# ACB-R1_1-43-CH04.net
KiCad netlist of a schematic drawn in EAGLE
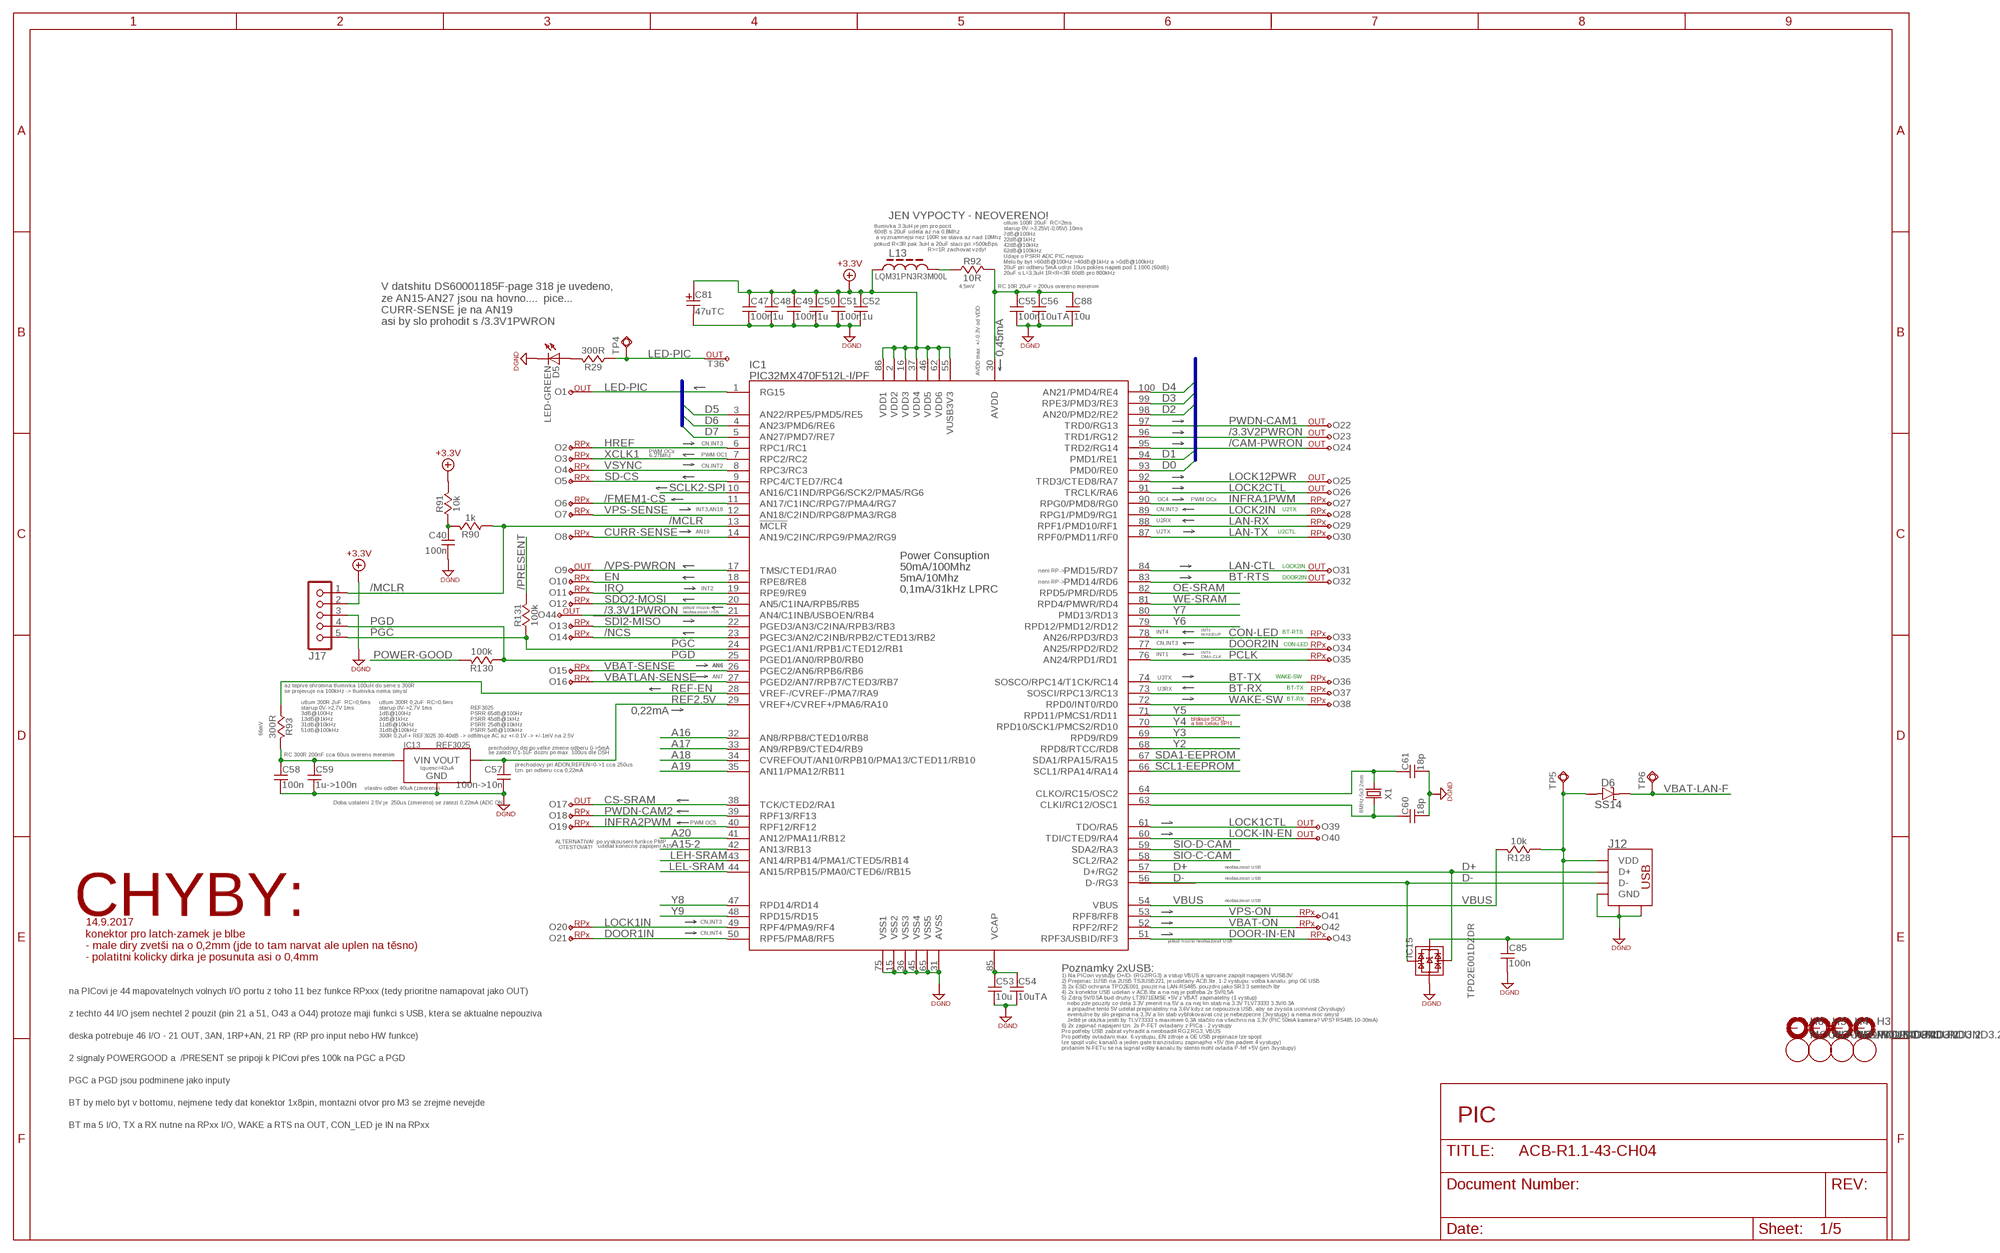
[diagram p0: schematic, sheet 1]
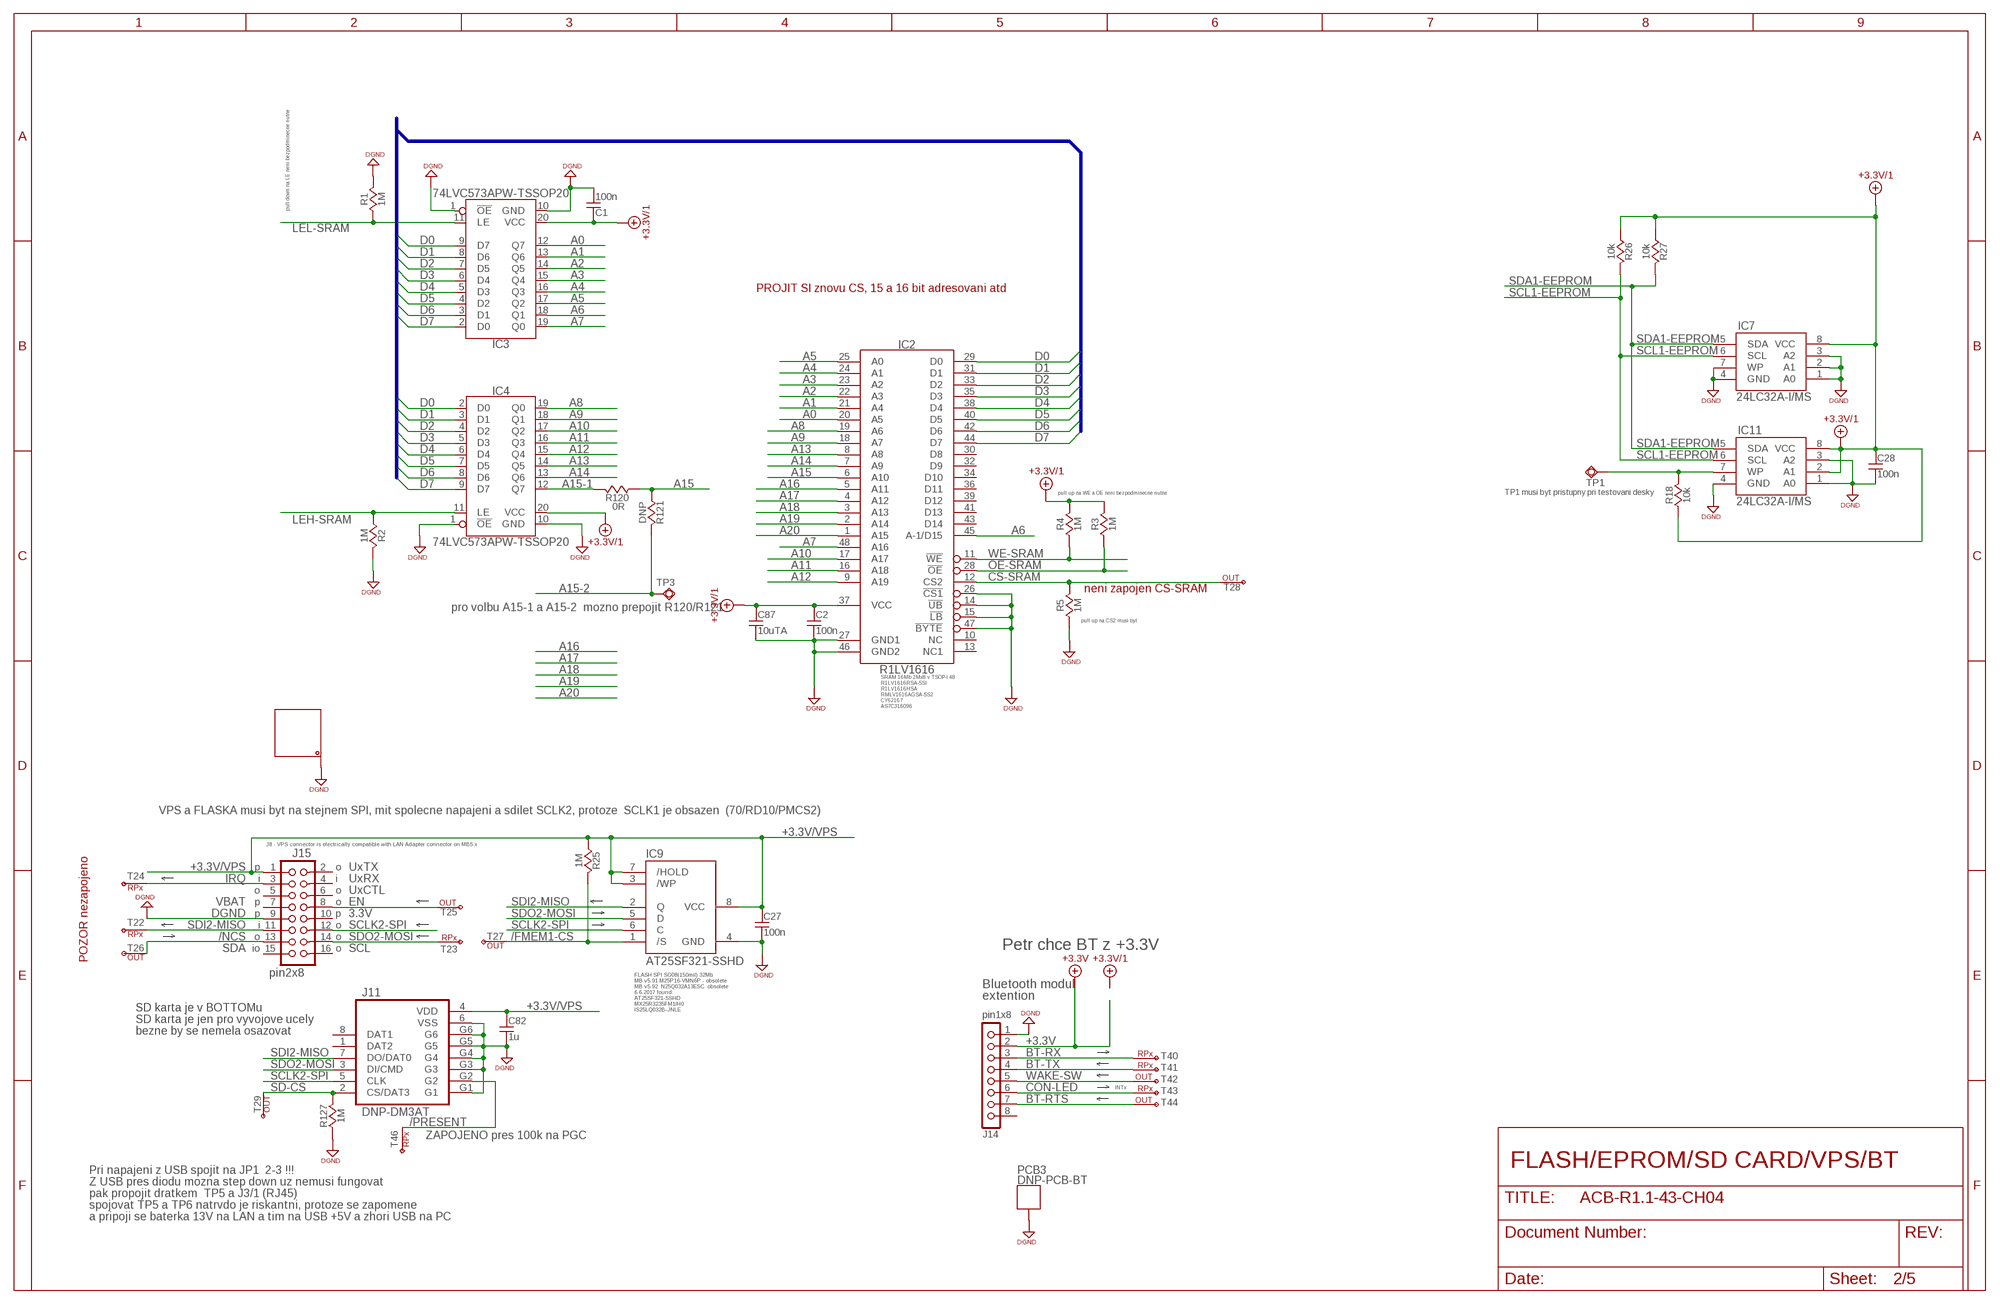
[diagram p1: schematic, sheet 2]
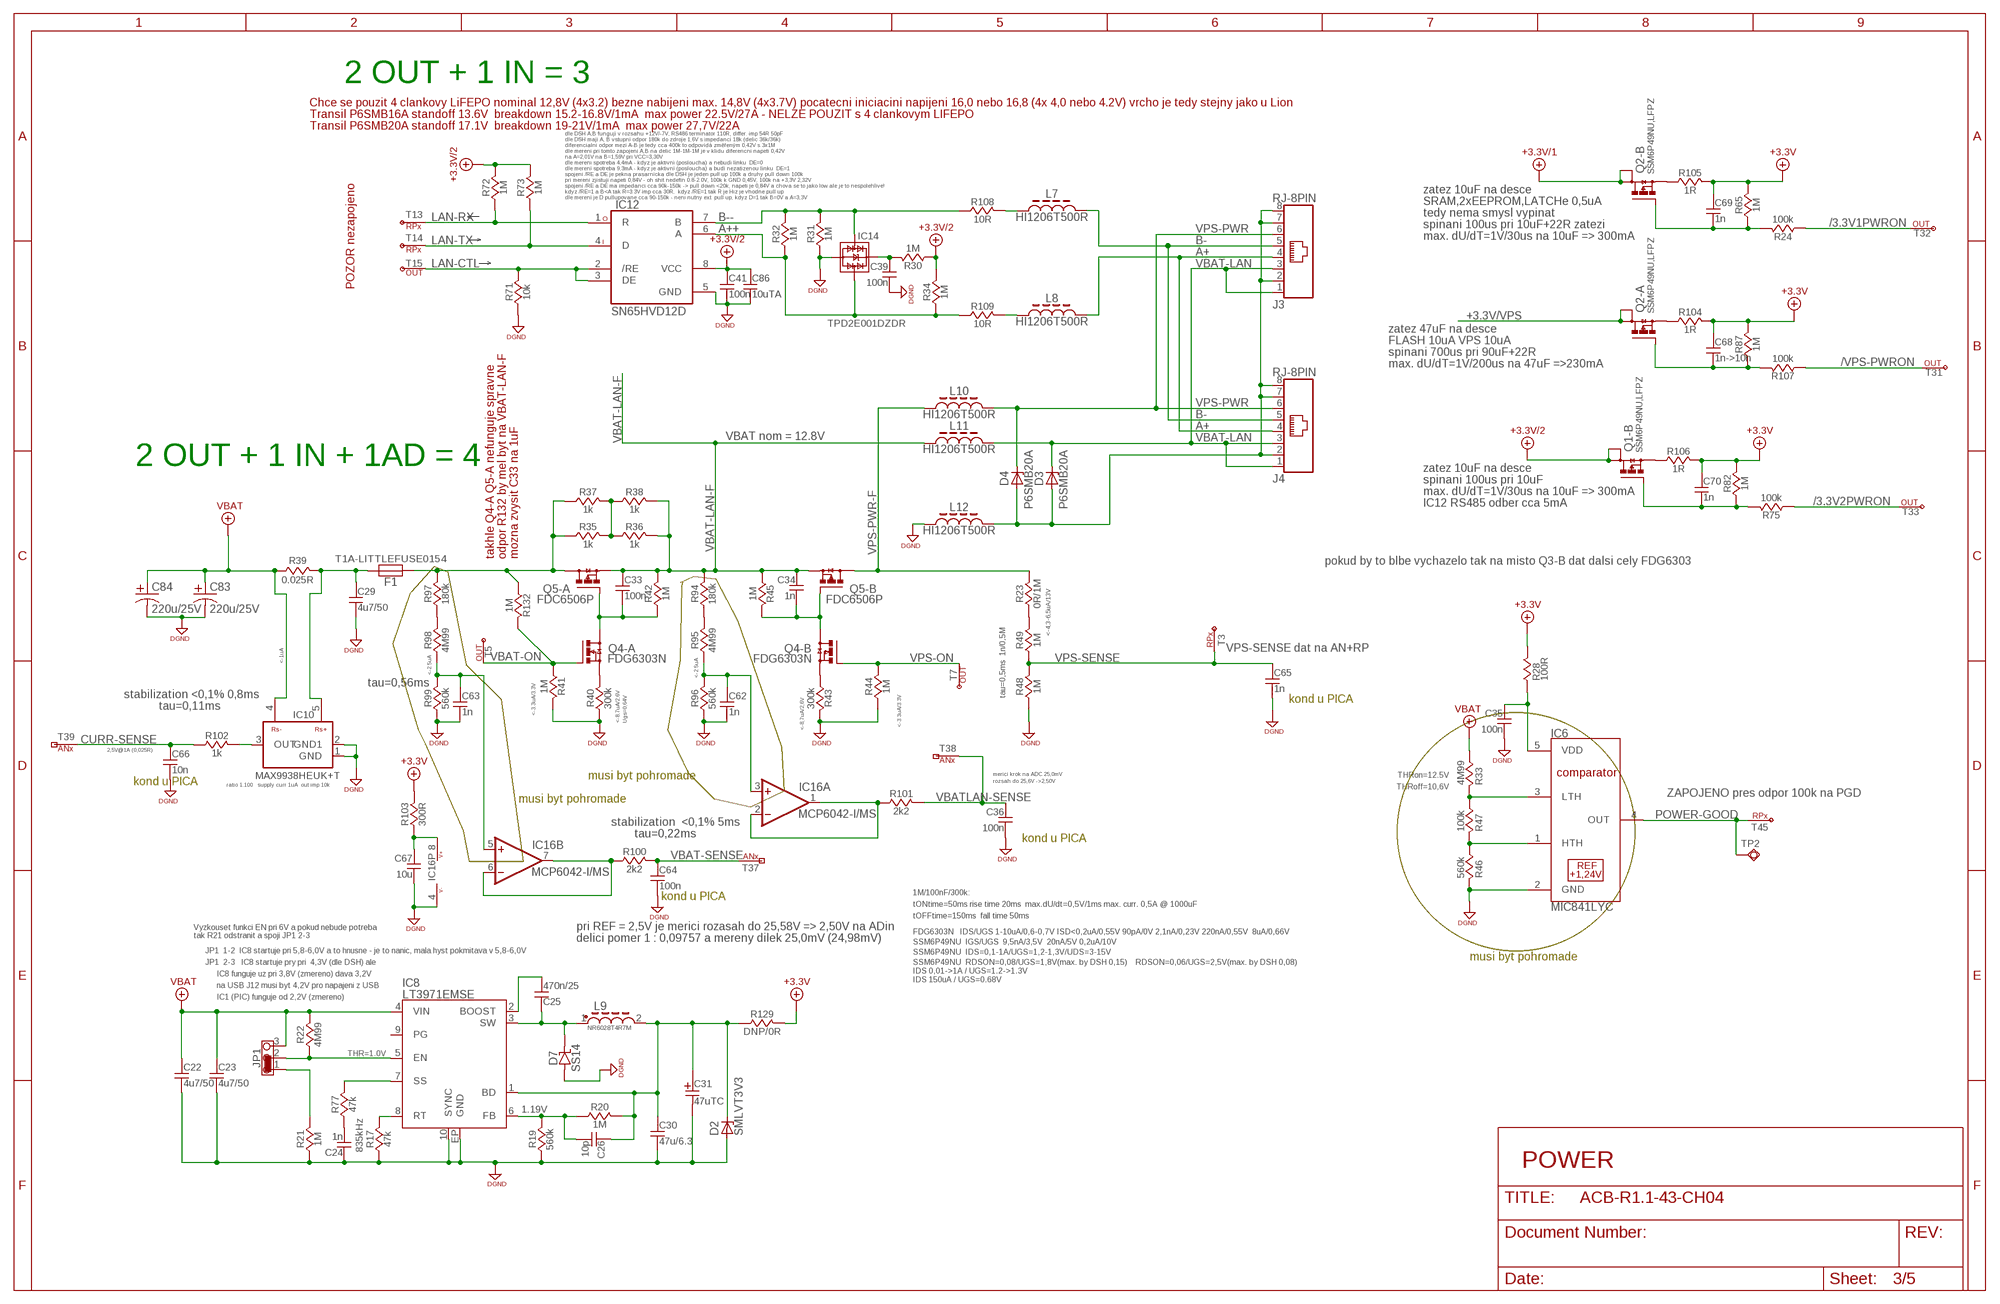
[diagram p2: schematic, sheet 3]
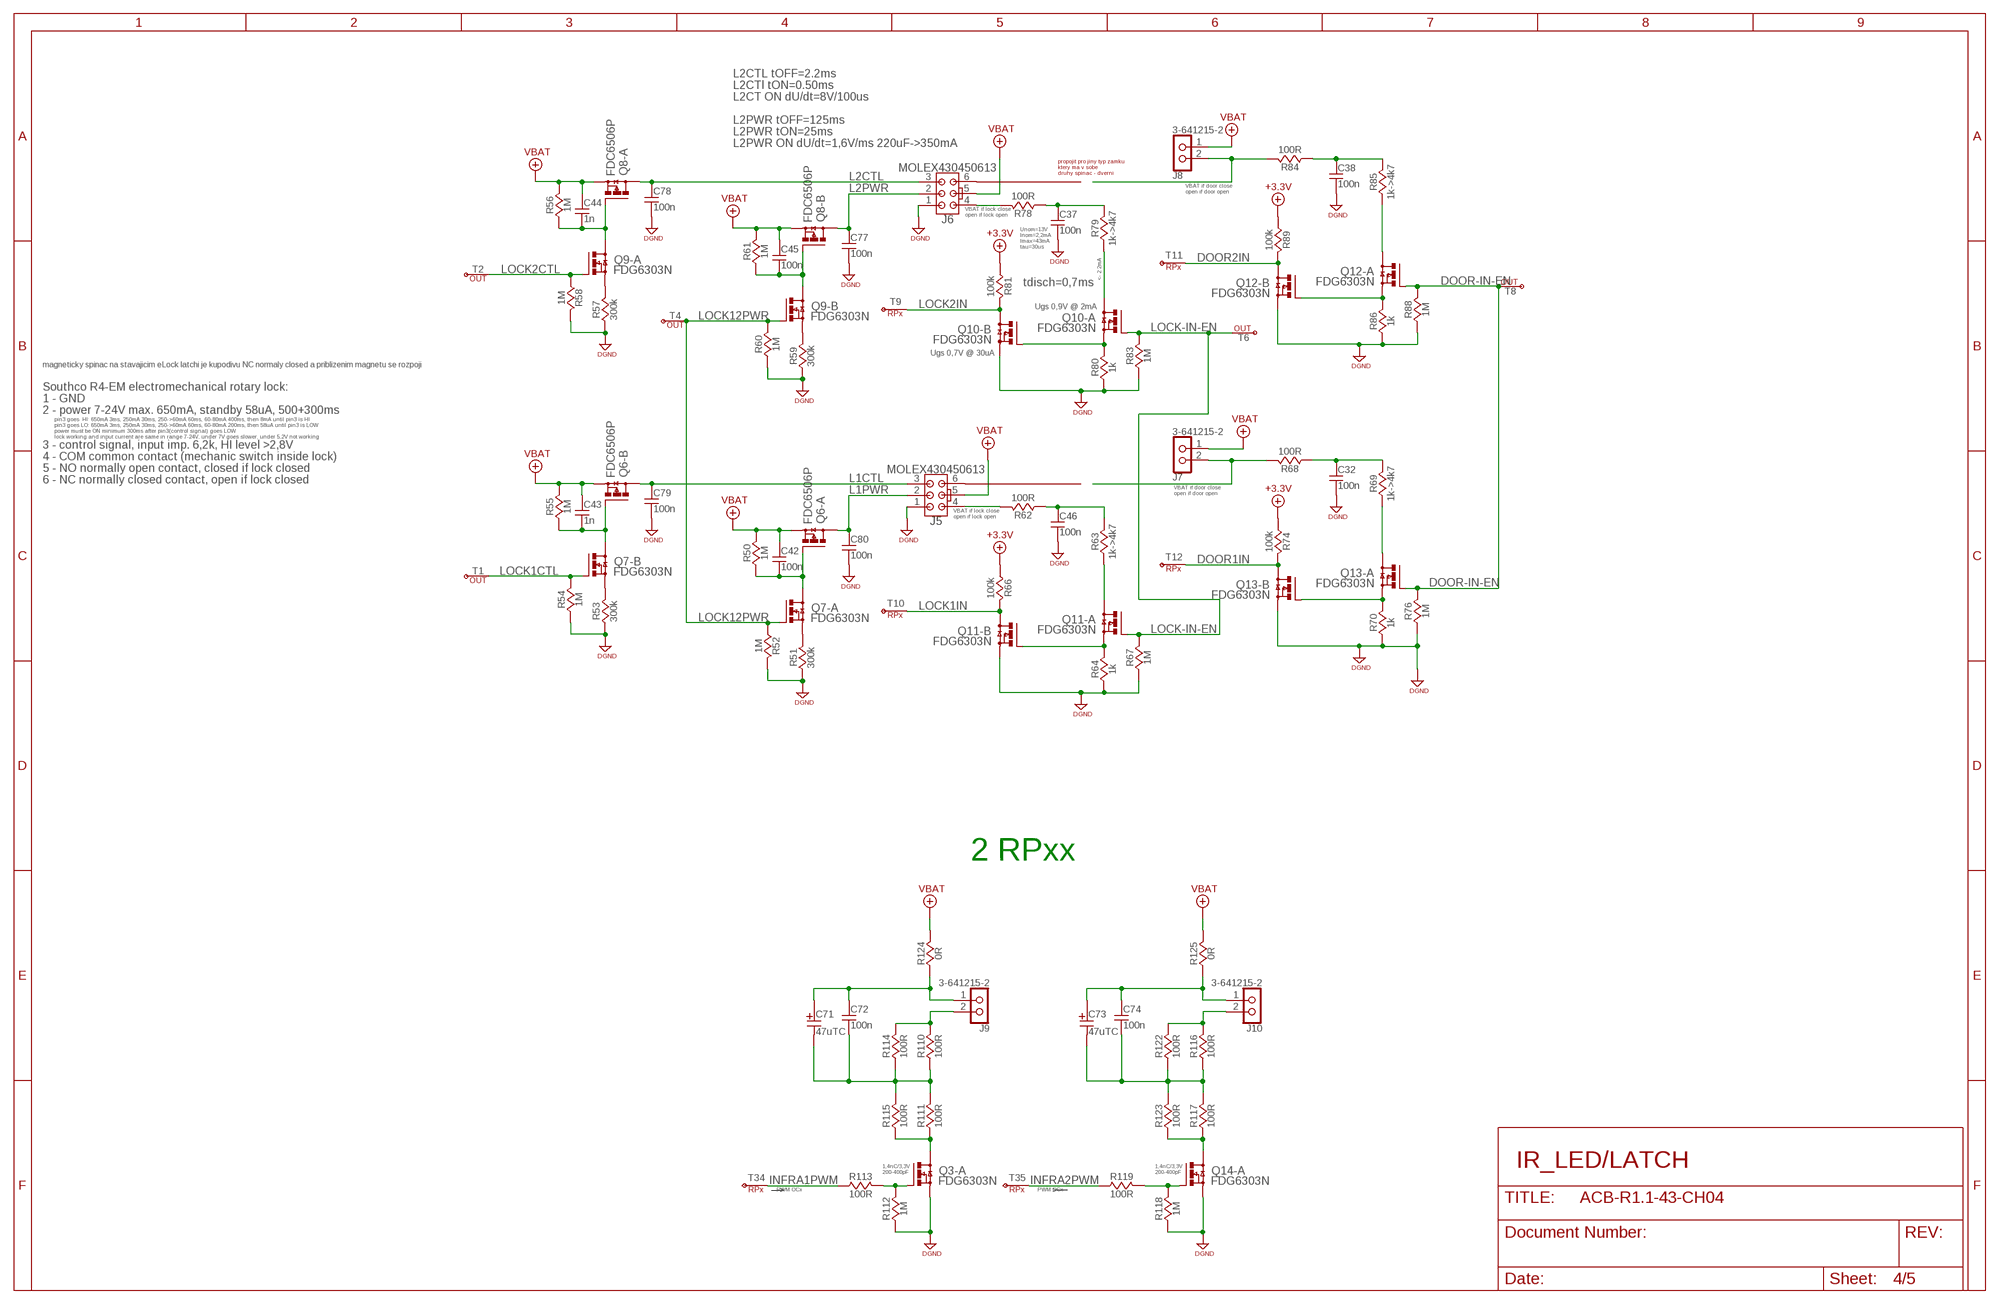
[diagram p3: schematic, sheet 4]
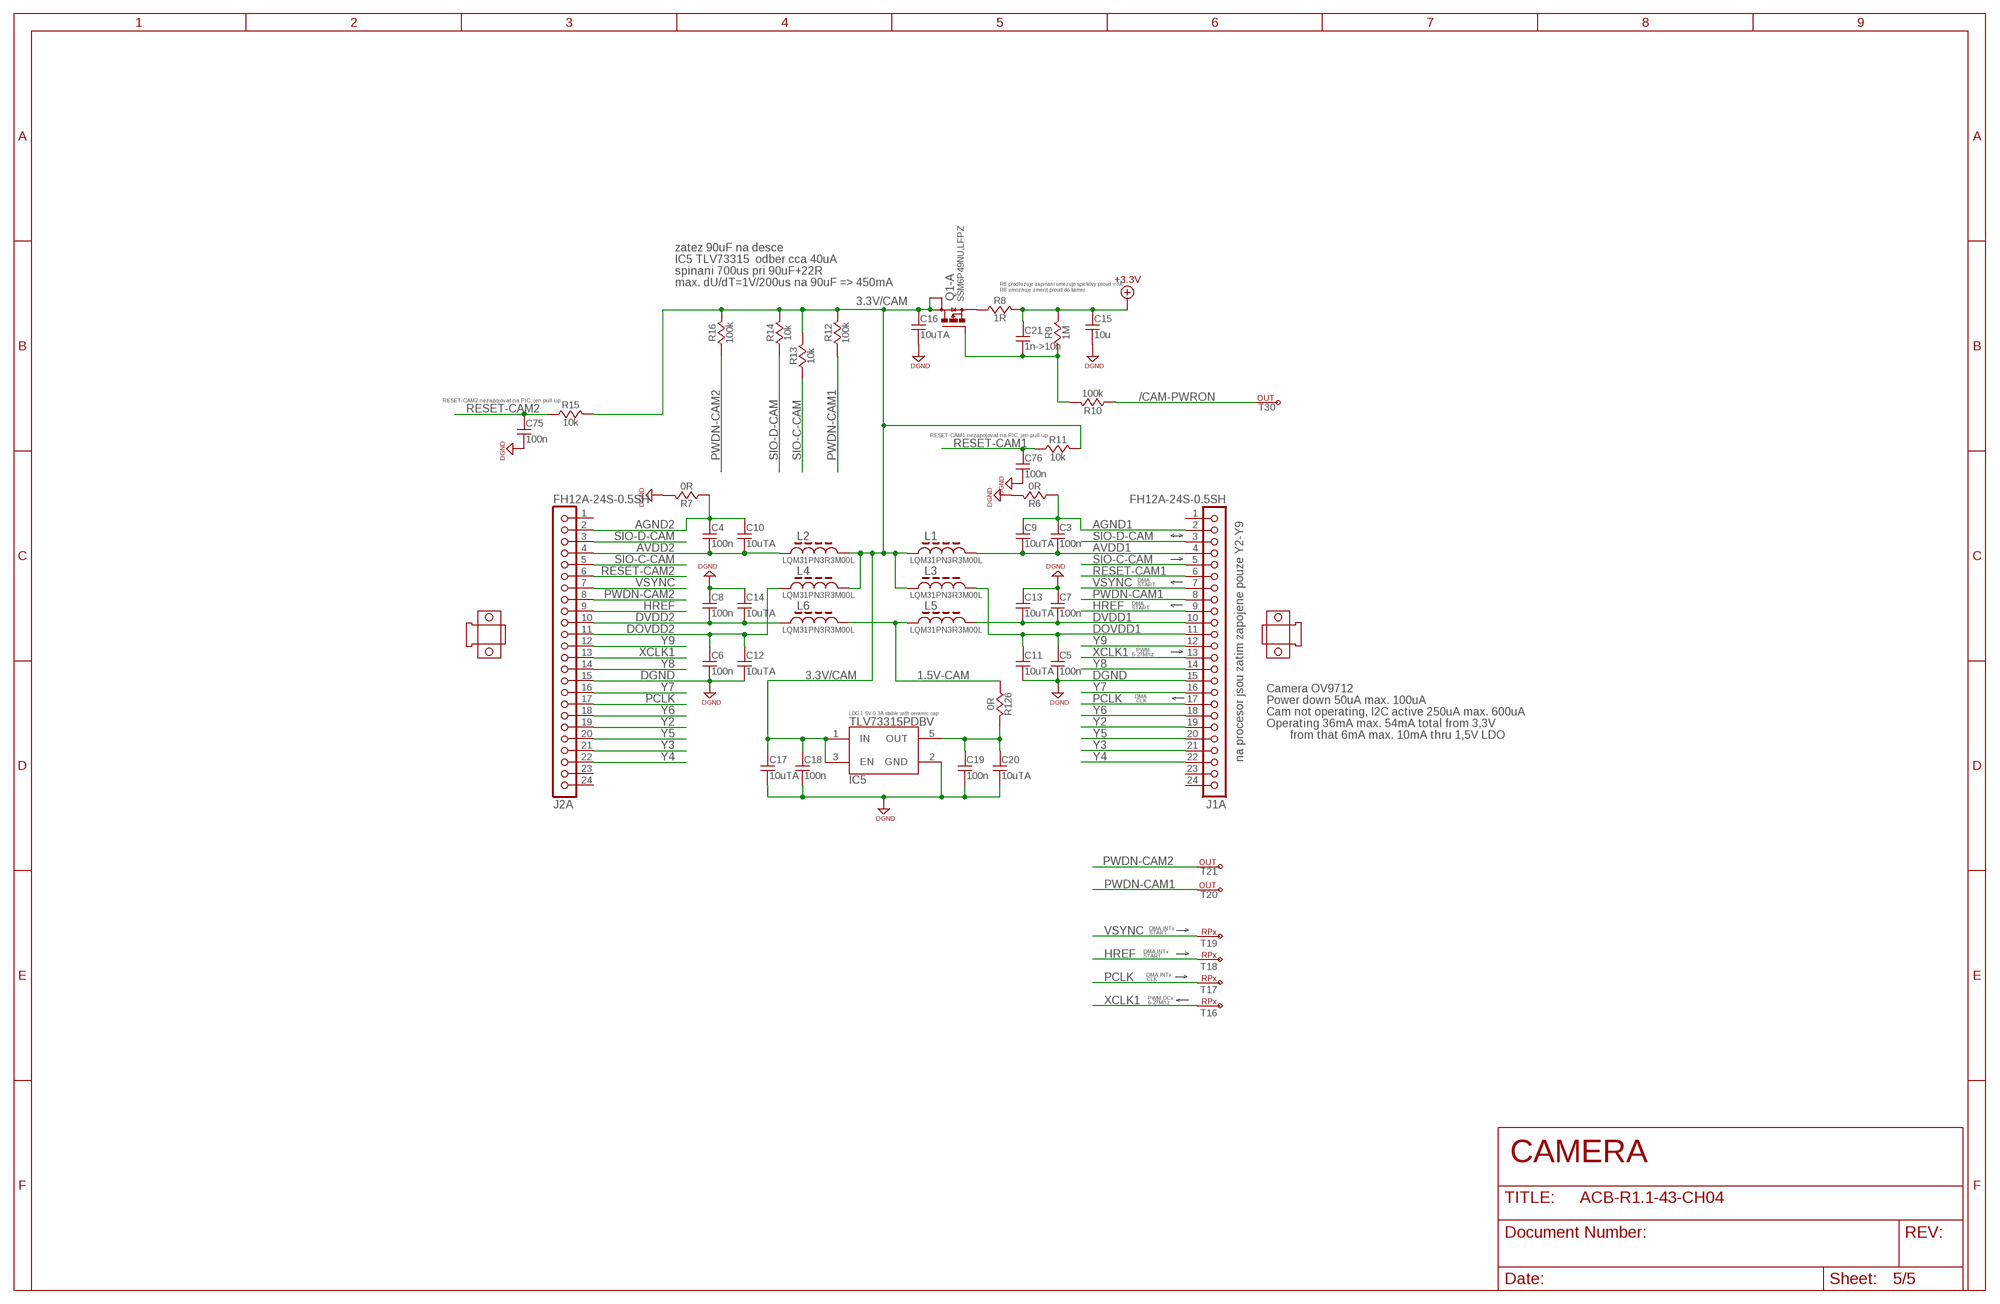
[diagram p4: schematic, sheet 5]

(export (version "E")
  (design (tool "Eeschema 10.0.6"))
  (components
    (comp (ref "C1")
      (value "100n")
      (footprint "eagle-import:0603")
      (libsource (lib "eagle-import") (part "C-0603"))
    )
    (comp (ref "C2")
      (value "100n")
      (footprint "eagle-import:0603")
      (libsource (lib "eagle-import") (part "C-0603"))
    )
    (comp (ref "C27")
      (value "100n")
      (footprint "eagle-import:0603")
      (libsource (lib "eagle-import") (part "C-0603"))
    )
    (comp (ref "C28")
      (value "100n")
      (footprint "eagle-import:0603")
      (libsource (lib "eagle-import") (part "C-0603"))
    )
    (comp (ref "C82")
      (value "1u")
      (footprint "eagle-import:0603")
      (libsource (lib "eagle-import") (part "C-0603"))
    )
    (comp (ref "C87")
      (value "10uTA")
      (footprint "eagle-import:1206")
      (libsource (lib "eagle-import") (part "C-1206"))
    )
    (comp (ref "IC2")
      (value "R1LV1616")
      (footprint "eagle-import:48-TSOP-I")
      (libsource (lib "eagle-import") (part "R1LV1616HSA"))
    )
    (comp (ref "IC3")
      (value "74LVC573APW-TSSOP20")
      (footprint "eagle-import:TSSOP20")
      (libsource (lib "eagle-import") (part "74LVC573APW-TSSOP20"))
    )
    (comp (ref "IC4")
      (value "74LVC573APW-TSSOP20")
      (footprint "eagle-import:TSSOP20")
      (libsource (lib "eagle-import") (part "74LVC573APW-TSSOP20"))
    )
    (comp (ref "IC7")
      (value "24LC32A-I/MS")
      (footprint "eagle-import:MSOP-08")
      (libsource (lib "eagle-import") (part "24-I/MS"))
    )
    (comp (ref "IC9")
      (value "AT25SF321-SSHD")
      (footprint "eagle-import:SO-08")
      (libsource (lib "eagle-import") (part "M25P16-VMN6P"))
    )
    (comp (ref "IC11")
      (value "24LC32A-I/MS")
      (footprint "eagle-import:MSOP-08")
      (libsource (lib "eagle-import") (part "24-I/MS"))
    )
    (comp (ref "J11")
      (value "DNP-DM3AT")
      (footprint "eagle-import:DM3AT")
      (libsource (lib "eagle-import") (part "DM3AT"))
    )
    (comp (ref "J14")
      (value "pin1x8")
      (footprint "eagle-import:MA08-1-MALE")
      (libsource (lib "eagle-import") (part "MA08-1-M"))
    )
    (comp (ref "J15")
      (value "pin2x8")
      (footprint "eagle-import:MA08-2")
      (libsource (lib "eagle-import") (part "MA08-2"))
    )
    (comp (ref "PCB2")
      (value "DNP-PCB-VPS")
      (footprint "eagle-import:PCB-VPS")
      (libsource (lib "eagle-import") (part "PCB-VPS-1"))
    )
    (comp (ref "PCB3")
      (value "DNP-PCB-BT")
      (footprint "eagle-import:BT_MODULE_BRD")
      (libsource (lib "eagle-import") (part "BT_PCBBRD"))
    )
    (comp (ref "R1")
      (value "1M")
      (footprint "eagle-import:0603")
      (libsource (lib "eagle-import") (part "R-0603"))
    )
    (comp (ref "R2")
      (value "1M")
      (footprint "eagle-import:0603")
      (libsource (lib "eagle-import") (part "R-0603"))
    )
    (comp (ref "R3")
      (value "1M")
      (footprint "eagle-import:0603")
      (libsource (lib "eagle-import") (part "R-0603"))
    )
    (comp (ref "R4")
      (value "1M")
      (footprint "eagle-import:0603")
      (libsource (lib "eagle-import") (part "R-0603"))
    )
    (comp (ref "R5")
      (value "1M")
      (footprint "eagle-import:0603")
      (libsource (lib "eagle-import") (part "R-0603"))
    )
    (comp (ref "R18")
      (value "10k")
      (footprint "eagle-import:0603")
      (libsource (lib "eagle-import") (part "R-0603"))
    )
    (comp (ref "R25")
      (value "1M")
      (footprint "eagle-import:0603")
      (libsource (lib "eagle-import") (part "R-0603"))
    )
    (comp (ref "R26")
      (value "10k")
      (footprint "eagle-import:0603")
      (libsource (lib "eagle-import") (part "R-0603"))
    )
    (comp (ref "R27")
      (value "10k")
      (footprint "eagle-import:0603")
      (libsource (lib "eagle-import") (part "R-0603"))
    )
    (comp (ref "R120")
      (value "0R")
      (footprint "eagle-import:0603")
      (libsource (lib "eagle-import") (part "R-0603"))
    )
    (comp (ref "R121")
      (value "DNP")
      (footprint "eagle-import:0603")
      (libsource (lib "eagle-import") (part "R-0603"))
    )
    (comp (ref "R127")
      (value "1M")
      (footprint "eagle-import:0603")
      (libsource (lib "eagle-import") (part "R-0603"))
    )
    (comp (ref "T22")
      (value "PIC-RPX")
      (footprint "eagle-import:TEMP-PAD")
      (libsource (lib "eagle-import") (part "PIC-RPX"))
    )
    (comp (ref "T23")
      (value "PIC-RPX")
      (footprint "eagle-import:TEMP-PAD")
      (libsource (lib "eagle-import") (part "PIC-RPX"))
    )
    (comp (ref "T24")
      (value "PIC-RPX")
      (footprint "eagle-import:TEMP-PAD")
      (libsource (lib "eagle-import") (part "PIC-RPX"))
    )
    (comp (ref "T25")
      (value "PIC-OUT")
      (footprint "eagle-import:TEMP-PAD")
      (libsource (lib "eagle-import") (part "PIC-OUT"))
    )
    (comp (ref "T26")
      (value "PIC-OUT")
      (footprint "eagle-import:TEMP-PAD")
      (libsource (lib "eagle-import") (part "PIC-OUT"))
    )
    (comp (ref "T27")
      (value "PIC-OUT")
      (footprint "eagle-import:TEMP-PAD")
      (libsource (lib "eagle-import") (part "PIC-OUT"))
    )
    (comp (ref "T28")
      (value "PIC-OUT")
      (footprint "eagle-import:TEMP-PAD")
      (libsource (lib "eagle-import") (part "PIC-OUT"))
    )
    (comp (ref "T29")
      (value "PIC-OUT")
      (footprint "eagle-import:TEMP-PAD")
      (libsource (lib "eagle-import") (part "PIC-OUT"))
    )
    (comp (ref "T40")
      (value "PIC-RPX")
      (footprint "eagle-import:TEMP-PAD")
      (libsource (lib "eagle-import") (part "PIC-RPX"))
    )
    (comp (ref "T41")
      (value "PIC-RPX")
      (footprint "eagle-import:TEMP-PAD")
      (libsource (lib "eagle-import") (part "PIC-RPX"))
    )
    (comp (ref "T42")
      (value "PIC-OUT")
      (footprint "eagle-import:TEMP-PAD")
      (libsource (lib "eagle-import") (part "PIC-OUT"))
    )
    (comp (ref "T43")
      (value "PIC-RPX")
      (footprint "eagle-import:TEMP-PAD")
      (libsource (lib "eagle-import") (part "PIC-RPX"))
    )
    (comp (ref "T44")
      (value "PIC-OUT")
      (footprint "eagle-import:TEMP-PAD")
      (libsource (lib "eagle-import") (part "PIC-OUT"))
    )
    (comp (ref "T46")
      (value "PIC-RPX")
      (footprint "eagle-import:TEMP-PAD")
      (libsource (lib "eagle-import") (part "PIC-RPX"))
    )
    (comp (ref "TP1")
      (value "DNP-TestPoint")
      (footprint "eagle-import:SMD_ROUND_1MM")
      (libsource (lib "eagle-import") (part "ROUND_SMD1MM"))
    )
    (comp (ref "TP3")
      (value "DNP-TestPoint")
      (footprint "eagle-import:TH_ROUND_14MM08MM")
      (libsource (lib "eagle-import") (part "ROUND_SMDTH1.4MM"))
    )
    (comp (ref "C32")
      (value "100n")
      (footprint "eagle-import:0603")
      (libsource (lib "eagle-import") (part "C-0603"))
    )
    (comp (ref "C37")
      (value "100n")
      (footprint "eagle-import:0603")
      (libsource (lib "eagle-import") (part "C-0603"))
    )
    (comp (ref "C38")
      (value "100n")
      (footprint "eagle-import:0603")
      (libsource (lib "eagle-import") (part "C-0603"))
    )
    (comp (ref "C42")
      (value "100n")
      (footprint "eagle-import:0603")
      (libsource (lib "eagle-import") (part "C-0603"))
    )
    (comp (ref "C43")
      (value "1n")
      (footprint "eagle-import:0603")
      (libsource (lib "eagle-import") (part "C-0603"))
    )
    (comp (ref "C44")
      (value "1n")
      (footprint "eagle-import:0603")
      (libsource (lib "eagle-import") (part "C-0603"))
    )
    (comp (ref "C45")
      (value "100n")
      (footprint "eagle-import:0603")
      (libsource (lib "eagle-import") (part "C-0603"))
    )
    (comp (ref "C46")
      (value "100n")
      (footprint "eagle-import:0603")
      (libsource (lib "eagle-import") (part "C-0603"))
    )
    (comp (ref "C71")
      (value "47uTC")
      (footprint "eagle-import:CT-C")
      (libsource (lib "eagle-import") (part "CT-C"))
    )
    (comp (ref "C72")
      (value "100n")
      (footprint "eagle-import:0603")
      (libsource (lib "eagle-import") (part "C-0603"))
    )
    (comp (ref "C73")
      (value "47uTC")
      (footprint "eagle-import:CT-C")
      (libsource (lib "eagle-import") (part "CT-C"))
    )
    (comp (ref "C74")
      (value "100n")
      (footprint "eagle-import:0603")
      (libsource (lib "eagle-import") (part "C-0603"))
    )
    (comp (ref "C77")
      (value "100n")
      (footprint "eagle-import:0603")
      (libsource (lib "eagle-import") (part "C-0603"))
    )
    (comp (ref "C78")
      (value "100n")
      (footprint "eagle-import:0603")
      (libsource (lib "eagle-import") (part "C-0603"))
    )
    (comp (ref "C79")
      (value "100n")
      (footprint "eagle-import:0603")
      (libsource (lib "eagle-import") (part "C-0603"))
    )
    (comp (ref "C80")
      (value "100n")
      (footprint "eagle-import:0603")
      (libsource (lib "eagle-import") (part "C-0603"))
    )
    (comp (ref "J5")
      (value "MOLEX430450613")
      (footprint "eagle-import:MOLEX430450613")
      (libsource (lib "eagle-import") (part "MOLEX430450613"))
    )
    (comp (ref "J6")
      (value "MOLEX430450613")
      (footprint "eagle-import:MOLEX430450613")
      (libsource (lib "eagle-import") (part "MOLEX430450613"))
    )
    (comp (ref "J7")
      (value "3-641215-2")
      (footprint "eagle-import:3-641215-2")
      (libsource (lib "eagle-import") (part "3-641215-2"))
    )
    (comp (ref "J8")
      (value "3-641215-2")
      (footprint "eagle-import:3-641215-2")
      (libsource (lib "eagle-import") (part "3-641215-2"))
    )
    (comp (ref "J9")
      (value "3-641215-2")
      (footprint "eagle-import:3-641215-2")
      (libsource (lib "eagle-import") (part "3-641215-2"))
    )
    (comp (ref "J10")
      (value "3-641215-2")
      (footprint "eagle-import:3-641215-2")
      (libsource (lib "eagle-import") (part "3-641215-2"))
    )
    (comp (ref "Q3")
      (value "FDG6303N")
      (footprint "eagle-import:SC70-6")
      (libsource (lib "eagle-import") (part "FDG6303N"))
    )
    (comp (ref "Q6")
      (value "FDC6506P")
      (footprint "eagle-import:SSOT-6")
      (libsource (lib "eagle-import") (part "FDC6506D"))
    )
    (comp (ref "Q7")
      (value "FDG6303N")
      (footprint "eagle-import:SC70-6")
      (libsource (lib "eagle-import") (part "FDG6303N"))
    )
    (comp (ref "Q8")
      (value "FDC6506P")
      (footprint "eagle-import:SSOT-6")
      (libsource (lib "eagle-import") (part "FDC6506D"))
    )
    (comp (ref "Q9")
      (value "FDG6303N")
      (footprint "eagle-import:SC70-6")
      (libsource (lib "eagle-import") (part "FDG6303N"))
    )
    (comp (ref "Q10")
      (value "FDG6303N")
      (footprint "eagle-import:SC70-6")
      (libsource (lib "eagle-import") (part "FDG6303N"))
    )
    (comp (ref "Q11")
      (value "FDG6303N")
      (footprint "eagle-import:SC70-6")
      (libsource (lib "eagle-import") (part "FDG6303N"))
    )
    (comp (ref "Q12")
      (value "FDG6303N")
      (footprint "eagle-import:SC70-6")
      (libsource (lib "eagle-import") (part "FDG6303N"))
    )
    (comp (ref "Q13")
      (value "FDG6303N")
      (footprint "eagle-import:SC70-6")
      (libsource (lib "eagle-import") (part "FDG6303N"))
    )
    (comp (ref "Q14")
      (value "FDG6303N")
      (footprint "eagle-import:SC70-6")
      (libsource (lib "eagle-import") (part "FDG6303N"))
    )
    (comp (ref "R50")
      (value "1M")
      (footprint "eagle-import:0603")
      (libsource (lib "eagle-import") (part "R-0603"))
    )
    (comp (ref "R51")
      (value "300k")
      (footprint "eagle-import:0603")
      (libsource (lib "eagle-import") (part "R-0603"))
    )
    (comp (ref "R52")
      (value "1M")
      (footprint "eagle-import:0603")
      (libsource (lib "eagle-import") (part "R-0603"))
    )
    (comp (ref "R53")
      (value "300k")
      (footprint "eagle-import:0603")
      (libsource (lib "eagle-import") (part "R-0603"))
    )
    (comp (ref "R54")
      (value "1M")
      (footprint "eagle-import:0603")
      (libsource (lib "eagle-import") (part "R-0603"))
    )
    (comp (ref "R55")
      (value "1M")
      (footprint "eagle-import:0603")
      (libsource (lib "eagle-import") (part "R-0603"))
    )
    (comp (ref "R56")
      (value "1M")
      (footprint "eagle-import:0603")
      (libsource (lib "eagle-import") (part "R-0603"))
    )
    (comp (ref "R57")
      (value "300k")
      (footprint "eagle-import:0603")
      (libsource (lib "eagle-import") (part "R-0603"))
    )
    (comp (ref "R58")
      (value "1M")
      (footprint "eagle-import:0603")
      (libsource (lib "eagle-import") (part "R-0603"))
    )
    (comp (ref "R59")
      (value "300k")
      (footprint "eagle-import:0603")
      (libsource (lib "eagle-import") (part "R-0603"))
    )
    (comp (ref "R60")
      (value "1M")
      (footprint "eagle-import:0603")
      (libsource (lib "eagle-import") (part "R-0603"))
    )
    (comp (ref "R61")
      (value "1M")
      (footprint "eagle-import:0603")
      (libsource (lib "eagle-import") (part "R-0603"))
    )
    (comp (ref "R62")
      (value "100R")
      (footprint "eagle-import:0603")
      (libsource (lib "eagle-import") (part "R-0603"))
    )
    (comp (ref "R63")
      (value "1k->4k7")
      (footprint "eagle-import:0603")
      (libsource (lib "eagle-import") (part "R-0603"))
    )
    (comp (ref "R64")
      (value "1k")
      (footprint "eagle-import:0603")
      (libsource (lib "eagle-import") (part "R-0603"))
    )
    (comp (ref "R66")
      (value "100k")
      (footprint "eagle-import:0603")
      (libsource (lib "eagle-import") (part "R-0603"))
    )
    (comp (ref "R67")
      (value "1M")
      (footprint "eagle-import:0603")
      (libsource (lib "eagle-import") (part "R-0603"))
    )
    (comp (ref "R68")
      (value "100R")
      (footprint "eagle-import:0603")
      (libsource (lib "eagle-import") (part "R-0603"))
    )
    (comp (ref "R69")
      (value "1k->4k7")
      (footprint "eagle-import:0603")
      (libsource (lib "eagle-import") (part "R-0603"))
    )
    (comp (ref "R70")
      (value "1k")
      (footprint "eagle-import:0603")
      (libsource (lib "eagle-import") (part "R-0603"))
    )
    (comp (ref "R74")
      (value "100k")
      (footprint "eagle-import:0603")
      (libsource (lib "eagle-import") (part "R-0603"))
    )
    (comp (ref "R76")
      (value "1M")
      (footprint "eagle-import:0603")
      (libsource (lib "eagle-import") (part "R-0603"))
    )
    (comp (ref "R78")
      (value "100R")
      (footprint "eagle-import:0603")
      (libsource (lib "eagle-import") (part "R-0603"))
    )
    (comp (ref "R79")
      (value "1k->4k7")
      (footprint "eagle-import:0603")
      (libsource (lib "eagle-import") (part "R-0603"))
    )
    (comp (ref "R80")
      (value "1k")
      (footprint "eagle-import:0603")
      (libsource (lib "eagle-import") (part "R-0603"))
    )
    (comp (ref "R81")
      (value "100k")
      (footprint "eagle-import:0603")
      (libsource (lib "eagle-import") (part "R-0603"))
    )
    (comp (ref "R83")
      (value "1M")
      (footprint "eagle-import:0603")
      (libsource (lib "eagle-import") (part "R-0603"))
    )
    (comp (ref "R84")
      (value "100R")
      (footprint "eagle-import:0603")
      (libsource (lib "eagle-import") (part "R-0603"))
    )
    (comp (ref "R85")
      (value "1k->4k7")
      (footprint "eagle-import:0603")
      (libsource (lib "eagle-import") (part "R-0603"))
    )
    (comp (ref "R86")
      (value "1k")
      (footprint "eagle-import:0603")
      (libsource (lib "eagle-import") (part "R-0603"))
    )
    (comp (ref "R88")
      (value "1M")
      (footprint "eagle-import:0603")
      (libsource (lib "eagle-import") (part "R-0603"))
    )
    (comp (ref "R89")
      (value "100k")
      (footprint "eagle-import:0603")
      (libsource (lib "eagle-import") (part "R-0603"))
    )
    (comp (ref "R110")
      (value "100R")
      (footprint "eagle-import:0603")
      (libsource (lib "eagle-import") (part "R-0603"))
    )
    (comp (ref "R111")
      (value "100R")
      (footprint "eagle-import:0603")
      (libsource (lib "eagle-import") (part "R-0603"))
    )
    (comp (ref "R112")
      (value "1M")
      (footprint "eagle-import:0603")
      (libsource (lib "eagle-import") (part "R-0603"))
    )
    (comp (ref "R113")
      (value "100R")
      (footprint "eagle-import:0603")
      (libsource (lib "eagle-import") (part "R-0603"))
    )
    (comp (ref "R114")
      (value "100R")
      (footprint "eagle-import:0603")
      (libsource (lib "eagle-import") (part "R-0603"))
    )
    (comp (ref "R115")
      (value "100R")
      (footprint "eagle-import:0603")
      (libsource (lib "eagle-import") (part "R-0603"))
    )
    (comp (ref "R116")
      (value "100R")
      (footprint "eagle-import:0603")
      (libsource (lib "eagle-import") (part "R-0603"))
    )
    (comp (ref "R117")
      (value "100R")
      (footprint "eagle-import:0603")
      (libsource (lib "eagle-import") (part "R-0603"))
    )
    (comp (ref "R118")
      (value "1M")
      (footprint "eagle-import:0603")
      (libsource (lib "eagle-import") (part "R-0603"))
    )
    (comp (ref "R119")
      (value "100R")
      (footprint "eagle-import:0603")
      (libsource (lib "eagle-import") (part "R-0603"))
    )
    (comp (ref "R122")
      (value "100R")
      (footprint "eagle-import:0603")
      (libsource (lib "eagle-import") (part "R-0603"))
    )
    (comp (ref "R123")
      (value "100R")
      (footprint "eagle-import:0603")
      (libsource (lib "eagle-import") (part "R-0603"))
    )
    (comp (ref "R124")
      (value "0R")
      (footprint "eagle-import:0603")
      (libsource (lib "eagle-import") (part "R-0603"))
    )
    (comp (ref "R125")
      (value "0R")
      (footprint "eagle-import:0603")
      (libsource (lib "eagle-import") (part "R-0603"))
    )
    (comp (ref "T1")
      (value "PIC-OUT")
      (footprint "eagle-import:TEMP-PAD")
      (libsource (lib "eagle-import") (part "PIC-OUT"))
    )
    (comp (ref "T2")
      (value "PIC-OUT")
      (footprint "eagle-import:TEMP-PAD")
      (libsource (lib "eagle-import") (part "PIC-OUT"))
    )
    (comp (ref "T4")
      (value "PIC-OUT")
      (footprint "eagle-import:TEMP-PAD")
      (libsource (lib "eagle-import") (part "PIC-OUT"))
    )
    (comp (ref "T6")
      (value "PIC-OUT")
      (footprint "eagle-import:TEMP-PAD")
      (libsource (lib "eagle-import") (part "PIC-OUT"))
    )
    (comp (ref "T8")
      (value "PIC-OUT")
      (footprint "eagle-import:TEMP-PAD")
      (libsource (lib "eagle-import") (part "PIC-OUT"))
    )
    (comp (ref "T9")
      (value "PIC-RPX")
      (footprint "eagle-import:TEMP-PAD")
      (libsource (lib "eagle-import") (part "PIC-RPX"))
    )
    (comp (ref "T10")
      (value "PIC-RPX")
      (footprint "eagle-import:TEMP-PAD")
      (libsource (lib "eagle-import") (part "PIC-RPX"))
    )
    (comp (ref "T11")
      (value "PIC-RPX")
      (footprint "eagle-import:TEMP-PAD")
      (libsource (lib "eagle-import") (part "PIC-RPX"))
    )
    (comp (ref "T12")
      (value "PIC-RPX")
      (footprint "eagle-import:TEMP-PAD")
      (libsource (lib "eagle-import") (part "PIC-RPX"))
    )
    (comp (ref "T34")
      (value "PIC-RPX")
      (footprint "eagle-import:TEMP-PAD")
      (libsource (lib "eagle-import") (part "PIC-RPX"))
    )
    (comp (ref "T35")
      (value "PIC-RPX")
      (footprint "eagle-import:TEMP-PAD")
      (libsource (lib "eagle-import") (part "PIC-RPX"))
    )
    (comp (ref "C40")
      (value "100n")
      (footprint "eagle-import:0603")
      (libsource (lib "eagle-import") (part "C-0603"))
    )
    (comp (ref "C47")
      (value "100n")
      (footprint "eagle-import:0603")
      (libsource (lib "eagle-import") (part "C-0603"))
    )
    (comp (ref "C48")
      (value "1u")
      (footprint "eagle-import:0603")
      (libsource (lib "eagle-import") (part "C-0603"))
    )
    (comp (ref "C49")
      (value "100n")
      (footprint "eagle-import:0603")
      (libsource (lib "eagle-import") (part "C-0603"))
    )
    (comp (ref "C50")
      (value "1u")
      (footprint "eagle-import:0603")
      (libsource (lib "eagle-import") (part "C-0603"))
    )
    (comp (ref "C51")
      (value "100n")
      (footprint "eagle-import:0603")
      (libsource (lib "eagle-import") (part "C-0603"))
    )
    (comp (ref "C52")
      (value "1u")
      (footprint "eagle-import:0603")
      (libsource (lib "eagle-import") (part "C-0603"))
    )
    (comp (ref "C53")
      (value "10u")
      (footprint "eagle-import:0603")
      (libsource (lib "eagle-import") (part "C-0603"))
    )
    (comp (ref "C54")
      (value "10uTA")
      (footprint "eagle-import:1206")
      (libsource (lib "eagle-import") (part "C-1206"))
    )
    (comp (ref "C55")
      (value "100n")
      (footprint "eagle-import:0603")
      (libsource (lib "eagle-import") (part "C-0603"))
    )
    (comp (ref "C56")
      (value "10uTA")
      (footprint "eagle-import:1206")
      (libsource (lib "eagle-import") (part "C-1206"))
    )
    (comp (ref "C57")
      (value "100n->10n")
      (footprint "eagle-import:0603")
      (libsource (lib "eagle-import") (part "C-0603"))
    )
    (comp (ref "C58")
      (value "100n")
      (footprint "eagle-import:0603")
      (libsource (lib "eagle-import") (part "C-0603"))
    )
    (comp (ref "C59")
      (value "1u->100n")
      (footprint "eagle-import:0603")
      (libsource (lib "eagle-import") (part "C-0603"))
    )
    (comp (ref "C60")
      (value "18p")
      (footprint "eagle-import:0603")
      (libsource (lib "eagle-import") (part "C-0603"))
    )
    (comp (ref "C61")
      (value "18p")
      (footprint "eagle-import:0603")
      (libsource (lib "eagle-import") (part "C-0603"))
    )
    (comp (ref "C81")
      (value "47uTC")
      (footprint "eagle-import:CT-C")
      (libsource (lib "eagle-import") (part "CT-C"))
    )
    (comp (ref "C85")
      (value "100n")
      (footprint "eagle-import:0603")
      (libsource (lib "eagle-import") (part "C-0603"))
    )
    (comp (ref "C88")
      (value "10u")
      (footprint "eagle-import:0603")
      (libsource (lib "eagle-import") (part "C-0603"))
    )
    (comp (ref "D5")
      (value "LED-GREEN")
      (footprint "eagle-import:0805-POL")
      (libsource (lib "eagle-import") (part "LED-0805"))
    )
    (comp (ref "D6")
      (value "SS14")
      (footprint "eagle-import:SMA")
      (libsource (lib "eagle-import") (part "DS-SMA"))
    )
    (comp (ref "H3")
      (value "MOUNT-PAD-ROUND3.2")
      (footprint "eagle-import:3,2-PAD")
      (libsource (lib "eagle-import") (part "MOUNT-PAD-ROUND3.2"))
    )
    (comp (ref "H4")
      (value "MOUNT-PAD-ROUND3.2")
      (footprint "eagle-import:3,2-PAD")
      (libsource (lib "eagle-import") (part "MOUNT-PAD-ROUND3.2"))
    )
    (comp (ref "H5")
      (value "MOUNT-PAD-ROUND3.2")
      (footprint "eagle-import:3,2-PAD")
      (libsource (lib "eagle-import") (part "MOUNT-PAD-ROUND3.2"))
    )
    (comp (ref "H6")
      (value "MOUNT-PAD-ROUND3.2")
      (footprint "eagle-import:3,2-PAD")
      (libsource (lib "eagle-import") (part "MOUNT-PAD-ROUND3.2"))
    )
    (comp (ref "IC1")
      (value "PIC32MX470F512L-I/PF")
      (footprint "eagle-import:TQFP100_14X14_0,5MM")
      (libsource (lib "eagle-import") (part "PIC32MX470F512L-I/PF"))
    )
    (comp (ref "IC13")
      (value "REF3025")
      (footprint "eagle-import:SOT23")
      (libsource (lib "eagle-import") (part "REF3025"))
    )
    (comp (ref "IC15")
      (value "TPD2E001DZDR")
      (footprint "eagle-import:SOT-143")
      (libsource (lib "eagle-import") (part "SR05.TCT"))
    )
    (comp (ref "J12")
      (value "USB_A_180")
      (footprint "eagle-import:KONEKT1_USB_A_180")
      (libsource (lib "eagle-import") (part "CON_USB_A180"))
    )
    (comp (ref "J17")
      (value "DNP-open-hole")
      (footprint "eagle-import:MA05-1")
      (libsource (lib "eagle-import") (part "MA05-1"))
    )
    (comp (ref "L13")
      (value "LQM31PN3R3M00L")
      (footprint "eagle-import:1206")
      (libsource (lib "eagle-import") (part "L-1206"))
    )
    (comp (ref "O1")
      (value "PIC-OUT")
      (footprint "eagle-import:TEMP-PAD")
      (libsource (lib "eagle-import") (part "PIC-OUT"))
    )
    (comp (ref "O2")
      (value "PIC-RPX")
      (footprint "eagle-import:TEMP-PAD")
      (libsource (lib "eagle-import") (part "PIC-RPX"))
    )
    (comp (ref "O3")
      (value "PIC-RPX")
      (footprint "eagle-import:TEMP-PAD")
      (libsource (lib "eagle-import") (part "PIC-RPX"))
    )
    (comp (ref "O4")
      (value "PIC-RPX")
      (footprint "eagle-import:TEMP-PAD")
      (libsource (lib "eagle-import") (part "PIC-RPX"))
    )
    (comp (ref "O5")
      (value "PIC-RPX")
      (footprint "eagle-import:TEMP-PAD")
      (libsource (lib "eagle-import") (part "PIC-RPX"))
    )
    (comp (ref "O6")
      (value "PIC-RPX")
      (footprint "eagle-import:TEMP-PAD")
      (libsource (lib "eagle-import") (part "PIC-RPX"))
    )
    (comp (ref "O7")
      (value "PIC-RPX")
      (footprint "eagle-import:TEMP-PAD")
      (libsource (lib "eagle-import") (part "PIC-RPX"))
    )
    (comp (ref "O8")
      (value "PIC-RPX")
      (footprint "eagle-import:TEMP-PAD")
      (libsource (lib "eagle-import") (part "PIC-RPX"))
    )
    (comp (ref "O9")
      (value "PIC-OUT")
      (footprint "eagle-import:TEMP-PAD")
      (libsource (lib "eagle-import") (part "PIC-OUT"))
    )
    (comp (ref "O10")
      (value "PIC-RPX")
      (footprint "eagle-import:TEMP-PAD")
      (libsource (lib "eagle-import") (part "PIC-RPX"))
    )
    (comp (ref "O11")
      (value "PIC-RPX")
      (footprint "eagle-import:TEMP-PAD")
      (libsource (lib "eagle-import") (part "PIC-RPX"))
    )
    (comp (ref "O12")
      (value "PIC-RPX")
      (footprint "eagle-import:TEMP-PAD")
      (libsource (lib "eagle-import") (part "PIC-RPX"))
    )
    (comp (ref "O13")
      (value "PIC-RPX")
      (footprint "eagle-import:TEMP-PAD")
      (libsource (lib "eagle-import") (part "PIC-RPX"))
    )
    (comp (ref "O14")
      (value "PIC-RPX")
      (footprint "eagle-import:TEMP-PAD")
      (libsource (lib "eagle-import") (part "PIC-RPX"))
    )
    (comp (ref "O15")
      (value "PIC-RPX")
      (footprint "eagle-import:TEMP-PAD")
      (libsource (lib "eagle-import") (part "PIC-RPX"))
    )
    (comp (ref "O16")
      (value "PIC-RPX")
      (footprint "eagle-import:TEMP-PAD")
      (libsource (lib "eagle-import") (part "PIC-RPX"))
    )
    (comp (ref "O17")
      (value "PIC-OUT")
      (footprint "eagle-import:TEMP-PAD")
      (libsource (lib "eagle-import") (part "PIC-OUT"))
    )
    (comp (ref "O18")
      (value "PIC-RPX")
      (footprint "eagle-import:TEMP-PAD")
      (libsource (lib "eagle-import") (part "PIC-RPX"))
    )
    (comp (ref "O19")
      (value "PIC-RPX")
      (footprint "eagle-import:TEMP-PAD")
      (libsource (lib "eagle-import") (part "PIC-RPX"))
    )
    (comp (ref "O20")
      (value "PIC-RPX")
      (footprint "eagle-import:TEMP-PAD")
      (libsource (lib "eagle-import") (part "PIC-RPX"))
    )
    (comp (ref "O21")
      (value "PIC-RPX")
      (footprint "eagle-import:TEMP-PAD")
      (libsource (lib "eagle-import") (part "PIC-RPX"))
    )
    (comp (ref "O22")
      (value "PIC-OUT")
      (footprint "eagle-import:TEMP-PAD")
      (libsource (lib "eagle-import") (part "PIC-OUT"))
    )
    (comp (ref "O23")
      (value "PIC-OUT")
      (footprint "eagle-import:TEMP-PAD")
      (libsource (lib "eagle-import") (part "PIC-OUT"))
    )
    (comp (ref "O24")
      (value "PIC-OUT")
      (footprint "eagle-import:TEMP-PAD")
      (libsource (lib "eagle-import") (part "PIC-OUT"))
    )
    (comp (ref "O25")
      (value "PIC-OUT")
      (footprint "eagle-import:TEMP-PAD")
      (libsource (lib "eagle-import") (part "PIC-OUT"))
    )
    (comp (ref "O26")
      (value "PIC-OUT")
      (footprint "eagle-import:TEMP-PAD")
      (libsource (lib "eagle-import") (part "PIC-OUT"))
    )
    (comp (ref "O27")
      (value "PIC-RPX")
      (footprint "eagle-import:TEMP-PAD")
      (libsource (lib "eagle-import") (part "PIC-RPX"))
    )
    (comp (ref "O28")
      (value "PIC-RPX")
      (footprint "eagle-import:TEMP-PAD")
      (libsource (lib "eagle-import") (part "PIC-RPX"))
    )
    (comp (ref "O29")
      (value "PIC-RPX")
      (footprint "eagle-import:TEMP-PAD")
      (libsource (lib "eagle-import") (part "PIC-RPX"))
    )
    (comp (ref "O30")
      (value "PIC-RPX")
      (footprint "eagle-import:TEMP-PAD")
      (libsource (lib "eagle-import") (part "PIC-RPX"))
    )
    (comp (ref "O31")
      (value "PIC-OUT")
      (footprint "eagle-import:TEMP-PAD")
      (libsource (lib "eagle-import") (part "PIC-OUT"))
    )
    (comp (ref "O32")
      (value "PIC-OUT")
      (footprint "eagle-import:TEMP-PAD")
      (libsource (lib "eagle-import") (part "PIC-OUT"))
    )
    (comp (ref "O33")
      (value "PIC-RPX")
      (footprint "eagle-import:TEMP-PAD")
      (libsource (lib "eagle-import") (part "PIC-RPX"))
    )
    (comp (ref "O34")
      (value "PIC-RPX")
      (footprint "eagle-import:TEMP-PAD")
      (libsource (lib "eagle-import") (part "PIC-RPX"))
    )
    (comp (ref "O35")
      (value "PIC-RPX")
      (footprint "eagle-import:TEMP-PAD")
      (libsource (lib "eagle-import") (part "PIC-RPX"))
    )
    (comp (ref "O36")
      (value "PIC-RPX")
      (footprint "eagle-import:TEMP-PAD")
      (libsource (lib "eagle-import") (part "PIC-RPX"))
    )
    (comp (ref "O37")
      (value "PIC-RPX")
      (footprint "eagle-import:TEMP-PAD")
      (libsource (lib "eagle-import") (part "PIC-RPX"))
    )
    (comp (ref "O38")
      (value "PIC-RPX")
      (footprint "eagle-import:TEMP-PAD")
      (libsource (lib "eagle-import") (part "PIC-RPX"))
    )
    (comp (ref "O39")
      (value "PIC-OUT")
      (footprint "eagle-import:TEMP-PAD")
      (libsource (lib "eagle-import") (part "PIC-OUT"))
    )
    (comp (ref "O40")
      (value "PIC-OUT")
      (footprint "eagle-import:TEMP-PAD")
      (libsource (lib "eagle-import") (part "PIC-OUT"))
    )
    (comp (ref "O41")
      (value "PIC-RPX")
      (footprint "eagle-import:TEMP-PAD")
      (libsource (lib "eagle-import") (part "PIC-RPX"))
    )
    (comp (ref "O42")
      (value "PIC-RPX")
      (footprint "eagle-import:TEMP-PAD")
      (libsource (lib "eagle-import") (part "PIC-RPX"))
    )
    (comp (ref "O43")
      (value "PIC-RPX")
      (footprint "eagle-import:TEMP-PAD")
      (libsource (lib "eagle-import") (part "PIC-RPX"))
    )
    (comp (ref "O44")
      (value "PIC-OUT")
      (footprint "eagle-import:TEMP-PAD")
      (libsource (lib "eagle-import") (part "PIC-OUT"))
    )
    (comp (ref "R29")
      (value "300R")
      (footprint "eagle-import:0603")
      (libsource (lib "eagle-import") (part "R-0603"))
    )
    (comp (ref "R90")
      (value "1k")
      (footprint "eagle-import:0603")
      (libsource (lib "eagle-import") (part "R-0603"))
    )
    (comp (ref "R91")
      (value "10k")
      (footprint "eagle-import:0603")
      (libsource (lib "eagle-import") (part "R-0603"))
    )
    (comp (ref "R92")
      (value "10R")
      (footprint "eagle-import:0603")
      (libsource (lib "eagle-import") (part "R-0603"))
    )
    (comp (ref "R93")
      (value "300R")
      (footprint "eagle-import:0603")
      (libsource (lib "eagle-import") (part "R-0603"))
    )
    (comp (ref "R128")
      (value "10k")
      (footprint "eagle-import:0603")
      (libsource (lib "eagle-import") (part "R-0603"))
    )
    (comp (ref "R130")
      (value "100k")
      (footprint "eagle-import:0603")
      (libsource (lib "eagle-import") (part "R-0603"))
    )
    (comp (ref "R131")
      (value "100k")
      (footprint "eagle-import:0603")
      (libsource (lib "eagle-import") (part "R-0603"))
    )
    (comp (ref "T36")
      (value "PIC-OUT")
      (footprint "eagle-import:TEMP-PAD")
      (libsource (lib "eagle-import") (part "PIC-OUT"))
    )
    (comp (ref "TP4")
      (value "DNP-TestPoint")
      (footprint "eagle-import:TH_ROUND_14MM08MM")
      (libsource (lib "eagle-import") (part "ROUND_SMDTH1.4MM"))
    )
    (comp (ref "TP5")
      (value "DNP-TestPoint")
      (footprint "eagle-import:TH_ROUND_14MM08MM")
      (libsource (lib "eagle-import") (part "ROUND_SMDTH1.4MM"))
    )
    (comp (ref "TP6")
      (value "DNP-TestPoint")
      (footprint "eagle-import:TH_ROUND_14MM08MM")
      (libsource (lib "eagle-import") (part "ROUND_SMDTH1.4MM"))
    )
    (comp (ref "U$47")
      (value "FIDUCIAL")
      (footprint "eagle-import:FIDUCIAL_1MM")
      (libsource (lib "eagle-import") (part "FIDUCIAL"))
    )
    (comp (ref "U$128")
      (value "FIDUCIAL")
      (footprint "eagle-import:FIDUCIAL_1MM")
      (libsource (lib "eagle-import") (part "FIDUCIAL"))
    )
    (comp (ref "U$129")
      (value "FIDUCIAL")
      (footprint "eagle-import:FIDUCIAL_1MM")
      (libsource (lib "eagle-import") (part "FIDUCIAL"))
    )
    (comp (ref "U$130")
      (value "FIDUCIAL")
      (footprint "eagle-import:FIDUCIAL_1MM")
      (libsource (lib "eagle-import") (part "FIDUCIAL"))
    )
    (comp (ref "X1")
      (value "8MHz-5x3.2mm")
      (footprint "eagle-import:7B")
      (libsource (lib "eagle-import") (part "XTAL-7B"))
    )
    (comp (ref "C3")
      (value "100n")
      (footprint "eagle-import:0603")
      (libsource (lib "eagle-import") (part "C-0603"))
    )
    (comp (ref "C4")
      (value "100n")
      (footprint "eagle-import:0603")
      (libsource (lib "eagle-import") (part "C-0603"))
    )
    (comp (ref "C5")
      (value "100n")
      (footprint "eagle-import:0603")
      (libsource (lib "eagle-import") (part "C-0603"))
    )
    (comp (ref "C6")
      (value "100n")
      (footprint "eagle-import:0603")
      (libsource (lib "eagle-import") (part "C-0603"))
    )
    (comp (ref "C7")
      (value "100n")
      (footprint "eagle-import:0603")
      (libsource (lib "eagle-import") (part "C-0603"))
    )
    (comp (ref "C8")
      (value "100n")
      (footprint "eagle-import:0603")
      (libsource (lib "eagle-import") (part "C-0603"))
    )
    (comp (ref "C9")
      (value "10uTA")
      (footprint "eagle-import:1206")
      (libsource (lib "eagle-import") (part "C-1206"))
    )
    (comp (ref "C10")
      (value "10uTA")
      (footprint "eagle-import:1206")
      (libsource (lib "eagle-import") (part "C-1206"))
    )
    (comp (ref "C11")
      (value "10uTA")
      (footprint "eagle-import:1206")
      (libsource (lib "eagle-import") (part "C-1206"))
    )
    (comp (ref "C12")
      (value "10uTA")
      (footprint "eagle-import:1206")
      (libsource (lib "eagle-import") (part "C-1206"))
    )
    (comp (ref "C13")
      (value "10uTA")
      (footprint "eagle-import:1206")
      (libsource (lib "eagle-import") (part "C-1206"))
    )
    (comp (ref "C14")
      (value "10uTA")
      (footprint "eagle-import:1206")
      (libsource (lib "eagle-import") (part "C-1206"))
    )
    (comp (ref "C15")
      (value "10u")
      (footprint "eagle-import:0603")
      (libsource (lib "eagle-import") (part "C-0603"))
    )
    (comp (ref "C16")
      (value "10uTA")
      (footprint "eagle-import:1206")
      (libsource (lib "eagle-import") (part "C-1206"))
    )
    (comp (ref "C17")
      (value "10uTA")
      (footprint "eagle-import:1206")
      (libsource (lib "eagle-import") (part "C-1206"))
    )
    (comp (ref "C18")
      (value "100n")
      (footprint "eagle-import:0603")
      (libsource (lib "eagle-import") (part "C-0603"))
    )
    (comp (ref "C19")
      (value "100n")
      (footprint "eagle-import:0603")
      (libsource (lib "eagle-import") (part "C-0603"))
    )
    (comp (ref "C20")
      (value "10uTA")
      (footprint "eagle-import:1206")
      (libsource (lib "eagle-import") (part "C-1206"))
    )
    (comp (ref "C21")
      (value "1n->10n")
      (footprint "eagle-import:0603")
      (libsource (lib "eagle-import") (part "C-0603"))
    )
    (comp (ref "C75")
      (value "100n")
      (footprint "eagle-import:0603")
      (libsource (lib "eagle-import") (part "C-0603"))
    )
    (comp (ref "C76")
      (value "100n")
      (footprint "eagle-import:0603")
      (libsource (lib "eagle-import") (part "C-0603"))
    )
    (comp (ref "H1")
      (value "CAM-HOLDER")
      (footprint "eagle-import:CAM-HOLDER")
      (libsource (lib "eagle-import") (part "CAM-HOLDER"))
    )
    (comp (ref "H2")
      (value "CAM-HOLDER")
      (footprint "eagle-import:CAM-HOLDER")
      (libsource (lib "eagle-import") (part "CAM-HOLDER"))
    )
    (comp (ref "IC5")
      (value "TLV73315PDBV")
      (footprint "eagle-import:SOT23-5")
      (libsource (lib "eagle-import") (part "TLV73315PDBV"))
    )
    (comp (ref "J1")
      (value "FH12A-24S-0.5SH")
      (footprint "eagle-import:FH12A-24S-05SH")
      (libsource (lib "eagle-import") (part "FH12A-24S-0.5SH"))
    )
    (comp (ref "J2")
      (value "FH12A-24S-0.5SH")
      (footprint "eagle-import:FH12A-24S-05SH")
      (libsource (lib "eagle-import") (part "FH12A-24S-0.5SH"))
    )
    (comp (ref "L1")
      (value "LQM31PN3R3M00L")
      (footprint "eagle-import:1206")
      (libsource (lib "eagle-import") (part "L-1206"))
    )
    (comp (ref "L2")
      (value "LQM31PN3R3M00L")
      (footprint "eagle-import:1206")
      (libsource (lib "eagle-import") (part "L-1206"))
    )
    (comp (ref "L3")
      (value "LQM31PN3R3M00L")
      (footprint "eagle-import:1206")
      (libsource (lib "eagle-import") (part "L-1206"))
    )
    (comp (ref "L4")
      (value "LQM31PN3R3M00L")
      (footprint "eagle-import:1206")
      (libsource (lib "eagle-import") (part "L-1206"))
    )
    (comp (ref "L5")
      (value "LQM31PN3R3M00L")
      (footprint "eagle-import:1206")
      (libsource (lib "eagle-import") (part "L-1206"))
    )
    (comp (ref "L6")
      (value "LQM31PN3R3M00L")
      (footprint "eagle-import:1206")
      (libsource (lib "eagle-import") (part "L-1206"))
    )
    (comp (ref "Q1")
      (value "SSM6P49NU,LFPZ")
      (footprint "eagle-import:MICRO_FET")
      (libsource (lib "eagle-import") (part "SSM6P49PZNU,LF"))
    )
    (comp (ref "R6")
      (value "0R")
      (footprint "eagle-import:0603")
      (libsource (lib "eagle-import") (part "R-0603"))
    )
    (comp (ref "R7")
      (value "0R")
      (footprint "eagle-import:0603")
      (libsource (lib "eagle-import") (part "R-0603"))
    )
    (comp (ref "R8")
      (value "1R")
      (footprint "eagle-import:0805")
      (libsource (lib "eagle-import") (part "R-0805"))
    )
    (comp (ref "R9")
      (value "1M")
      (footprint "eagle-import:0603")
      (libsource (lib "eagle-import") (part "R-0603"))
    )
    (comp (ref "R10")
      (value "100k")
      (footprint "eagle-import:0603")
      (libsource (lib "eagle-import") (part "R-0603"))
    )
    (comp (ref "R11")
      (value "10k")
      (footprint "eagle-import:0603")
      (libsource (lib "eagle-import") (part "R-0603"))
    )
    (comp (ref "R12")
      (value "100k")
      (footprint "eagle-import:0603")
      (libsource (lib "eagle-import") (part "R-0603"))
    )
    (comp (ref "R13")
      (value "10k")
      (footprint "eagle-import:0603")
      (libsource (lib "eagle-import") (part "R-0603"))
    )
    (comp (ref "R14")
      (value "10k")
      (footprint "eagle-import:0603")
      (libsource (lib "eagle-import") (part "R-0603"))
    )
    (comp (ref "R15")
      (value "10k")
      (footprint "eagle-import:0603")
      (libsource (lib "eagle-import") (part "R-0603"))
    )
    (comp (ref "R16")
      (value "100k")
      (footprint "eagle-import:0603")
      (libsource (lib "eagle-import") (part "R-0603"))
    )
    (comp (ref "R126")
      (value "0R")
      (footprint "eagle-import:0603")
      (libsource (lib "eagle-import") (part "R-0603"))
    )
    (comp (ref "T16")
      (value "PIC-RPX")
      (footprint "eagle-import:TEMP-PAD")
      (libsource (lib "eagle-import") (part "PIC-RPX"))
    )
    (comp (ref "T17")
      (value "PIC-RPX")
      (footprint "eagle-import:TEMP-PAD")
      (libsource (lib "eagle-import") (part "PIC-RPX"))
    )
    (comp (ref "T18")
      (value "PIC-RPX")
      (footprint "eagle-import:TEMP-PAD")
      (libsource (lib "eagle-import") (part "PIC-RPX"))
    )
    (comp (ref "T19")
      (value "PIC-RPX")
      (footprint "eagle-import:TEMP-PAD")
      (libsource (lib "eagle-import") (part "PIC-RPX"))
    )
    (comp (ref "T20")
      (value "PIC-OUT")
      (footprint "eagle-import:TEMP-PAD")
      (libsource (lib "eagle-import") (part "PIC-OUT"))
    )
    (comp (ref "T21")
      (value "PIC-OUT")
      (footprint "eagle-import:TEMP-PAD")
      (libsource (lib "eagle-import") (part "PIC-OUT"))
    )
    (comp (ref "T30")
      (value "PIC-OUT")
      (footprint "eagle-import:TEMP-PAD")
      (libsource (lib "eagle-import") (part "PIC-OUT"))
    )
    (comp (ref "C22")
      (value "4u7/50")
      (footprint "eagle-import:1206")
      (libsource (lib "eagle-import") (part "C-1206"))
    )
    (comp (ref "C23")
      (value "4u7/50")
      (footprint "eagle-import:1206")
      (libsource (lib "eagle-import") (part "C-1206"))
    )
    (comp (ref "C24")
      (value "1n")
      (footprint "eagle-import:0603")
      (libsource (lib "eagle-import") (part "C-0603"))
    )
    (comp (ref "C25")
      (value "470n/25")
      (footprint "eagle-import:0603")
      (libsource (lib "eagle-import") (part "C-0603"))
    )
    (comp (ref "C26")
      (value "10p")
      (footprint "eagle-import:0603")
      (libsource (lib "eagle-import") (part "C-0603"))
    )
    (comp (ref "C29")
      (value "4u7/50")
      (footprint "eagle-import:1206")
      (libsource (lib "eagle-import") (part "C-1206"))
    )
    (comp (ref "C30")
      (value "47u/6.3")
      (footprint "eagle-import:1206")
      (libsource (lib "eagle-import") (part "C-1206"))
    )
    (comp (ref "C31")
      (value "47uTC")
      (footprint "eagle-import:CT-C")
      (libsource (lib "eagle-import") (part "CT-C"))
    )
    (comp (ref "C33")
      (value "100n")
      (footprint "eagle-import:0603")
      (libsource (lib "eagle-import") (part "C-0603"))
    )
    (comp (ref "C34")
      (value "1n")
      (footprint "eagle-import:0603")
      (libsource (lib "eagle-import") (part "C-0603"))
    )
    (comp (ref "C35")
      (value "100n")
      (footprint "eagle-import:0603")
      (libsource (lib "eagle-import") (part "C-0603"))
    )
    (comp (ref "C36")
      (value "100n")
      (footprint "eagle-import:0603")
      (libsource (lib "eagle-import") (part "C-0603"))
    )
    (comp (ref "C39")
      (value "100n")
      (footprint "eagle-import:0603")
      (libsource (lib "eagle-import") (part "C-0603"))
    )
    (comp (ref "C41")
      (value "100n")
      (footprint "eagle-import:0603")
      (libsource (lib "eagle-import") (part "C-0603"))
    )
    (comp (ref "C62")
      (value "1n")
      (footprint "eagle-import:0603")
      (libsource (lib "eagle-import") (part "C-0603"))
    )
    (comp (ref "C63")
      (value "1n")
      (footprint "eagle-import:0603")
      (libsource (lib "eagle-import") (part "C-0603"))
    )
    (comp (ref "C64")
      (value "100n")
      (footprint "eagle-import:0603")
      (libsource (lib "eagle-import") (part "C-0603"))
    )
    (comp (ref "C65")
      (value "1n")
      (footprint "eagle-import:0603")
      (libsource (lib "eagle-import") (part "C-0603"))
    )
    (comp (ref "C66")
      (value "10n")
      (footprint "eagle-import:0603")
      (libsource (lib "eagle-import") (part "C-0603"))
    )
    (comp (ref "C67")
      (value "10u")
      (footprint "eagle-import:0603")
      (libsource (lib "eagle-import") (part "C-0603"))
    )
    (comp (ref "C68")
      (value "1n->10n")
      (footprint "eagle-import:0603")
      (libsource (lib "eagle-import") (part "C-0603"))
    )
    (comp (ref "C69")
      (value "1n")
      (footprint "eagle-import:0603")
      (libsource (lib "eagle-import") (part "C-0603"))
    )
    (comp (ref "C70")
      (value "1n")
      (footprint "eagle-import:0603")
      (libsource (lib "eagle-import") (part "C-0603"))
    )
    (comp (ref "C83")
      (value "220u/25V")
      (footprint "eagle-import:CAP_8MM_DIA_SMT")
      (libsource (lib "eagle-import") (part "CAP-ELEC-SMD-8MM"))
    )
    (comp (ref "C84")
      (value "220u/25V")
      (footprint "eagle-import:CAP_8MM_DIA_SMT")
      (libsource (lib "eagle-import") (part "CAP-ELEC-SMD-8MM"))
    )
    (comp (ref "C86")
      (value "10uTA")
      (footprint "eagle-import:1206")
      (libsource (lib "eagle-import") (part "C-1206"))
    )
    (comp (ref "D2")
      (value "SMLVT3V3")
      (footprint "eagle-import:SMA")
      (libsource (lib "eagle-import") (part "SMLVT3V3"))
    )
    (comp (ref "D3")
      (value "P6SMB20A")
      (footprint "eagle-import:SMB")
      (libsource (lib "eagle-import") (part "P6SMB"))
    )
    (comp (ref "D4")
      (value "P6SMB20A")
      (footprint "eagle-import:SMB")
      (libsource (lib "eagle-import") (part "P6SMB"))
    )
    (comp (ref "D7")
      (value "SS14")
      (footprint "eagle-import:SMA")
      (libsource (lib "eagle-import") (part "DS-SMA"))
    )
    (comp (ref "F1")
      (value "T1A-LITTLEFUSE0154")
      (footprint "eagle-import:LITTLEFUSE0154")
      (libsource (lib "eagle-import") (part "POJISTKA-LITTLEFUSE0154"))
    )
    (comp (ref "IC6")
      (value "MIC841LYC")
      (footprint "eagle-import:SC-70-5")
      (libsource (lib "eagle-import") (part "MIC841LYC"))
    )
    (comp (ref "IC8")
      (value "LT3971EMSE")
      (footprint "eagle-import:MSOP10EXP")
      (libsource (lib "eagle-import") (part "LT3971EMSE"))
    )
    (comp (ref "IC10")
      (value "MAX9938HEUK+T")
      (footprint "eagle-import:SOT23-5")
      (libsource (lib "eagle-import") (part "TSM9938HEUK+T"))
    )
    (comp (ref "IC12")
      (value "SN65HVD12D")
      (footprint "eagle-import:SO08")
      (libsource (lib "eagle-import") (part "SN65HVD3082ED"))
    )
    (comp (ref "IC14")
      (value "TPD2E001DZDR")
      (footprint "eagle-import:SOT-143")
      (libsource (lib "eagle-import") (part "SR05.TCT"))
    )
    (comp (ref "IC16")
      (value "MCP6042-I/MS")
      (footprint "eagle-import:MSOP-08")
      (libsource (lib "eagle-import") (part "MCP6042-I/MS"))
    )
    (comp (ref "J3")
      (value "RJ-8PIN")
      (footprint "eagle-import:RJ-8PIN")
      (libsource (lib "eagle-import") (part "RJ-8PIN"))
    )
    (comp (ref "J4")
      (value "RJ-8PIN")
      (footprint "eagle-import:RJ-8PIN")
      (libsource (lib "eagle-import") (part "RJ-8PIN"))
    )
    (comp (ref "JP1")
      (value "JP3CLOSE12")
      (footprint "eagle-import:JP3CLOSE12")
      (libsource (lib "eagle-import") (part "JP3CLOSE12"))
    )
    (comp (ref "L7")
      (value "HI1206T500R")
      (footprint "eagle-import:1206")
      (libsource (lib "eagle-import") (part "L-1206"))
    )
    (comp (ref "L8")
      (value "HI1206T500R")
      (footprint "eagle-import:1206")
      (libsource (lib "eagle-import") (part "L-1206"))
    )
    (comp (ref "L9")
      (value "NR6028T4R7M")
      (footprint "eagle-import:NR6028")
      (libsource (lib "eagle-import") (part "NR6028"))
    )
    (comp (ref "L10")
      (value "HI1206T500R")
      (footprint "eagle-import:1206")
      (libsource (lib "eagle-import") (part "L-1206"))
    )
    (comp (ref "L11")
      (value "HI1206T500R")
      (footprint "eagle-import:1206")
      (libsource (lib "eagle-import") (part "L-1206"))
    )
    (comp (ref "L12")
      (value "HI1206T500R")
      (footprint "eagle-import:1206")
      (libsource (lib "eagle-import") (part "L-1206"))
    )
    (comp (ref "Q2")
      (value "SSM6P49NU,LFPZ")
      (footprint "eagle-import:MICRO_FET")
      (libsource (lib "eagle-import") (part "SSM6P49PZNU,LF"))
    )
    (comp (ref "Q4")
      (value "FDG6303N")
      (footprint "eagle-import:SC70-6")
      (libsource (lib "eagle-import") (part "FDG6303N"))
    )
    (comp (ref "Q5")
      (value "FDC6506P")
      (footprint "eagle-import:SSOT-6")
      (libsource (lib "eagle-import") (part "FDC6506D"))
    )
    (comp (ref "R17")
      (value "47k")
      (footprint "eagle-import:0603")
      (libsource (lib "eagle-import") (part "R-0603"))
    )
    (comp (ref "R19")
      (value "560k")
      (footprint "eagle-import:0603")
      (libsource (lib "eagle-import") (part "R-0603"))
    )
    (comp (ref "R20")
      (value "1M")
      (footprint "eagle-import:0603")
      (libsource (lib "eagle-import") (part "R-0603"))
    )
    (comp (ref "R21")
      (value "1M")
      (footprint "eagle-import:0603")
      (libsource (lib "eagle-import") (part "R-0603"))
    )
    (comp (ref "R22")
      (value "4M99")
      (footprint "eagle-import:0603")
      (libsource (lib "eagle-import") (part "R-0603"))
    )
    (comp (ref "R23")
      (value "0R/1M")
      (footprint "eagle-import:0603")
      (libsource (lib "eagle-import") (part "R-0603"))
    )
    (comp (ref "R24")
      (value "100k")
      (footprint "eagle-import:0603")
      (libsource (lib "eagle-import") (part "R-0603"))
    )
    (comp (ref "R28")
      (value "100R")
      (footprint "eagle-import:0603")
      (libsource (lib "eagle-import") (part "R-0603"))
    )
    (comp (ref "R30")
      (value "1M")
      (footprint "eagle-import:0603")
      (libsource (lib "eagle-import") (part "R-0603"))
    )
    (comp (ref "R31")
      (value "1M")
      (footprint "eagle-import:0603")
      (libsource (lib "eagle-import") (part "R-0603"))
    )
    (comp (ref "R32")
      (value "1M")
      (footprint "eagle-import:0603")
      (libsource (lib "eagle-import") (part "R-0603"))
    )
    (comp (ref "R33")
      (value "4M99")
      (footprint "eagle-import:0603")
      (libsource (lib "eagle-import") (part "R-0603"))
    )
    (comp (ref "R34")
      (value "1M")
      (footprint "eagle-import:0603")
      (libsource (lib "eagle-import") (part "R-0603"))
    )
    (comp (ref "R35")
      (value "1k")
      (footprint "eagle-import:0805")
      (libsource (lib "eagle-import") (part "R-0805"))
    )
    (comp (ref "R36")
      (value "1k")
      (footprint "eagle-import:0805")
      (libsource (lib "eagle-import") (part "R-0805"))
    )
    (comp (ref "R37")
      (value "1k")
      (footprint "eagle-import:0805")
      (libsource (lib "eagle-import") (part "R-0805"))
    )
    (comp (ref "R38")
      (value "1k")
      (footprint "eagle-import:0805")
      (libsource (lib "eagle-import") (part "R-0805"))
    )
    (comp (ref "R39")
      (value "0.025R")
      (footprint "eagle-import:0805")
      (libsource (lib "eagle-import") (part "R-0805"))
    )
    (comp (ref "R40")
      (value "300k")
      (footprint "eagle-import:0603")
      (libsource (lib "eagle-import") (part "R-0603"))
    )
    (comp (ref "R41")
      (value "1M")
      (footprint "eagle-import:0603")
      (libsource (lib "eagle-import") (part "R-0603"))
    )
    (comp (ref "R42")
      (value "1M")
      (footprint "eagle-import:0603")
      (libsource (lib "eagle-import") (part "R-0603"))
    )
    (comp (ref "R43")
      (value "300k")
      (footprint "eagle-import:0603")
      (libsource (lib "eagle-import") (part "R-0603"))
    )
    (comp (ref "R44")
      (value "1M")
      (footprint "eagle-import:0603")
      (libsource (lib "eagle-import") (part "R-0603"))
    )
    (comp (ref "R45")
      (value "1M")
      (footprint "eagle-import:0603")
      (libsource (lib "eagle-import") (part "R-0603"))
    )
    (comp (ref "R46")
      (value "560k")
      (footprint "eagle-import:0603")
      (libsource (lib "eagle-import") (part "R-0603"))
    )
    (comp (ref "R47")
      (value "100k")
      (footprint "eagle-import:0603")
      (libsource (lib "eagle-import") (part "R-0603"))
    )
    (comp (ref "R48")
      (value "1M")
      (footprint "eagle-import:0603")
      (libsource (lib "eagle-import") (part "R-0603"))
    )
    (comp (ref "R49")
      (value "1M")
      (footprint "eagle-import:0603")
      (libsource (lib "eagle-import") (part "R-0603"))
    )
    (comp (ref "R65")
      (value "1M")
      (footprint "eagle-import:0603")
      (libsource (lib "eagle-import") (part "R-0603"))
    )
    (comp (ref "R71")
      (value "10k")
      (footprint "eagle-import:0603")
      (libsource (lib "eagle-import") (part "R-0603"))
    )
    (comp (ref "R72")
      (value "1M")
      (footprint "eagle-import:0603")
      (libsource (lib "eagle-import") (part "R-0603"))
    )
    (comp (ref "R73")
      (value "1M")
      (footprint "eagle-import:0603")
      (libsource (lib "eagle-import") (part "R-0603"))
    )
    (comp (ref "R75")
      (value "100k")
      (footprint "eagle-import:0603")
      (libsource (lib "eagle-import") (part "R-0603"))
    )
    (comp (ref "R77")
      (value "47k")
      (footprint "eagle-import:0603")
      (libsource (lib "eagle-import") (part "R-0603"))
    )
    (comp (ref "R82")
      (value "1M")
      (footprint "eagle-import:0603")
      (libsource (lib "eagle-import") (part "R-0603"))
    )
    (comp (ref "R87")
      (value "1M")
      (footprint "eagle-import:0603")
      (libsource (lib "eagle-import") (part "R-0603"))
    )
    (comp (ref "R94")
      (value "180k")
      (footprint "eagle-import:0603")
      (libsource (lib "eagle-import") (part "R-0603"))
    )
    (comp (ref "R95")
      (value "4M99")
      (footprint "eagle-import:0603")
      (libsource (lib "eagle-import") (part "R-0603"))
    )
    (comp (ref "R96")
      (value "560k")
      (footprint "eagle-import:0603")
      (libsource (lib "eagle-import") (part "R-0603"))
    )
    (comp (ref "R97")
      (value "180k")
      (footprint "eagle-import:0603")
      (libsource (lib "eagle-import") (part "R-0603"))
    )
    (comp (ref "R98")
      (value "4M99")
      (footprint "eagle-import:0603")
      (libsource (lib "eagle-import") (part "R-0603"))
    )
    (comp (ref "R99")
      (value "560k")
      (footprint "eagle-import:0603")
      (libsource (lib "eagle-import") (part "R-0603"))
    )
    (comp (ref "R100")
      (value "2k2")
      (footprint "eagle-import:0603")
      (libsource (lib "eagle-import") (part "R-0603"))
    )
    (comp (ref "R101")
      (value "2k2")
      (footprint "eagle-import:0603")
      (libsource (lib "eagle-import") (part "R-0603"))
    )
    (comp (ref "R102")
      (value "1k")
      (footprint "eagle-import:0603")
      (libsource (lib "eagle-import") (part "R-0603"))
    )
    (comp (ref "R103")
      (value "300R")
      (footprint "eagle-import:0603")
      (libsource (lib "eagle-import") (part "R-0603"))
    )
    (comp (ref "R104")
      (value "1R")
      (footprint "eagle-import:0805")
      (libsource (lib "eagle-import") (part "R-0805"))
    )
    (comp (ref "R105")
      (value "1R")
      (footprint "eagle-import:0805")
      (libsource (lib "eagle-import") (part "R-0805"))
    )
    (comp (ref "R106")
      (value "1R")
      (footprint "eagle-import:0805")
      (libsource (lib "eagle-import") (part "R-0805"))
    )
    (comp (ref "R107")
      (value "100k")
      (footprint "eagle-import:0603")
      (libsource (lib "eagle-import") (part "R-0603"))
    )
    (comp (ref "R108")
      (value "10R")
      (footprint "eagle-import:0603")
      (libsource (lib "eagle-import") (part "R-0603"))
    )
    (comp (ref "R109")
      (value "10R")
      (footprint "eagle-import:0603")
      (libsource (lib "eagle-import") (part "R-0603"))
    )
    (comp (ref "R129")
      (value "DNP/0R")
      (footprint "eagle-import:0603")
      (libsource (lib "eagle-import") (part "R-0603"))
    )
    (comp (ref "R132")
      (value "1M")
      (footprint "eagle-import:0603")
      (libsource (lib "eagle-import") (part "R-0603"))
    )
    (comp (ref "T3")
      (value "PIC-RPX")
      (footprint "eagle-import:TEMP-PAD")
      (libsource (lib "eagle-import") (part "PIC-RPX"))
    )
    (comp (ref "T5")
      (value "PIC-OUT")
      (footprint "eagle-import:TEMP-PAD")
      (libsource (lib "eagle-import") (part "PIC-OUT"))
    )
    (comp (ref "T7")
      (value "PIC-OUT")
      (footprint "eagle-import:TEMP-PAD")
      (libsource (lib "eagle-import") (part "PIC-OUT"))
    )
    (comp (ref "T13")
      (value "PIC-RPX")
      (footprint "eagle-import:TEMP-PAD")
      (libsource (lib "eagle-import") (part "PIC-RPX"))
    )
    (comp (ref "T14")
      (value "PIC-RPX")
      (footprint "eagle-import:TEMP-PAD")
      (libsource (lib "eagle-import") (part "PIC-RPX"))
    )
    (comp (ref "T15")
      (value "PIC-OUT")
      (footprint "eagle-import:TEMP-PAD")
      (libsource (lib "eagle-import") (part "PIC-OUT"))
    )
    (comp (ref "T31")
      (value "PIC-OUT")
      (footprint "eagle-import:TEMP-PAD")
      (libsource (lib "eagle-import") (part "PIC-OUT"))
    )
    (comp (ref "T32")
      (value "PIC-OUT")
      (footprint "eagle-import:TEMP-PAD")
      (libsource (lib "eagle-import") (part "PIC-OUT"))
    )
    (comp (ref "T33")
      (value "PIC-OUT")
      (footprint "eagle-import:TEMP-PAD")
      (libsource (lib "eagle-import") (part "PIC-OUT"))
    )
    (comp (ref "T37")
      (value "PIN-AN")
      (footprint "eagle-import:TEMP-PAD")
      (libsource (lib "eagle-import") (part "PIN-AN"))
    )
    (comp (ref "T38")
      (value "PIN-AN")
      (footprint "eagle-import:TEMP-PAD")
      (libsource (lib "eagle-import") (part "PIN-AN"))
    )
    (comp (ref "T39")
      (value "PIN-AN")
      (footprint "eagle-import:TEMP-PAD")
      (libsource (lib "eagle-import") (part "PIN-AN"))
    )
    (comp (ref "T45")
      (value "PIC-RPX")
      (footprint "eagle-import:TEMP-PAD")
      (libsource (lib "eagle-import") (part "PIC-RPX"))
    )
    (comp (ref "TP2")
      (value "DNP-TestPoint")
      (footprint "eagle-import:TH_ROUND_14MM08MM")
      (libsource (lib "eagle-import") (part "ROUND_SMDTH1.4MM"))
    )
  )
  (nets
    (net (code "1") (name "+3.3V") (class "Default")
      (node (ref "C15") (pin "1") (pinfunction "1_1") (pintype "passive"))
      (node (ref "C21") (pin "1") (pinfunction "1_1") (pintype "passive"))
      (node (ref "C47") (pin "1") (pinfunction "1_1") (pintype "passive"))
      (node (ref "C48") (pin "1") (pinfunction "1_1") (pintype "passive"))
      (node (ref "C49") (pin "1") (pinfunction "1_1") (pintype "passive"))
      (node (ref "C50") (pin "1") (pinfunction "1_1") (pintype "passive"))
      (node (ref "C51") (pin "1") (pinfunction "1_1") (pintype "passive"))
      (node (ref "C52") (pin "1") (pinfunction "1_1") (pintype "passive"))
      (node (ref "C68") (pin "1") (pinfunction "1_1") (pintype "passive"))
      (node (ref "C69") (pin "1") (pinfunction "1_1") (pintype "passive"))
      (node (ref "C70") (pin "1") (pinfunction "1_1") (pintype "passive"))
      (node (ref "C81") (pin "+") (pinfunction "+_+") (pintype "passive"))
      (node (ref "IC1") (pin "16") (pinfunction "VDD3_16") (pintype "input"))
      (node (ref "IC1") (pin "2") (pinfunction "VDD2_2") (pintype "input"))
      (node (ref "IC1") (pin "37") (pinfunction "VDD4_37") (pintype "input"))
      (node (ref "IC1") (pin "46") (pinfunction "VDD5_46") (pintype "input"))
      (node (ref "IC1") (pin "55") (pinfunction "VUSB3V3_55") (pintype "input"))
      (node (ref "IC1") (pin "62") (pinfunction "VDD6_62") (pintype "input"))
      (node (ref "IC1") (pin "86") (pinfunction "VDD1_86") (pintype "input"))
      (node (ref "J14") (pin "2") (pinfunction "2_2") (pintype "passive"))
      (node (ref "J17") (pin "2") (pinfunction "2_2") (pintype "passive"))
      (node (ref "L13") (pin "1") (pinfunction "1_1") (pintype "passive"))
      (node (ref "R103") (pin "2") (pinfunction "2_2") (pintype "passive"))
      (node (ref "R104") (pin "2") (pinfunction "2_2") (pintype "passive"))
      (node (ref "R105") (pin "2") (pinfunction "2_2") (pintype "passive"))
      (node (ref "R106") (pin "2") (pinfunction "2_2") (pintype "passive"))
      (node (ref "R129") (pin "1") (pinfunction "1_1") (pintype "passive"))
      (node (ref "R28") (pin "2") (pinfunction "2_2") (pintype "passive"))
      (node (ref "R65") (pin "1") (pinfunction "1_1") (pintype "passive"))
      (node (ref "R66") (pin "2") (pinfunction "2_2") (pintype "passive"))
      (node (ref "R74") (pin "2") (pinfunction "2_2") (pintype "passive"))
      (node (ref "R8") (pin "2") (pinfunction "2_2") (pintype "passive"))
      (node (ref "R81") (pin "2") (pinfunction "2_2") (pintype "passive"))
      (node (ref "R82") (pin "1") (pinfunction "1_1") (pintype "passive"))
      (node (ref "R87") (pin "1") (pinfunction "1_1") (pintype "passive"))
      (node (ref "R89") (pin "2") (pinfunction "2_2") (pintype "passive"))
      (node (ref "R9") (pin "2") (pinfunction "2_2") (pintype "passive"))
      (node (ref "R91") (pin "2") (pinfunction "2_2") (pintype "passive"))
    )
    (net (code "2") (name "+3.3V{slash}1") (class "Default")
      (node (ref "C1") (pin "1") (pinfunction "1_1") (pintype "passive"))
      (node (ref "C2") (pin "1") (pinfunction "1_1") (pintype "passive"))
      (node (ref "C28") (pin "1") (pinfunction "1_1") (pintype "passive"))
      (node (ref "C87") (pin "1") (pinfunction "1_1") (pintype "passive"))
      (node (ref "IC11") (pin "2") (pinfunction "A1_2") (pintype "input"))
      (node (ref "IC11") (pin "8") (pinfunction "VCC_8") (pintype "input"))
      (node (ref "IC2") (pin "37") (pinfunction "VCC_37") (pintype "input"))
      (node (ref "IC3") (pin "20") (pinfunction "VCC_20") (pintype "bidirectional"))
      (node (ref "IC4") (pin "20") (pinfunction "VCC_20") (pintype "bidirectional"))
      (node (ref "IC7") (pin "8") (pinfunction "VCC_8") (pintype "input"))
      (node (ref "Q2") (pin "3") (pinfunction "D_3") (pintype "passive"))
      (node (ref "Q2") (pin "P2") (pinfunction "D1_P2") (pintype "passive"))
      (node (ref "R18") (pin "1") (pinfunction "1_1") (pintype "passive"))
      (node (ref "R26") (pin "1") (pinfunction "1_1") (pintype "passive"))
      (node (ref "R27") (pin "1") (pinfunction "1_1") (pintype "passive"))
      (node (ref "R3") (pin "2") (pinfunction "2_2") (pintype "passive"))
      (node (ref "R4") (pin "2") (pinfunction "2_2") (pintype "passive"))
    )
    (net (code "3") (name "+3.3V{slash}2") (class "Default")
      (node (ref "C41") (pin "1") (pinfunction "1_1") (pintype "passive"))
      (node (ref "C86") (pin "1") (pinfunction "1_1") (pintype "passive"))
      (node (ref "IC12") (pin "8") (pinfunction "VCC_8") (pintype "input"))
      (node (ref "Q1") (pin "3") (pinfunction "D_3") (pintype "passive"))
      (node (ref "Q1") (pin "P2") (pinfunction "D1_P2") (pintype "passive"))
      (node (ref "R30") (pin "2") (pinfunction "2_2") (pintype "passive"))
      (node (ref "R34") (pin "1") (pinfunction "1_1") (pintype "passive"))
      (node (ref "R72") (pin "1") (pinfunction "1_1") (pintype "passive"))
      (node (ref "R73") (pin "2") (pinfunction "2_2") (pintype "passive"))
    )
    (net (code "4") (name "+3.3V{slash}VPS") (class "Default")
      (node (ref "C27") (pin "1") (pinfunction "1_1") (pintype "passive"))
      (node (ref "C82") (pin "1") (pinfunction "1_1") (pintype "passive"))
      (node (ref "IC9") (pin "3") (pinfunction "/WP_3") (pintype "input"))
      (node (ref "IC9") (pin "7") (pinfunction "/HOLD_7") (pintype "input"))
      (node (ref "IC9") (pin "8") (pinfunction "VCC_8") (pintype "input"))
      (node (ref "J11") (pin "4") (pinfunction "VDD_4") (pintype "passive"))
      (node (ref "J15") (pin "1") (pinfunction "1_1") (pintype "passive"))
      (node (ref "Q2") (pin "6") (pinfunction "D_6") (pintype "passive"))
      (node (ref "Q2") (pin "P1") (pinfunction "D1_P1") (pintype "passive"))
      (node (ref "R25") (pin "2") (pinfunction "2_2") (pintype "passive"))
    )
    (net (code "5") (name "1.5V-CAM") (class "Default")
      (node (ref "L5") (pin "1") (pinfunction "1_1") (pintype "passive"))
      (node (ref "L6") (pin "2") (pinfunction "2_2") (pintype "passive"))
      (node (ref "R126") (pin "1") (pinfunction "1_1") (pintype "passive"))
    )
    (net (code "6") (name "3.3V{slash}CAM") (class "Default")
      (node (ref "C16") (pin "1") (pinfunction "1_1") (pintype "passive"))
      (node (ref "C17") (pin "1") (pinfunction "1_1") (pintype "passive"))
      (node (ref "C18") (pin "1") (pinfunction "1_1") (pintype "passive"))
      (node (ref "IC5") (pin "1") (pinfunction "IN_1") (pintype "input"))
      (node (ref "IC5") (pin "3") (pinfunction "EN_3") (pintype "input"))
      (node (ref "L1") (pin "1") (pinfunction "1_1") (pintype "passive"))
      (node (ref "L2") (pin "2") (pinfunction "2_2") (pintype "passive"))
      (node (ref "L3") (pin "1") (pinfunction "1_1") (pintype "passive"))
      (node (ref "L4") (pin "2") (pinfunction "2_2") (pintype "passive"))
      (node (ref "Q1") (pin "6") (pinfunction "D_6") (pintype "passive"))
      (node (ref "Q1") (pin "P1") (pinfunction "D1_P1") (pintype "passive"))
      (node (ref "R11") (pin "2") (pinfunction "2_2") (pintype "passive"))
      (node (ref "R12") (pin "2") (pinfunction "2_2") (pintype "passive"))
      (node (ref "R13") (pin "2") (pinfunction "2_2") (pintype "passive"))
      (node (ref "R14") (pin "2") (pinfunction "2_2") (pintype "passive"))
      (node (ref "R15") (pin "2") (pinfunction "2_2") (pintype "passive"))
      (node (ref "R16") (pin "2") (pinfunction "2_2") (pintype "passive"))
    )
    (net (code "7") (name "A+") (class "Default")
      (node (ref "J3") (pin "4") (pinfunction "4_4") (pintype "passive"))
      (node (ref "J4") (pin "4") (pinfunction "4_4") (pintype "passive"))
      (node (ref "L8") (pin "2") (pinfunction "2_2") (pintype "passive"))
    )
    (net (code "8") (name "A++") (class "Default")
      (node (ref "IC12") (pin "6") (pinfunction "A_6") (pintype "bidirectional"))
      (node (ref "IC14") (pin "3") (pinfunction "3_3") (pintype "passive"))
      (node (ref "R109") (pin "2") (pinfunction "2_2") (pintype "passive"))
      (node (ref "R32") (pin "2") (pinfunction "2_2") (pintype "passive"))
      (node (ref "R34") (pin "2") (pinfunction "2_2") (pintype "passive"))
    )
    (net (code "9") (name "A0") (class "Default")
      (node (ref "IC2") (pin "20") (pinfunction "A5_20") (pintype "input"))
      (node (ref "IC3") (pin "12") (pinfunction "Q7_12") (pintype "tri_state"))
    )
    (net (code "10") (name "A1") (class "Default")
      (node (ref "IC2") (pin "21") (pinfunction "A4_21") (pintype "input"))
      (node (ref "IC3") (pin "13") (pinfunction "Q6_13") (pintype "tri_state"))
    )
    (net (code "11") (name "A2") (class "Default")
      (node (ref "IC2") (pin "22") (pinfunction "A3_22") (pintype "input"))
      (node (ref "IC3") (pin "14") (pinfunction "Q5_14") (pintype "tri_state"))
    )
    (net (code "12") (name "A3") (class "Default")
      (node (ref "IC2") (pin "23") (pinfunction "A2_23") (pintype "input"))
      (node (ref "IC3") (pin "15") (pinfunction "Q4_15") (pintype "tri_state"))
    )
    (net (code "13") (name "A4") (class "Default")
      (node (ref "IC2") (pin "24") (pinfunction "A1_24") (pintype "input"))
      (node (ref "IC3") (pin "16") (pinfunction "Q3_16") (pintype "tri_state"))
    )
    (net (code "14") (name "A5") (class "Default")
      (node (ref "IC2") (pin "25") (pinfunction "A0_25") (pintype "input"))
      (node (ref "IC3") (pin "17") (pinfunction "Q2_17") (pintype "tri_state"))
    )
    (net (code "15") (name "A6") (class "Default")
      (node (ref "IC2") (pin "45") (pinfunction "A-1/D15_45") (pintype "tri_state"))
      (node (ref "IC3") (pin "18") (pinfunction "Q1_18") (pintype "tri_state"))
    )
    (net (code "16") (name "A7") (class "Default")
      (node (ref "IC2") (pin "48") (pinfunction "A16_48") (pintype "input"))
      (node (ref "IC3") (pin "19") (pinfunction "Q0_19") (pintype "tri_state"))
    )
    (net (code "17") (name "A8") (class "Default")
      (node (ref "IC2") (pin "19") (pinfunction "A6_19") (pintype "input"))
      (node (ref "IC4") (pin "19") (pinfunction "Q0_19") (pintype "tri_state"))
    )
    (net (code "18") (name "A9") (class "Default")
      (node (ref "IC2") (pin "18") (pinfunction "A7_18") (pintype "input"))
      (node (ref "IC4") (pin "18") (pinfunction "Q1_18") (pintype "tri_state"))
    )
    (net (code "19") (name "A10") (class "Default")
      (node (ref "IC2") (pin "17") (pinfunction "A17_17") (pintype "input"))
      (node (ref "IC4") (pin "17") (pinfunction "Q2_17") (pintype "tri_state"))
    )
    (net (code "20") (name "A11") (class "Default")
      (node (ref "IC2") (pin "16") (pinfunction "A18_16") (pintype "input"))
      (node (ref "IC4") (pin "16") (pinfunction "Q3_16") (pintype "tri_state"))
    )
    (net (code "21") (name "A12") (class "Default")
      (node (ref "IC2") (pin "9") (pinfunction "A19_9") (pintype "input"))
      (node (ref "IC4") (pin "15") (pinfunction "Q4_15") (pintype "tri_state"))
    )
    (net (code "22") (name "A13") (class "Default")
      (node (ref "IC2") (pin "8") (pinfunction "A8_8") (pintype "input"))
      (node (ref "IC4") (pin "14") (pinfunction "Q5_14") (pintype "tri_state"))
    )
    (net (code "23") (name "A14") (class "Default")
      (node (ref "IC2") (pin "7") (pinfunction "A9_7") (pintype "input"))
      (node (ref "IC4") (pin "13") (pinfunction "Q6_13") (pintype "tri_state"))
    )
    (net (code "24") (name "A15") (class "Default")
      (node (ref "IC2") (pin "6") (pinfunction "A10_6") (pintype "input"))
      (node (ref "R120") (pin "2") (pinfunction "2_2") (pintype "passive"))
      (node (ref "R121") (pin "2") (pinfunction "2_2") (pintype "passive"))
    )
    (net (code "25") (name "A15-1") (class "Default")
      (node (ref "IC4") (pin "12") (pinfunction "Q7_12") (pintype "tri_state"))
      (node (ref "R120") (pin "1") (pinfunction "1_1") (pintype "passive"))
    )
    (net (code "26") (name "A15-2") (class "Default")
      (node (ref "IC1") (pin "42") (pinfunction "AN13/RB13_42") (pintype "bidirectional"))
      (node (ref "R121") (pin "1") (pinfunction "1_1") (pintype "passive"))
      (node (ref "TP3") (pin "P$1") (pinfunction "TP_P$1") (pintype "passive"))
    )
    (net (code "27") (name "A16") (class "Default")
      (node (ref "IC1") (pin "32") (pinfunction "AN8/RPB8/CTED10/RB8_32") (pintype "bidirectional"))
      (node (ref "IC2") (pin "5") (pinfunction "A11_5") (pintype "input"))
    )
    (net (code "28") (name "A17") (class "Default")
      (node (ref "IC1") (pin "33") (pinfunction "AN9/RPB9/CTED4/RB9_33") (pintype "bidirectional"))
      (node (ref "IC2") (pin "4") (pinfunction "A12_4") (pintype "input"))
    )
    (net (code "29") (name "A18") (class "Default")
      (node (ref "IC1") (pin "34") (pinfunction "CVREFOUT/AN10/RPB10/PMA13/CTED11/RB10_34") (pintype "bidirectional"))
      (node (ref "IC2") (pin "3") (pinfunction "A13_3") (pintype "input"))
    )
    (net (code "30") (name "A19") (class "Default")
      (node (ref "IC1") (pin "35") (pinfunction "AN11/PMA12/RB11_35") (pintype "bidirectional"))
      (node (ref "IC2") (pin "2") (pinfunction "A14_2") (pintype "input"))
    )
    (net (code "31") (name "A20") (class "Default")
      (node (ref "IC1") (pin "41") (pinfunction "AN12/PMA11/RB12_41") (pintype "bidirectional"))
      (node (ref "IC2") (pin "1") (pinfunction "A15_1") (pintype "input"))
    )
    (net (code "32") (name "AGND1") (class "Default")
      (node (ref "C3") (pin "1") (pinfunction "1_1") (pintype "passive"))
      (node (ref "C9") (pin "1") (pinfunction "1_1") (pintype "passive"))
      (node (ref "J1") (pin "2") (pinfunction "2_2") (pintype "passive"))
      (node (ref "R6") (pin "1") (pinfunction "1_1") (pintype "passive"))
    )
    (net (code "33") (name "AGND2") (class "Default")
      (node (ref "C10") (pin "1") (pinfunction "1_1") (pintype "passive"))
      (node (ref "C4") (pin "1") (pinfunction "1_1") (pintype "passive"))
      (node (ref "J2") (pin "2") (pinfunction "2_2") (pintype "passive"))
      (node (ref "R7") (pin "1") (pinfunction "1_1") (pintype "passive"))
    )
    (net (code "34") (name "AVDD1") (class "Default")
      (node (ref "C3") (pin "2") (pinfunction "2_2") (pintype "passive"))
      (node (ref "C9") (pin "2") (pinfunction "2_2") (pintype "passive"))
      (node (ref "J1") (pin "4") (pinfunction "4_4") (pintype "passive"))
      (node (ref "L1") (pin "2") (pinfunction "2_2") (pintype "passive"))
    )
    (net (code "35") (name "AVDD2") (class "Default")
      (node (ref "C10") (pin "2") (pinfunction "2_2") (pintype "passive"))
      (node (ref "C4") (pin "2") (pinfunction "2_2") (pintype "passive"))
      (node (ref "J2") (pin "4") (pinfunction "4_4") (pintype "passive"))
      (node (ref "L2") (pin "1") (pinfunction "1_1") (pintype "passive"))
    )
    (net (code "36") (name "B-") (class "Default")
      (node (ref "J3") (pin "5") (pinfunction "5_5") (pintype "passive"))
      (node (ref "J4") (pin "5") (pinfunction "5_5") (pintype "passive"))
      (node (ref "L7") (pin "2") (pinfunction "2_2") (pintype "passive"))
    )
    (net (code "37") (name "B--") (class "Default")
      (node (ref "IC12") (pin "7") (pinfunction "B_7") (pintype "bidirectional"))
      (node (ref "IC14") (pin "2") (pinfunction "2_2") (pintype "passive"))
      (node (ref "R108") (pin "2") (pinfunction "2_2") (pintype "passive"))
      (node (ref "R31") (pin "1") (pinfunction "1_1") (pintype "passive"))
      (node (ref "R32") (pin "1") (pinfunction "1_1") (pintype "passive"))
    )
    (net (code "38") (name "BT-RTS") (class "Default")
      (node (ref "IC1") (pin "83") (pinfunction "PMD14/RD6_83") (pintype "bidirectional"))
      (node (ref "J14") (pin "7") (pinfunction "7_7") (pintype "passive"))
      (node (ref "O32") (pin "P$1") (pinfunction "TP_P$1") (pintype "passive"))
      (node (ref "T44") (pin "P$1") (pinfunction "TP_P$1") (pintype "passive"))
    )
    (net (code "39") (name "BT-RX") (class "Default")
      (node (ref "IC1") (pin "73") (pinfunction "SOSCI/RPC13/RC13_73") (pintype "bidirectional"))
      (node (ref "J14") (pin "3") (pinfunction "3_3") (pintype "passive"))
      (node (ref "O37") (pin "P$1") (pinfunction "TP_P$1") (pintype "passive"))
      (node (ref "T40") (pin "P$1") (pinfunction "TP_P$1") (pintype "passive"))
    )
    (net (code "40") (name "BT-TX") (class "Default")
      (node (ref "IC1") (pin "74") (pinfunction "SOSCO/RPC14/T1CK/RC14_74") (pintype "bidirectional"))
      (node (ref "J14") (pin "4") (pinfunction "4_4") (pintype "passive"))
      (node (ref "O36") (pin "P$1") (pinfunction "TP_P$1") (pintype "passive"))
      (node (ref "T41") (pin "P$1") (pinfunction "TP_P$1") (pintype "passive"))
    )
    (net (code "41") (name "CON-LED") (class "Default")
      (node (ref "IC1") (pin "78") (pinfunction "AN26/RPD3/RD3_78") (pintype "bidirectional"))
      (node (ref "J14") (pin "6") (pinfunction "6_6") (pintype "passive"))
      (node (ref "O33") (pin "P$1") (pinfunction "TP_P$1") (pintype "passive"))
      (node (ref "T43") (pin "P$1") (pinfunction "TP_P$1") (pintype "passive"))
    )
    (net (code "42") (name "CS-SRAM") (class "Default")
      (node (ref "IC1") (pin "38") (pinfunction "TCK/CTED2/RA1_38") (pintype "bidirectional"))
      (node (ref "IC2") (pin "12") (pinfunction "CS2_12") (pintype "input"))
      (node (ref "O17") (pin "P$1") (pinfunction "TP_P$1") (pintype "passive"))
      (node (ref "R5") (pin "2") (pinfunction "2_2") (pintype "passive"))
      (node (ref "T28") (pin "P$1") (pinfunction "TP_P$1") (pintype "passive"))
    )
    (net (code "43") (name "CURR-SENSE") (class "Default")
      (node (ref "C66") (pin "1") (pinfunction "1_1") (pintype "passive"))
      (node (ref "IC1") (pin "14") (pinfunction "AN19/C2INC/RPG9/PMA2/RG9_14") (pintype "bidirectional"))
      (node (ref "O8") (pin "P$1") (pinfunction "TP_P$1") (pintype "passive"))
      (node (ref "R102") (pin "2") (pinfunction "2_2") (pintype "passive"))
      (node (ref "T39") (pin "P$1") (pinfunction "TP_P$1") (pintype "passive"))
    )
    (net (code "44") (name "D+") (class "Default")
      (node (ref "IC1") (pin "57") (pinfunction "D+/RG2_57") (pintype "bidirectional"))
      (node (ref "IC15") (pin "3") (pinfunction "3_3") (pintype "passive"))
      (node (ref "J12") (pin "2_D+") (pinfunction "D+_2_D+") (pintype "bidirectional"))
    )
    (net (code "45") (name "D-") (class "Default")
      (node (ref "IC1") (pin "56") (pinfunction "D-/RG3_56") (pintype "bidirectional"))
      (node (ref "IC15") (pin "2") (pinfunction "2_2") (pintype "passive"))
      (node (ref "J12") (pin "3_D-") (pinfunction "D-_3_D-") (pintype "bidirectional"))
    )
    (net (code "46") (name "D0") (class "Default")
      (node (ref "IC1") (pin "93") (pinfunction "PMD0/RE0_93") (pintype "bidirectional"))
      (node (ref "IC2") (pin "29") (pinfunction "D0_29") (pintype "tri_state"))
      (node (ref "IC3") (pin "9") (pinfunction "D7_9") (pintype "input"))
      (node (ref "IC4") (pin "2") (pinfunction "D0_2") (pintype "input"))
    )
    (net (code "47") (name "D1") (class "Default")
      (node (ref "IC1") (pin "94") (pinfunction "PMD1/RE1_94") (pintype "bidirectional"))
      (node (ref "IC2") (pin "31") (pinfunction "D1_31") (pintype "tri_state"))
      (node (ref "IC3") (pin "8") (pinfunction "D6_8") (pintype "input"))
      (node (ref "IC4") (pin "3") (pinfunction "D1_3") (pintype "input"))
    )
    (net (code "48") (name "D2") (class "Default")
      (node (ref "IC1") (pin "98") (pinfunction "AN20/PMD2/RE2_98") (pintype "bidirectional"))
      (node (ref "IC2") (pin "33") (pinfunction "D2_33") (pintype "tri_state"))
      (node (ref "IC3") (pin "7") (pinfunction "D5_7") (pintype "input"))
      (node (ref "IC4") (pin "4") (pinfunction "D2_4") (pintype "input"))
    )
    (net (code "49") (name "D3") (class "Default")
      (node (ref "IC1") (pin "99") (pinfunction "RPE3/PMD3/RE3_99") (pintype "bidirectional"))
      (node (ref "IC2") (pin "35") (pinfunction "D3_35") (pintype "tri_state"))
      (node (ref "IC3") (pin "6") (pinfunction "D4_6") (pintype "input"))
      (node (ref "IC4") (pin "5") (pinfunction "D3_5") (pintype "input"))
    )
    (net (code "50") (name "D4") (class "Default")
      (node (ref "IC1") (pin "100") (pinfunction "AN21/PMD4/RE4_100") (pintype "bidirectional"))
      (node (ref "IC2") (pin "38") (pinfunction "D4_38") (pintype "tri_state"))
      (node (ref "IC3") (pin "5") (pinfunction "D3_5") (pintype "input"))
      (node (ref "IC4") (pin "6") (pinfunction "D4_6") (pintype "input"))
    )
    (net (code "51") (name "D5") (class "Default")
      (node (ref "IC1") (pin "3") (pinfunction "AN22/RPE5/PMD5/RE5_3") (pintype "bidirectional"))
      (node (ref "IC2") (pin "40") (pinfunction "D5_40") (pintype "tri_state"))
      (node (ref "IC3") (pin "4") (pinfunction "D2_4") (pintype "input"))
      (node (ref "IC4") (pin "7") (pinfunction "D5_7") (pintype "input"))
    )
    (net (code "52") (name "D6") (class "Default")
      (node (ref "IC1") (pin "4") (pinfunction "AN23/PMD6/RE6_4") (pintype "bidirectional"))
      (node (ref "IC2") (pin "42") (pinfunction "D6_42") (pintype "tri_state"))
      (node (ref "IC3") (pin "3") (pinfunction "D1_3") (pintype "input"))
      (node (ref "IC4") (pin "8") (pinfunction "D6_8") (pintype "input"))
    )
    (net (code "53") (name "D7") (class "Default")
      (node (ref "IC1") (pin "5") (pinfunction "AN27/PMD7/RE7_5") (pintype "bidirectional"))
      (node (ref "IC2") (pin "44") (pinfunction "D7_44") (pintype "tri_state"))
      (node (ref "IC3") (pin "2") (pinfunction "D0_2") (pintype "input"))
      (node (ref "IC4") (pin "9") (pinfunction "D7_9") (pintype "input"))
    )
    (net (code "54") (name "DGND") (class "Default")
      (node (ref "C1") (pin "2") (pinfunction "2_2") (pintype "passive"))
      (node (ref "C11") (pin "2") (pinfunction "2_2") (pintype "passive"))
      (node (ref "C12") (pin "2") (pinfunction "2_2") (pintype "passive"))
      (node (ref "C13") (pin "1") (pinfunction "1_1") (pintype "passive"))
      (node (ref "C14") (pin "1") (pinfunction "1_1") (pintype "passive"))
      (node (ref "C15") (pin "2") (pinfunction "2_2") (pintype "passive"))
      (node (ref "C16") (pin "2") (pinfunction "2_2") (pintype "passive"))
      (node (ref "C17") (pin "2") (pinfunction "2_2") (pintype "passive"))
      (node (ref "C18") (pin "2") (pinfunction "2_2") (pintype "passive"))
      (node (ref "C19") (pin "2") (pinfunction "2_2") (pintype "passive"))
      (node (ref "C2") (pin "2") (pinfunction "2_2") (pintype "passive"))
      (node (ref "C20") (pin "2") (pinfunction "2_2") (pintype "passive"))
      (node (ref "C22") (pin "2") (pinfunction "2_2") (pintype "passive"))
      (node (ref "C23") (pin "2") (pinfunction "2_2") (pintype "passive"))
      (node (ref "C24") (pin "1") (pinfunction "1_1") (pintype "passive"))
      (node (ref "C27") (pin "2") (pinfunction "2_2") (pintype "passive"))
      (node (ref "C28") (pin "2") (pinfunction "2_2") (pintype "passive"))
      (node (ref "C29") (pin "2") (pinfunction "2_2") (pintype "passive"))
      (node (ref "C30") (pin "2") (pinfunction "2_2") (pintype "passive"))
      (node (ref "C31") (pin "-") (pinfunction "-_-") (pintype "passive"))
      (node (ref "C32") (pin "2") (pinfunction "2_2") (pintype "passive"))
      (node (ref "C35") (pin "2") (pinfunction "2_2") (pintype "passive"))
      (node (ref "C36") (pin "2") (pinfunction "2_2") (pintype "passive"))
      (node (ref "C37") (pin "2") (pinfunction "2_2") (pintype "passive"))
      (node (ref "C38") (pin "2") (pinfunction "2_2") (pintype "passive"))
      (node (ref "C39") (pin "2") (pinfunction "2_2") (pintype "passive"))
      (node (ref "C40") (pin "2") (pinfunction "2_2") (pintype "passive"))
      (node (ref "C41") (pin "2") (pinfunction "2_2") (pintype "passive"))
      (node (ref "C46") (pin "2") (pinfunction "2_2") (pintype "passive"))
      (node (ref "C47") (pin "2") (pinfunction "2_2") (pintype "passive"))
      (node (ref "C48") (pin "2") (pinfunction "2_2") (pintype "passive"))
      (node (ref "C49") (pin "2") (pinfunction "2_2") (pintype "passive"))
      (node (ref "C5") (pin "2") (pinfunction "2_2") (pintype "passive"))
      (node (ref "C50") (pin "2") (pinfunction "2_2") (pintype "passive"))
      (node (ref "C51") (pin "2") (pinfunction "2_2") (pintype "passive"))
      (node (ref "C52") (pin "2") (pinfunction "2_2") (pintype "passive"))
      (node (ref "C53") (pin "2") (pinfunction "2_2") (pintype "passive"))
      (node (ref "C54") (pin "2") (pinfunction "2_2") (pintype "passive"))
      (node (ref "C55") (pin "2") (pinfunction "2_2") (pintype "passive"))
      (node (ref "C56") (pin "2") (pinfunction "2_2") (pintype "passive"))
      (node (ref "C57") (pin "2") (pinfunction "2_2") (pintype "passive"))
      (node (ref "C58") (pin "2") (pinfunction "2_2") (pintype "passive"))
      (node (ref "C59") (pin "2") (pinfunction "2_2") (pintype "passive"))
      (node (ref "C6") (pin "2") (pinfunction "2_2") (pintype "passive"))
      (node (ref "C60") (pin "2") (pinfunction "2_2") (pintype "passive"))
      (node (ref "C61") (pin "2") (pinfunction "2_2") (pintype "passive"))
      (node (ref "C62") (pin "2") (pinfunction "2_2") (pintype "passive"))
      (node (ref "C63") (pin "2") (pinfunction "2_2") (pintype "passive"))
      (node (ref "C64") (pin "2") (pinfunction "2_2") (pintype "passive"))
      (node (ref "C65") (pin "2") (pinfunction "2_2") (pintype "passive"))
      (node (ref "C66") (pin "2") (pinfunction "2_2") (pintype "passive"))
      (node (ref "C67") (pin "2") (pinfunction "2_2") (pintype "passive"))
      (node (ref "C7") (pin "1") (pinfunction "1_1") (pintype "passive"))
      (node (ref "C75") (pin "2") (pinfunction "2_2") (pintype "passive"))
      (node (ref "C76") (pin "2") (pinfunction "2_2") (pintype "passive"))
      (node (ref "C77") (pin "2") (pinfunction "2_2") (pintype "passive"))
      (node (ref "C78") (pin "2") (pinfunction "2_2") (pintype "passive"))
      (node (ref "C79") (pin "2") (pinfunction "2_2") (pintype "passive"))
      (node (ref "C8") (pin "1") (pinfunction "1_1") (pintype "passive"))
      (node (ref "C80") (pin "2") (pinfunction "2_2") (pintype "passive"))
      (node (ref "C81") (pin "-") (pinfunction "-_-") (pintype "passive"))
      (node (ref "C82") (pin "2") (pinfunction "2_2") (pintype "passive"))
      (node (ref "C83") (pin "2") (pinfunction "2_2") (pintype "passive"))
      (node (ref "C84") (pin "2") (pinfunction "2_2") (pintype "passive"))
      (node (ref "C85") (pin "2") (pinfunction "2_2") (pintype "passive"))
      (node (ref "C86") (pin "2") (pinfunction "2_2") (pintype "passive"))
      (node (ref "C87") (pin "2") (pinfunction "2_2") (pintype "passive"))
      (node (ref "C88") (pin "2") (pinfunction "2_2") (pintype "passive"))
      (node (ref "D2") (pin "-") (pinfunction "A_-") (pintype "passive"))
      (node (ref "D5") (pin "1+") (pinfunction "K_1+") (pintype "passive"))
      (node (ref "D7") (pin "A") (pinfunction "A_A") (pintype "passive"))
      (node (ref "IC1") (pin "15") (pinfunction "VSS2_15") (pintype "input"))
      (node (ref "IC1") (pin "31") (pinfunction "AVSS_31") (pintype "input"))
      (node (ref "IC1") (pin "36") (pinfunction "VSS3_36") (pintype "input"))
      (node (ref "IC1") (pin "45") (pinfunction "VSS4_45") (pintype "input"))
      (node (ref "IC1") (pin "65") (pinfunction "VSS5_65") (pintype "input"))
      (node (ref "IC1") (pin "75") (pinfunction "VSS1_75") (pintype "input"))
      (node (ref "IC10") (pin "1") (pinfunction "GND_1") (pintype "input"))
      (node (ref "IC10") (pin "2") (pinfunction "GND1_2") (pintype "input"))
      (node (ref "IC11") (pin "1") (pinfunction "A0_1") (pintype "input"))
      (node (ref "IC11") (pin "3") (pinfunction "A2_3") (pintype "input"))
      (node (ref "IC11") (pin "4") (pinfunction "GND_4") (pintype "input"))
      (node (ref "IC12") (pin "5") (pinfunction "GND_5") (pintype "input"))
      (node (ref "IC13") (pin "3") (pinfunction "GND_3") (pintype "bidirectional"))
      (node (ref "IC14") (pin "1") (pinfunction "1_1") (pintype "input"))
      (node (ref "IC15") (pin "1") (pinfunction "1_1") (pintype "input"))
      (node (ref "IC16") (pin "4") (pinfunction "V-_4") (pintype "input"))
      (node (ref "IC2") (pin "14") (pinfunction "~{UB}_14") (pintype "input"))
      (node (ref "IC2") (pin "15") (pinfunction "~{LB}_15") (pintype "input"))
      (node (ref "IC2") (pin "26") (pinfunction "~{CS1}_26") (pintype "input"))
      (node (ref "IC2") (pin "27") (pinfunction "GND1_27") (pintype "bidirectional"))
      (node (ref "IC2") (pin "46") (pinfunction "GND2_46") (pintype "bidirectional"))
      (node (ref "IC2") (pin "47") (pinfunction "~{BYTE}_47") (pintype "input"))
      (node (ref "IC3") (pin "1") (pinfunction "~{OE}_1") (pintype "input"))
      (node (ref "IC3") (pin "10") (pinfunction "GND_10") (pintype "bidirectional"))
      (node (ref "IC4") (pin "1") (pinfunction "~{OE}_1") (pintype "input"))
      (node (ref "IC4") (pin "10") (pinfunction "GND_10") (pintype "bidirectional"))
      (node (ref "IC5") (pin "2") (pinfunction "GND_2") (pintype "input"))
      (node (ref "IC6") (pin "2") (pinfunction "GND_2") (pintype "input"))
      (node (ref "IC7") (pin "1") (pinfunction "A0_1") (pintype "input"))
      (node (ref "IC7") (pin "2") (pinfunction "A1_2") (pintype "input"))
      (node (ref "IC7") (pin "3") (pinfunction "A2_3") (pintype "input"))
      (node (ref "IC7") (pin "4") (pinfunction "GND_4") (pintype "input"))
      (node (ref "IC7") (pin "7") (pinfunction "WP_7") (pintype "input"))
      (node (ref "IC8") (pin "10") (pinfunction "SYNC_10") (pintype "bidirectional"))
      (node (ref "IC8") (pin "EP") (pinfunction "GND_EP") (pintype "bidirectional"))
      (node (ref "IC9") (pin "4") (pinfunction "GND_4") (pintype "input"))
      (node (ref "J1") (pin "15") (pinfunction "15_15") (pintype "passive"))
      (node (ref "J11") (pin "6") (pinfunction "VSS_6") (pintype "passive"))
      (node (ref "J11") (pin "G1") (pinfunction "G1_G1") (pintype "passive"))
      (node (ref "J11") (pin "G3") (pinfunction "G3_G3") (pintype "passive"))
      (node (ref "J11") (pin "G4") (pinfunction "G4_G4") (pintype "passive"))
      (node (ref "J11") (pin "G5") (pinfunction "G5_G5") (pintype "passive"))
      (node (ref "J11") (pin "G6") (pinfunction "G6_G6") (pintype "passive"))
      (node (ref "J12") (pin "4_GND") (pinfunction "GND_4_GND") (pintype "bidirectional"))
      (node (ref "J12") (pin "SH1") (pinfunction "KONS_GND_1_SH1") (pintype "bidirectional"))
      (node (ref "J12") (pin "SH2") (pinfunction "KONS_GND_2_SH2") (pintype "bidirectional"))
      (node (ref "J14") (pin "1") (pinfunction "1_1") (pintype "passive"))
      (node (ref "J15") (pin "9") (pinfunction "9_9") (pintype "passive"))
      (node (ref "J17") (pin "3") (pinfunction "3_3") (pintype "passive"))
      (node (ref "J2") (pin "15") (pinfunction "15_15") (pintype "passive"))
      (node (ref "J5") (pin "1") (pinfunction "1_1") (pintype "bidirectional"))
      (node (ref "J6") (pin "1") (pinfunction "1_1") (pintype "bidirectional"))
      (node (ref "L12") (pin "1") (pinfunction "1_1") (pintype "passive"))
      (node (ref "PCB2") (pin "VPS_PCB_1") (pinfunction "VPS_PCB_1_VPS_PCB_1") (pintype "bidirectional"))
      (node (ref "PCB3") (pin "1") (pinfunction "P$1_1") (pintype "bidirectional"))
      (node (ref "Q10") (pin "4") (pinfunction "S_4") (pintype "passive"))
      (node (ref "Q11") (pin "4") (pinfunction "S_4") (pintype "passive"))
      (node (ref "Q12") (pin "4") (pinfunction "S_4") (pintype "passive"))
      (node (ref "Q13") (pin "4") (pinfunction "S_4") (pintype "passive"))
      (node (ref "Q14") (pin "1") (pinfunction "S_1") (pintype "passive"))
      (node (ref "Q3") (pin "1") (pinfunction "S_1") (pintype "passive"))
      (node (ref "R1") (pin "1") (pinfunction "1_1") (pintype "passive"))
      (node (ref "R112") (pin "2") (pinfunction "2_2") (pintype "passive"))
      (node (ref "R118") (pin "2") (pinfunction "2_2") (pintype "passive"))
      (node (ref "R127") (pin "1") (pinfunction "1_1") (pintype "passive"))
      (node (ref "R17") (pin "2") (pinfunction "2_2") (pintype "passive"))
      (node (ref "R19") (pin "2") (pinfunction "2_2") (pintype "passive"))
      (node (ref "R2") (pin "1") (pinfunction "1_1") (pintype "passive"))
      (node (ref "R21") (pin "2") (pinfunction "2_2") (pintype "passive"))
      (node (ref "R31") (pin "2") (pinfunction "2_2") (pintype "passive"))
      (node (ref "R40") (pin "1") (pinfunction "1_1") (pintype "passive"))
      (node (ref "R41") (pin "2") (pinfunction "2_2") (pintype "passive"))
      (node (ref "R43") (pin "1") (pinfunction "1_1") (pintype "passive"))
      (node (ref "R44") (pin "2") (pinfunction "2_2") (pintype "passive"))
      (node (ref "R46") (pin "1") (pinfunction "1_1") (pintype "passive"))
      (node (ref "R48") (pin "1") (pinfunction "1_1") (pintype "passive"))
      (node (ref "R5") (pin "1") (pinfunction "1_1") (pintype "passive"))
      (node (ref "R51") (pin "1") (pinfunction "1_1") (pintype "passive"))
      (node (ref "R52") (pin "2") (pinfunction "2_2") (pintype "passive"))
      (node (ref "R53") (pin "2") (pinfunction "2_2") (pintype "passive"))
      (node (ref "R54") (pin "2") (pinfunction "2_2") (pintype "passive"))
      (node (ref "R57") (pin "1") (pinfunction "1_1") (pintype "passive"))
      (node (ref "R58") (pin "2") (pinfunction "2_2") (pintype "passive"))
      (node (ref "R59") (pin "2") (pinfunction "2_2") (pintype "passive"))
      (node (ref "R6") (pin "2") (pinfunction "2_2") (pintype "passive"))
      (node (ref "R60") (pin "2") (pinfunction "2_2") (pintype "passive"))
      (node (ref "R64") (pin "2") (pinfunction "2_2") (pintype "passive"))
      (node (ref "R67") (pin "2") (pinfunction "2_2") (pintype "passive"))
      (node (ref "R7") (pin "2") (pinfunction "2_2") (pintype "passive"))
      (node (ref "R70") (pin "2") (pinfunction "2_2") (pintype "passive"))
      (node (ref "R71") (pin "2") (pinfunction "2_2") (pintype "passive"))
      (node (ref "R76") (pin "2") (pinfunction "2_2") (pintype "passive"))
      (node (ref "R80") (pin "2") (pinfunction "2_2") (pintype "passive"))
      (node (ref "R83") (pin "2") (pinfunction "2_2") (pintype "passive"))
      (node (ref "R86") (pin "2") (pinfunction "2_2") (pintype "passive"))
      (node (ref "R88") (pin "2") (pinfunction "2_2") (pintype "passive"))
      (node (ref "R96") (pin "2") (pinfunction "2_2") (pintype "passive"))
      (node (ref "R99") (pin "2") (pinfunction "2_2") (pintype "passive"))
    )
    (net (code "55") (name "DOOR-IN-EN") (class "Default")
      (node (ref "IC1") (pin "51") (pinfunction "RPF3/USBID/RF3_51") (pintype "bidirectional"))
      (node (ref "O43") (pin "P$1") (pinfunction "TP_P$1") (pintype "passive"))
      (node (ref "Q12") (pin "2") (pinfunction "G_2") (pintype "passive"))
      (node (ref "Q13") (pin "2") (pinfunction "G_2") (pintype "passive"))
      (node (ref "R76") (pin "1") (pinfunction "1_1") (pintype "passive"))
      (node (ref "R88") (pin "1") (pinfunction "1_1") (pintype "passive"))
      (node (ref "T8") (pin "P$1") (pinfunction "TP_P$1") (pintype "passive"))
    )
    (net (code "56") (name "DOOR1IN") (class "Default")
      (node (ref "IC1") (pin "50") (pinfunction "RPF5/PMA8/RF5_50") (pintype "bidirectional"))
      (node (ref "O21") (pin "P$1") (pinfunction "TP_P$1") (pintype "passive"))
      (node (ref "Q13") (pin "3") (pinfunction "D_3") (pintype "passive"))
      (node (ref "R74") (pin "1") (pinfunction "1_1") (pintype "passive"))
      (node (ref "T12") (pin "P$1") (pinfunction "TP_P$1") (pintype "passive"))
    )
    (net (code "57") (name "DOOR2IN") (class "Default")
      (node (ref "IC1") (pin "77") (pinfunction "AN25/RPD2/RD2_77") (pintype "bidirectional"))
      (node (ref "O34") (pin "P$1") (pinfunction "TP_P$1") (pintype "passive"))
      (node (ref "Q12") (pin "3") (pinfunction "D_3") (pintype "passive"))
      (node (ref "R89") (pin "1") (pinfunction "1_1") (pintype "passive"))
      (node (ref "T11") (pin "P$1") (pinfunction "TP_P$1") (pintype "passive"))
    )
    (net (code "58") (name "DOVDD1") (class "Default")
      (node (ref "C11") (pin "1") (pinfunction "1_1") (pintype "passive"))
      (node (ref "C5") (pin "1") (pinfunction "1_1") (pintype "passive"))
      (node (ref "J1") (pin "11") (pinfunction "11_11") (pintype "passive"))
      (node (ref "L3") (pin "2") (pinfunction "2_2") (pintype "passive"))
    )
    (net (code "59") (name "DOVDD2") (class "Default")
      (node (ref "C12") (pin "1") (pinfunction "1_1") (pintype "passive"))
      (node (ref "C6") (pin "1") (pinfunction "1_1") (pintype "passive"))
      (node (ref "J2") (pin "11") (pinfunction "11_11") (pintype "passive"))
      (node (ref "L4") (pin "1") (pinfunction "1_1") (pintype "passive"))
    )
    (net (code "60") (name "DVDD1") (class "Default")
      (node (ref "C13") (pin "2") (pinfunction "2_2") (pintype "passive"))
      (node (ref "C7") (pin "2") (pinfunction "2_2") (pintype "passive"))
      (node (ref "J1") (pin "10") (pinfunction "10_10") (pintype "passive"))
      (node (ref "L5") (pin "2") (pinfunction "2_2") (pintype "passive"))
    )
    (net (code "61") (name "DVDD2") (class "Default")
      (node (ref "C14") (pin "2") (pinfunction "2_2") (pintype "passive"))
      (node (ref "C8") (pin "2") (pinfunction "2_2") (pintype "passive"))
      (node (ref "J2") (pin "10") (pinfunction "10_10") (pintype "passive"))
      (node (ref "L6") (pin "1") (pinfunction "1_1") (pintype "passive"))
    )
    (net (code "62") (name "EN") (class "Default")
      (node (ref "IC1") (pin "18") (pinfunction "RPE8/RE8_18") (pintype "bidirectional"))
      (node (ref "J15") (pin "8") (pinfunction "8_8") (pintype "passive"))
      (node (ref "O10") (pin "P$1") (pinfunction "TP_P$1") (pintype "passive"))
      (node (ref "T25") (pin "P$1") (pinfunction "TP_P$1") (pintype "passive"))
    )
    (net (code "63") (name "HREF") (class "Default")
      (node (ref "IC1") (pin "6") (pinfunction "RPC1/RC1_6") (pintype "bidirectional"))
      (node (ref "J1") (pin "9") (pinfunction "9_9") (pintype "passive"))
      (node (ref "J2") (pin "9") (pinfunction "9_9") (pintype "passive"))
      (node (ref "O2") (pin "P$1") (pinfunction "TP_P$1") (pintype "passive"))
      (node (ref "T18") (pin "P$1") (pinfunction "TP_P$1") (pintype "passive"))
    )
    (net (code "64") (name "INFRA1PWM") (class "Default")
      (node (ref "IC1") (pin "90") (pinfunction "RPG0/PMD8/RG0_90") (pintype "bidirectional"))
      (node (ref "O27") (pin "P$1") (pinfunction "TP_P$1") (pintype "passive"))
      (node (ref "R113") (pin "2") (pinfunction "2_2") (pintype "passive"))
      (node (ref "T34") (pin "P$1") (pinfunction "TP_P$1") (pintype "passive"))
    )
    (net (code "65") (name "INFRA2PWM") (class "Default")
      (node (ref "IC1") (pin "40") (pinfunction "RPF12/RF12_40") (pintype "bidirectional"))
      (node (ref "O19") (pin "P$1") (pinfunction "TP_P$1") (pintype "passive"))
      (node (ref "R119") (pin "2") (pinfunction "2_2") (pintype "passive"))
      (node (ref "T35") (pin "P$1") (pinfunction "TP_P$1") (pintype "passive"))
    )
    (net (code "66") (name "IRQ") (class "Default")
      (node (ref "IC1") (pin "19") (pinfunction "RPE9/RE9_19") (pintype "bidirectional"))
      (node (ref "J15") (pin "3") (pinfunction "3_3") (pintype "passive"))
      (node (ref "O11") (pin "P$1") (pinfunction "TP_P$1") (pintype "passive"))
      (node (ref "T24") (pin "P$1") (pinfunction "TP_P$1") (pintype "passive"))
    )
    (net (code "67") (name "L1CTL") (class "Default")
      (node (ref "C79") (pin "1") (pinfunction "1_1") (pintype "passive"))
      (node (ref "J5") (pin "3") (pinfunction "3_3") (pintype "bidirectional"))
      (node (ref "Q6") (pin "4") (pinfunction "D_4") (pintype "bidirectional"))
    )
    (net (code "68") (name "L1PWR") (class "Default")
      (node (ref "C80") (pin "1") (pinfunction "1_1") (pintype "passive"))
      (node (ref "J5") (pin "2") (pinfunction "2_2") (pintype "bidirectional"))
      (node (ref "Q6") (pin "6") (pinfunction "D_6") (pintype "bidirectional"))
    )
    (net (code "69") (name "L2CTL") (class "Default")
      (node (ref "C78") (pin "1") (pinfunction "1_1") (pintype "passive"))
      (node (ref "J6") (pin "3") (pinfunction "3_3") (pintype "bidirectional"))
      (node (ref "Q8") (pin "6") (pinfunction "D_6") (pintype "bidirectional"))
    )
    (net (code "70") (name "L2PWR") (class "Default")
      (node (ref "C77") (pin "1") (pinfunction "1_1") (pintype "passive"))
      (node (ref "J6") (pin "2") (pinfunction "2_2") (pintype "bidirectional"))
      (node (ref "Q8") (pin "4") (pinfunction "D_4") (pintype "bidirectional"))
    )
    (net (code "71") (name "LAN-CTL") (class "Default")
      (node (ref "IC1") (pin "84") (pinfunction "PMD15/RD7_84") (pintype "bidirectional"))
      (node (ref "IC12") (pin "2") (pinfunction "/RE_2") (pintype "input"))
      (node (ref "IC12") (pin "3") (pinfunction "DE_3") (pintype "input"))
      (node (ref "O31") (pin "P$1") (pinfunction "TP_P$1") (pintype "passive"))
      (node (ref "R71") (pin "1") (pinfunction "1_1") (pintype "passive"))
      (node (ref "T15") (pin "P$1") (pinfunction "TP_P$1") (pintype "passive"))
    )
    (net (code "72") (name "LAN-RX") (class "Default")
      (node (ref "IC1") (pin "88") (pinfunction "RPF1/PMD10/RF1_88") (pintype "bidirectional"))
      (node (ref "IC12") (pin "1") (pinfunction "R_1") (pintype "output"))
      (node (ref "O29") (pin "P$1") (pinfunction "TP_P$1") (pintype "passive"))
      (node (ref "R72") (pin "2") (pinfunction "2_2") (pintype "passive"))
      (node (ref "T13") (pin "P$1") (pinfunction "TP_P$1") (pintype "passive"))
    )
    (net (code "73") (name "LAN-TX") (class "Default")
      (node (ref "IC1") (pin "87") (pinfunction "RPF0/PMD11/RF0_87") (pintype "bidirectional"))
      (node (ref "IC12") (pin "4") (pinfunction "D_4") (pintype "input"))
      (node (ref "O30") (pin "P$1") (pinfunction "TP_P$1") (pintype "passive"))
      (node (ref "R73") (pin "1") (pinfunction "1_1") (pintype "passive"))
      (node (ref "T14") (pin "P$1") (pinfunction "TP_P$1") (pintype "passive"))
    )
    (net (code "74") (name "LED-PIC") (class "Default")
      (node (ref "IC1") (pin "1") (pinfunction "RG15_1") (pintype "bidirectional"))
      (node (ref "O1") (pin "P$1") (pinfunction "TP_P$1") (pintype "passive"))
      (node (ref "R29") (pin "1") (pinfunction "1_1") (pintype "passive"))
      (node (ref "T36") (pin "P$1") (pinfunction "TP_P$1") (pintype "passive"))
      (node (ref "TP4") (pin "P$1") (pinfunction "TP_P$1") (pintype "passive"))
    )
    (net (code "75") (name "LEH-SRAM") (class "Default")
      (node (ref "IC1") (pin "43") (pinfunction "AN14/RPB14/PMA1/CTED5/RB14_43") (pintype "bidirectional"))
      (node (ref "IC4") (pin "11") (pinfunction "LE_11") (pintype "input"))
      (node (ref "R2") (pin "2") (pinfunction "2_2") (pintype "passive"))
    )
    (net (code "76") (name "LEL-SRAM") (class "Default")
      (node (ref "IC1") (pin "44") (pinfunction "AN15/RPB15/PMA0/CTED6//RB15_44") (pintype "bidirectional"))
      (node (ref "IC3") (pin "11") (pinfunction "LE_11") (pintype "input"))
      (node (ref "R1") (pin "2") (pinfunction "2_2") (pintype "passive"))
    )
    (net (code "77") (name "LOCK-IN-EN") (class "Default")
      (node (ref "IC1") (pin "60") (pinfunction "TDI/CTED9/RA4_60") (pintype "bidirectional"))
      (node (ref "O40") (pin "P$1") (pinfunction "TP_P$1") (pintype "passive"))
      (node (ref "Q10") (pin "2") (pinfunction "G_2") (pintype "passive"))
      (node (ref "Q11") (pin "2") (pinfunction "G_2") (pintype "passive"))
      (node (ref "R67") (pin "1") (pinfunction "1_1") (pintype "passive"))
      (node (ref "R83") (pin "1") (pinfunction "1_1") (pintype "passive"))
      (node (ref "T6") (pin "P$1") (pinfunction "TP_P$1") (pintype "passive"))
    )
    (net (code "78") (name "LOCK1CTL") (class "Default")
      (node (ref "IC1") (pin "61") (pinfunction "TDO/RA5_61") (pintype "bidirectional"))
      (node (ref "O39") (pin "P$1") (pinfunction "TP_P$1") (pintype "passive"))
      (node (ref "Q7") (pin "5") (pinfunction "G_5") (pintype "passive"))
      (node (ref "R54") (pin "1") (pinfunction "1_1") (pintype "passive"))
      (node (ref "T1") (pin "P$1") (pinfunction "TP_P$1") (pintype "passive"))
    )
    (net (code "79") (name "LOCK1IN") (class "Default")
      (node (ref "IC1") (pin "49") (pinfunction "RPF4/PMA9/RF4_49") (pintype "bidirectional"))
      (node (ref "O20") (pin "P$1") (pinfunction "TP_P$1") (pintype "passive"))
      (node (ref "Q11") (pin "3") (pinfunction "D_3") (pintype "passive"))
      (node (ref "R66") (pin "1") (pinfunction "1_1") (pintype "passive"))
      (node (ref "T10") (pin "P$1") (pinfunction "TP_P$1") (pintype "passive"))
    )
    (net (code "80") (name "LOCK2CTL") (class "Default")
      (node (ref "IC1") (pin "91") (pinfunction "TRCLK/RA6_91") (pintype "bidirectional"))
      (node (ref "O26") (pin "P$1") (pinfunction "TP_P$1") (pintype "passive"))
      (node (ref "Q9") (pin "2") (pinfunction "G_2") (pintype "passive"))
      (node (ref "R58") (pin "1") (pinfunction "1_1") (pintype "passive"))
      (node (ref "T2") (pin "P$1") (pinfunction "TP_P$1") (pintype "passive"))
    )
    (net (code "81") (name "LOCK2IN") (class "Default")
      (node (ref "IC1") (pin "89") (pinfunction "RPG1/PMD9/RG1_89") (pintype "bidirectional"))
      (node (ref "O28") (pin "P$1") (pinfunction "TP_P$1") (pintype "passive"))
      (node (ref "Q10") (pin "3") (pinfunction "D_3") (pintype "passive"))
      (node (ref "R81") (pin "1") (pinfunction "1_1") (pintype "passive"))
      (node (ref "T9") (pin "P$1") (pinfunction "TP_P$1") (pintype "passive"))
    )
    (net (code "82") (name "LOCK12PWR") (class "Default")
      (node (ref "IC1") (pin "92") (pinfunction "TRD3/CTED8/RA7_92") (pintype "bidirectional"))
      (node (ref "O25") (pin "P$1") (pinfunction "TP_P$1") (pintype "passive"))
      (node (ref "Q7") (pin "2") (pinfunction "G_2") (pintype "passive"))
      (node (ref "Q9") (pin "5") (pinfunction "G_5") (pintype "passive"))
      (node (ref "R52") (pin "1") (pinfunction "1_1") (pintype "passive"))
      (node (ref "R60") (pin "1") (pinfunction "1_1") (pintype "passive"))
      (node (ref "T4") (pin "P$1") (pinfunction "TP_P$1") (pintype "passive"))
    )
    (net (code "83") (name "Net-(C24-Pad2)") (class "Default")
      (node (ref "C24") (pin "2") (pinfunction "2_2") (pintype "passive"))
      (node (ref "R77") (pin "2") (pinfunction "2_2") (pintype "passive"))
    )
    (net (code "84") (name "Net-(C32-Pad1)") (class "Default")
      (node (ref "C32") (pin "1") (pinfunction "1_1") (pintype "passive"))
      (node (ref "R68") (pin "2") (pinfunction "2_2") (pintype "passive"))
      (node (ref "R69") (pin "1") (pinfunction "1_1") (pintype "passive"))
    )
    (net (code "85") (name "Net-(C37-Pad1)") (class "Default")
      (node (ref "C37") (pin "1") (pinfunction "1_1") (pintype "passive"))
      (node (ref "R78") (pin "2") (pinfunction "2_2") (pintype "passive"))
      (node (ref "R79") (pin "1") (pinfunction "1_1") (pintype "passive"))
    )
    (net (code "86") (name "Net-(C38-Pad1)") (class "Default")
      (node (ref "C38") (pin "1") (pinfunction "1_1") (pintype "passive"))
      (node (ref "R84") (pin "2") (pinfunction "2_2") (pintype "passive"))
      (node (ref "R85") (pin "1") (pinfunction "1_1") (pintype "passive"))
    )
    (net (code "87") (name "Net-(C39-Pad1)") (class "Default")
      (node (ref "C39") (pin "1") (pinfunction "1_1") (pintype "passive"))
      (node (ref "IC14") (pin "4") (pinfunction "4_4") (pintype "input"))
      (node (ref "R30") (pin "1") (pinfunction "1_1") (pintype "passive"))
    )
    (net (code "88") (name "Net-(C40-Pad1)") (class "Default")
      (node (ref "C40") (pin "1") (pinfunction "1_1") (pintype "passive"))
      (node (ref "R90") (pin "1") (pinfunction "1_1") (pintype "passive"))
      (node (ref "R91") (pin "1") (pinfunction "1_1") (pintype "passive"))
    )
    (net (code "89") (name "Net-(C46-Pad1)") (class "Default")
      (node (ref "C46") (pin "1") (pinfunction "1_1") (pintype "passive"))
      (node (ref "R62") (pin "2") (pinfunction "2_2") (pintype "passive"))
      (node (ref "R63") (pin "1") (pinfunction "1_1") (pintype "passive"))
    )
    (net (code "90") (name "Net-(C71-Pad+)") (class "Default")
      (node (ref "C71") (pin "+") (pinfunction "+_+") (pintype "passive"))
      (node (ref "C72") (pin "1") (pinfunction "1_1") (pintype "passive"))
      (node (ref "J9") (pin "1") (pinfunction "1_1") (pintype "passive"))
      (node (ref "R124") (pin "2") (pinfunction "2_2") (pintype "passive"))
    )
    (net (code "91") (name "Net-(C71-Pad-)") (class "Default")
      (node (ref "C71") (pin "-") (pinfunction "-_-") (pintype "passive"))
      (node (ref "C72") (pin "2") (pinfunction "2_2") (pintype "passive"))
      (node (ref "R110") (pin "2") (pinfunction "2_2") (pintype "passive"))
      (node (ref "R111") (pin "1") (pinfunction "1_1") (pintype "passive"))
      (node (ref "R114") (pin "2") (pinfunction "2_2") (pintype "passive"))
      (node (ref "R115") (pin "1") (pinfunction "1_1") (pintype "passive"))
    )
    (net (code "92") (name "Net-(C73-Pad+)") (class "Default")
      (node (ref "C73") (pin "+") (pinfunction "+_+") (pintype "passive"))
      (node (ref "C74") (pin "1") (pinfunction "1_1") (pintype "passive"))
      (node (ref "J10") (pin "1") (pinfunction "1_1") (pintype "passive"))
      (node (ref "R125") (pin "2") (pinfunction "2_2") (pintype "passive"))
    )
    (net (code "93") (name "Net-(C73-Pad-)") (class "Default")
      (node (ref "C73") (pin "-") (pinfunction "-_-") (pintype "passive"))
      (node (ref "C74") (pin "2") (pinfunction "2_2") (pintype "passive"))
      (node (ref "R116") (pin "2") (pinfunction "2_2") (pintype "passive"))
      (node (ref "R117") (pin "1") (pinfunction "1_1") (pintype "passive"))
      (node (ref "R122") (pin "2") (pinfunction "2_2") (pintype "passive"))
      (node (ref "R123") (pin "1") (pinfunction "1_1") (pintype "passive"))
    )
    (net (code "94") (name "Net-(D2-C)") (class "Default")
      (node (ref "C26") (pin "1") (pinfunction "1_1") (pintype "passive"))
      (node (ref "C30") (pin "1") (pinfunction "1_1") (pintype "passive"))
      (node (ref "C31") (pin "+") (pinfunction "+_+") (pintype "passive"))
      (node (ref "D2") (pin "+") (pinfunction "C_+") (pintype "passive"))
      (node (ref "IC8") (pin "1") (pinfunction "BD_1") (pintype "bidirectional"))
      (node (ref "L9") (pin "2") (pinfunction "2_2") (pintype "passive"))
      (node (ref "R129") (pin "2") (pinfunction "2_2") (pintype "passive"))
      (node (ref "R20") (pin "1") (pinfunction "1_1") (pintype "passive"))
    )
    (net (code "95") (name "Net-(D3-PadA)") (class "Default")
      (node (ref "D3") (pin "A") (pinfunction "A_A") (pintype "passive"))
      (node (ref "D4") (pin "A") (pinfunction "A_A") (pintype "passive"))
      (node (ref "J3") (pin "2") (pinfunction "2_2") (pintype "passive"))
      (node (ref "J3") (pin "7") (pinfunction "7_7") (pintype "passive"))
      (node (ref "J3") (pin "8") (pinfunction "8_8") (pintype "passive"))
      (node (ref "J4") (pin "2") (pinfunction "2_2") (pintype "passive"))
      (node (ref "J4") (pin "7") (pinfunction "7_7") (pintype "passive"))
      (node (ref "J4") (pin "8") (pinfunction "8_8") (pintype "passive"))
      (node (ref "L12") (pin "2") (pinfunction "2_2") (pintype "passive"))
    )
    (net (code "96") (name "Net-(D5-A)") (class "Default")
      (node (ref "D5") (pin "2") (pinfunction "A_2") (pintype "passive"))
      (node (ref "R29") (pin "2") (pinfunction "2_2") (pintype "passive"))
    )
    (net (code "97") (name "Net-(IC1-AVDD)") (class "Default")
      (node (ref "C55") (pin "1") (pinfunction "1_1") (pintype "passive"))
      (node (ref "C56") (pin "1") (pinfunction "1_1") (pintype "passive"))
      (node (ref "C88") (pin "1") (pinfunction "1_1") (pintype "passive"))
      (node (ref "IC1") (pin "30") (pinfunction "AVDD_30") (pintype "input"))
      (node (ref "R92") (pin "2") (pinfunction "2_2") (pintype "passive"))
    )
    (net (code "98") (name "Net-(IC1-CLKI{slash}RC12{slash}OSC1)") (class "Default")
      (node (ref "C60") (pin "1") (pinfunction "1_1") (pintype "passive"))
      (node (ref "IC1") (pin "63") (pinfunction "CLKI/RC12/OSC1_63") (pintype "bidirectional"))
      (node (ref "X1") (pin "3") (pinfunction "2_3") (pintype "passive"))
    )
    (net (code "99") (name "Net-(IC1-CLKO{slash}RC15{slash}OSC2)") (class "Default")
      (node (ref "C61") (pin "1") (pinfunction "1_1") (pintype "passive"))
      (node (ref "IC1") (pin "64") (pinfunction "CLKO/RC15/OSC2_64") (pintype "bidirectional"))
      (node (ref "X1") (pin "1") (pinfunction "1_1") (pintype "passive"))
    )
    (net (code "100") (name "Net-(IC1-VCAP)") (class "Default")
      (node (ref "C53") (pin "1") (pinfunction "1_1") (pintype "passive"))
      (node (ref "C54") (pin "1") (pinfunction "1_1") (pintype "passive"))
      (node (ref "IC1") (pin "85") (pinfunction "VCAP_85") (pintype "input"))
    )
    (net (code "101") (name "Net-(IC5-OUT)") (class "Default")
      (node (ref "C19") (pin "1") (pinfunction "1_1") (pintype "passive"))
      (node (ref "C20") (pin "1") (pinfunction "1_1") (pintype "passive"))
      (node (ref "IC5") (pin "5") (pinfunction "OUT_5") (pintype "output"))
      (node (ref "R126") (pin "2") (pinfunction "2_2") (pintype "passive"))
    )
    (net (code "102") (name "Net-(IC6-HTH)") (class "Default")
      (node (ref "IC6") (pin "1") (pinfunction "HTH_1") (pintype "input"))
      (node (ref "R46") (pin "2") (pinfunction "2_2") (pintype "passive"))
      (node (ref "R47") (pin "1") (pinfunction "1_1") (pintype "passive"))
    )
    (net (code "103") (name "Net-(IC6-LTH)") (class "Default")
      (node (ref "IC6") (pin "3") (pinfunction "LTH_3") (pintype "input"))
      (node (ref "R33") (pin "1") (pinfunction "1_1") (pintype "passive"))
      (node (ref "R47") (pin "2") (pinfunction "2_2") (pintype "passive"))
    )
    (net (code "104") (name "Net-(IC6-VDD)") (class "Default")
      (node (ref "C35") (pin "1") (pinfunction "1_1") (pintype "passive"))
      (node (ref "IC6") (pin "5") (pinfunction "VDD_5") (pintype "input"))
      (node (ref "R28") (pin "1") (pinfunction "1_1") (pintype "passive"))
    )
    (net (code "105") (name "Net-(IC8-BOOST)") (class "Default")
      (node (ref "C25") (pin "2") (pinfunction "2_2") (pintype "passive"))
      (node (ref "IC8") (pin "2") (pinfunction "BOOST_2") (pintype "bidirectional"))
    )
    (net (code "106") (name "Net-(IC8-EN)") (class "Default")
      (node (ref "IC8") (pin "5") (pinfunction "EN_5") (pintype "bidirectional"))
      (node (ref "JP1") (pin "2") (pinfunction "2_2") (pintype "bidirectional"))
      (node (ref "R22") (pin "2") (pinfunction "2_2") (pintype "passive"))
    )
    (net (code "107") (name "Net-(IC8-FB)") (class "Default")
      (node (ref "C26") (pin "2") (pinfunction "2_2") (pintype "passive"))
      (node (ref "IC8") (pin "6") (pinfunction "FB_6") (pintype "bidirectional"))
      (node (ref "R19") (pin "1") (pinfunction "1_1") (pintype "passive"))
      (node (ref "R20") (pin "2") (pinfunction "2_2") (pintype "passive"))
    )
    (net (code "108") (name "Net-(IC8-RT)") (class "Default")
      (node (ref "IC8") (pin "8") (pinfunction "RT_8") (pintype "bidirectional"))
      (node (ref "R17") (pin "1") (pinfunction "1_1") (pintype "passive"))
    )
    (net (code "109") (name "Net-(IC8-SS)") (class "Default")
      (node (ref "IC8") (pin "7") (pinfunction "SS_7") (pintype "bidirectional"))
      (node (ref "R77") (pin "1") (pinfunction "1_1") (pintype "passive"))
    )
    (net (code "110") (name "Net-(IC8-SW)") (class "Default")
      (node (ref "C25") (pin "1") (pinfunction "1_1") (pintype "passive"))
      (node (ref "D7") (pin "K") (pinfunction "K_K") (pintype "passive"))
      (node (ref "IC8") (pin "3") (pinfunction "SW_3") (pintype "bidirectional"))
      (node (ref "L9") (pin "1") (pinfunction "1_1") (pintype "passive"))
    )
    (net (code "111") (name "Net-(IC10-OUT)") (class "Default")
      (node (ref "IC10") (pin "3") (pinfunction "OUT_3") (pintype "output"))
      (node (ref "R102") (pin "1") (pinfunction "1_1") (pintype "passive"))
    )
    (net (code "112") (name "Net-(IC10-VIN+)") (class "Default")
      (node (ref "C29") (pin "1") (pinfunction "1_1") (pintype "passive"))
      (node (ref "F1") (pin "1") (pinfunction "1_1") (pintype "passive"))
      (node (ref "IC10") (pin "5") (pinfunction "VIN+_5") (pintype "input"))
      (node (ref "R39") (pin "2") (pinfunction "2_2") (pintype "passive"))
    )
    (net (code "113") (name "Net-(IC11-WP)") (class "Default")
      (node (ref "IC11") (pin "7") (pinfunction "WP_7") (pintype "input"))
      (node (ref "R18") (pin "2") (pinfunction "2_2") (pintype "passive"))
      (node (ref "TP1") (pin "P$1") (pinfunction "TP_P$1") (pintype "passive"))
    )
    (net (code "114") (name "Net-(IC13-VIN)") (class "Default")
      (node (ref "C58") (pin "1") (pinfunction "1_1") (pintype "passive"))
      (node (ref "C59") (pin "1") (pinfunction "1_1") (pintype "passive"))
      (node (ref "IC13") (pin "1") (pinfunction "VIN_1") (pintype "bidirectional"))
      (node (ref "R93") (pin "2") (pinfunction "2_2") (pintype "passive"))
    )
    (net (code "115") (name "Net-(IC16A-+IN)") (class "Default")
      (node (ref "C62") (pin "1") (pinfunction "1_1") (pintype "passive"))
      (node (ref "IC16") (pin "3") (pinfunction "+IN_3") (pintype "input"))
      (node (ref "R95") (pin "2") (pinfunction "2_2") (pintype "passive"))
      (node (ref "R96") (pin "1") (pinfunction "1_1") (pintype "passive"))
    )
    (net (code "116") (name "Net-(IC16A--IN)") (class "Default")
      (node (ref "IC16") (pin "1") (pinfunction "OUT_1") (pintype "output"))
      (node (ref "IC16") (pin "2") (pinfunction "-IN_2") (pintype "input"))
      (node (ref "R101") (pin "2") (pinfunction "2_2") (pintype "passive"))
    )
    (net (code "117") (name "Net-(IC16B-+IN)") (class "Default")
      (node (ref "C63") (pin "1") (pinfunction "1_1") (pintype "passive"))
      (node (ref "IC16") (pin "5") (pinfunction "+IN_5") (pintype "input"))
      (node (ref "R98") (pin "2") (pinfunction "2_2") (pintype "passive"))
      (node (ref "R99") (pin "1") (pinfunction "1_1") (pintype "passive"))
    )
    (net (code "118") (name "Net-(IC16B--IN)") (class "Default")
      (node (ref "IC16") (pin "6") (pinfunction "-IN_6") (pintype "input"))
      (node (ref "IC16") (pin "7") (pinfunction "OUT_7") (pintype "output"))
      (node (ref "R100") (pin "2") (pinfunction "2_2") (pintype "passive"))
    )
    (net (code "119") (name "Net-(IC16C-V+)") (class "Default")
      (node (ref "C67") (pin "1") (pinfunction "1_1") (pintype "passive"))
      (node (ref "IC16") (pin "8") (pinfunction "V+_8") (pintype "input"))
      (node (ref "R103") (pin "1") (pinfunction "1_1") (pintype "passive"))
    )
    (net (code "120") (name "Net-(J5-Pad4)") (class "Default")
      (node (ref "J5") (pin "4") (pinfunction "4_4") (pintype "bidirectional"))
      (node (ref "R62") (pin "1") (pinfunction "1_1") (pintype "passive"))
    )
    (net (code "121") (name "Net-(J6-Pad4)") (class "Default")
      (node (ref "J6") (pin "4") (pinfunction "4_4") (pintype "bidirectional"))
      (node (ref "R78") (pin "1") (pinfunction "1_1") (pintype "passive"))
    )
    (net (code "122") (name "Net-(J7-Pad2)") (class "Default")
      (node (ref "J7") (pin "2") (pinfunction "2_2") (pintype "passive"))
      (node (ref "R68") (pin "1") (pinfunction "1_1") (pintype "passive"))
    )
    (net (code "123") (name "Net-(J8-Pad2)") (class "Default")
      (node (ref "J8") (pin "2") (pinfunction "2_2") (pintype "passive"))
      (node (ref "R84") (pin "1") (pinfunction "1_1") (pintype "passive"))
    )
    (net (code "124") (name "Net-(J9-Pad2)") (class "Default")
      (node (ref "J9") (pin "2") (pinfunction "2_2") (pintype "passive"))
      (node (ref "R110") (pin "1") (pinfunction "1_1") (pintype "passive"))
      (node (ref "R114") (pin "1") (pinfunction "1_1") (pintype "passive"))
    )
    (net (code "125") (name "Net-(J10-Pad2)") (class "Default")
      (node (ref "J10") (pin "2") (pinfunction "2_2") (pintype "passive"))
      (node (ref "R116") (pin "1") (pinfunction "1_1") (pintype "passive"))
      (node (ref "R122") (pin "1") (pinfunction "1_1") (pintype "passive"))
    )
    (net (code "126") (name "Net-(J12-VDD)") (class "Default")
      (node (ref "C85") (pin "1") (pinfunction "1_1") (pintype "passive"))
      (node (ref "D6") (pin "A") (pinfunction "A_A") (pintype "passive"))
      (node (ref "IC15") (pin "4") (pinfunction "4_4") (pintype "input"))
      (node (ref "J12") (pin "1_VCC") (pinfunction "VDD_1_VCC") (pintype "bidirectional"))
      (node (ref "R128") (pin "1") (pinfunction "1_1") (pintype "passive"))
      (node (ref "TP5") (pin "P$1") (pinfunction "TP_P$1") (pintype "passive"))
    )
    (net (code "127") (name "Net-(JP1-Pad1)") (class "Default")
      (node (ref "JP1") (pin "1") (pinfunction "1_1") (pintype "bidirectional"))
      (node (ref "R21") (pin "1") (pinfunction "1_1") (pintype "passive"))
    )
    (net (code "128") (name "Net-(L7-Pad1)") (class "Default")
      (node (ref "L7") (pin "1") (pinfunction "1_1") (pintype "passive"))
      (node (ref "R108") (pin "1") (pinfunction "1_1") (pintype "passive"))
    )
    (net (code "129") (name "Net-(L8-Pad1)") (class "Default")
      (node (ref "L8") (pin "1") (pinfunction "1_1") (pintype "passive"))
      (node (ref "R109") (pin "1") (pinfunction "1_1") (pintype "passive"))
    )
    (net (code "130") (name "Net-(L13-Pad2)") (class "Default")
      (node (ref "L13") (pin "2") (pinfunction "2_2") (pintype "passive"))
      (node (ref "R92") (pin "1") (pinfunction "1_1") (pintype "passive"))
    )
    (net (code "131") (name "Net-(Q1A-G)") (class "Default")
      (node (ref "C21") (pin "2") (pinfunction "2_2") (pintype "passive"))
      (node (ref "Q1") (pin "2") (pinfunction "G_2") (pintype "passive"))
      (node (ref "R10") (pin "2") (pinfunction "2_2") (pintype "passive"))
      (node (ref "R9") (pin "1") (pinfunction "1_1") (pintype "passive"))
    )
    (net (code "132") (name "Net-(Q1A-S)") (class "Default")
      (node (ref "Q1") (pin "1") (pinfunction "S_1") (pintype "passive"))
      (node (ref "R8") (pin "1") (pinfunction "1_1") (pintype "passive"))
    )
    (net (code "133") (name "Net-(Q1B-G)") (class "Default")
      (node (ref "C70") (pin "2") (pinfunction "2_2") (pintype "passive"))
      (node (ref "Q1") (pin "5") (pinfunction "G_5") (pintype "passive"))
      (node (ref "R75") (pin "1") (pinfunction "1_1") (pintype "passive"))
      (node (ref "R82") (pin "2") (pinfunction "2_2") (pintype "passive"))
    )
    (net (code "134") (name "Net-(Q1B-S)") (class "Default")
      (node (ref "Q1") (pin "4") (pinfunction "S_4") (pintype "passive"))
      (node (ref "R106") (pin "1") (pinfunction "1_1") (pintype "passive"))
    )
    (net (code "135") (name "Net-(Q2A-G)") (class "Default")
      (node (ref "C68") (pin "2") (pinfunction "2_2") (pintype "passive"))
      (node (ref "Q2") (pin "2") (pinfunction "G_2") (pintype "passive"))
      (node (ref "R107") (pin "1") (pinfunction "1_1") (pintype "passive"))
      (node (ref "R87") (pin "2") (pinfunction "2_2") (pintype "passive"))
    )
    (net (code "136") (name "Net-(Q2A-S)") (class "Default")
      (node (ref "Q2") (pin "1") (pinfunction "S_1") (pintype "passive"))
      (node (ref "R104") (pin "1") (pinfunction "1_1") (pintype "passive"))
    )
    (net (code "137") (name "Net-(Q2B-G)") (class "Default")
      (node (ref "C69") (pin "2") (pinfunction "2_2") (pintype "passive"))
      (node (ref "Q2") (pin "5") (pinfunction "G_5") (pintype "passive"))
      (node (ref "R24") (pin "1") (pinfunction "1_1") (pintype "passive"))
      (node (ref "R65") (pin "2") (pinfunction "2_2") (pintype "passive"))
    )
    (net (code "138") (name "Net-(Q2B-S)") (class "Default")
      (node (ref "Q2") (pin "4") (pinfunction "S_4") (pintype "passive"))
      (node (ref "R105") (pin "1") (pinfunction "1_1") (pintype "passive"))
    )
    (net (code "139") (name "Net-(Q3A-D)") (class "Default")
      (node (ref "Q3") (pin "6") (pinfunction "D_6") (pintype "passive"))
      (node (ref "R111") (pin "2") (pinfunction "2_2") (pintype "passive"))
      (node (ref "R115") (pin "2") (pinfunction "2_2") (pintype "passive"))
    )
    (net (code "140") (name "Net-(Q3A-G)") (class "Default")
      (node (ref "Q3") (pin "2") (pinfunction "G_2") (pintype "passive"))
      (node (ref "R112") (pin "1") (pinfunction "1_1") (pintype "passive"))
      (node (ref "R113") (pin "1") (pinfunction "1_1") (pintype "passive"))
    )
    (net (code "141") (name "Net-(Q4A-D)") (class "Default")
      (node (ref "C33") (pin "2") (pinfunction "2_2") (pintype "passive"))
      (node (ref "Q4") (pin "6") (pinfunction "D_6") (pintype "passive"))
      (node (ref "Q5") (pin "1") (pinfunction "G_1") (pintype "bidirectional"))
      (node (ref "R42") (pin "2") (pinfunction "2_2") (pintype "passive"))
    )
    (net (code "142") (name "Net-(Q4A-S)") (class "Default")
      (node (ref "Q4") (pin "1") (pinfunction "S_1") (pintype "passive"))
      (node (ref "R40") (pin "2") (pinfunction "2_2") (pintype "passive"))
    )
    (net (code "143") (name "Net-(Q4B-D)") (class "Default")
      (node (ref "C34") (pin "2") (pinfunction "2_2") (pintype "passive"))
      (node (ref "Q4") (pin "3") (pinfunction "D_3") (pintype "passive"))
      (node (ref "Q5") (pin "3") (pinfunction "G_3") (pintype "bidirectional"))
      (node (ref "R45") (pin "2") (pinfunction "2_2") (pintype "passive"))
    )
    (net (code "144") (name "Net-(Q4B-S)") (class "Default")
      (node (ref "Q4") (pin "4") (pinfunction "S_4") (pintype "passive"))
      (node (ref "R43") (pin "2") (pinfunction "2_2") (pintype "passive"))
    )
    (net (code "145") (name "Net-(Q5A-D)") (class "Default")
      (node (ref "F1") (pin "2") (pinfunction "2_2") (pintype "passive"))
      (node (ref "Q5") (pin "6") (pinfunction "D_6") (pintype "bidirectional"))
      (node (ref "R132") (pin "1") (pinfunction "1_1") (pintype "passive"))
      (node (ref "R35") (pin "1") (pinfunction "1_1") (pintype "passive"))
      (node (ref "R37") (pin "1") (pinfunction "1_1") (pintype "passive"))
      (node (ref "R97") (pin "1") (pinfunction "1_1") (pintype "passive"))
    )
    (net (code "146") (name "Net-(Q6A-G)") (class "Default")
      (node (ref "C42") (pin "2") (pinfunction "2_2") (pintype "passive"))
      (node (ref "Q6") (pin "1") (pinfunction "G_1") (pintype "bidirectional"))
      (node (ref "Q7") (pin "6") (pinfunction "D_6") (pintype "passive"))
      (node (ref "R50") (pin "2") (pinfunction "2_2") (pintype "passive"))
    )
    (net (code "147") (name "Net-(Q6B-G)") (class "Default")
      (node (ref "C43") (pin "2") (pinfunction "2_2") (pintype "passive"))
      (node (ref "Q6") (pin "3") (pinfunction "G_3") (pintype "bidirectional"))
      (node (ref "Q7") (pin "3") (pinfunction "D_3") (pintype "passive"))
      (node (ref "R55") (pin "2") (pinfunction "2_2") (pintype "passive"))
    )
    (net (code "148") (name "Net-(Q7A-S)") (class "Default")
      (node (ref "Q7") (pin "1") (pinfunction "S_1") (pintype "passive"))
      (node (ref "R51") (pin "2") (pinfunction "2_2") (pintype "passive"))
    )
    (net (code "149") (name "Net-(Q7B-S)") (class "Default")
      (node (ref "Q7") (pin "4") (pinfunction "S_4") (pintype "passive"))
      (node (ref "R53") (pin "1") (pinfunction "1_1") (pintype "passive"))
    )
    (net (code "150") (name "Net-(Q8A-G)") (class "Default")
      (node (ref "C44") (pin "2") (pinfunction "2_2") (pintype "passive"))
      (node (ref "Q8") (pin "1") (pinfunction "G_1") (pintype "bidirectional"))
      (node (ref "Q9") (pin "6") (pinfunction "D_6") (pintype "passive"))
      (node (ref "R56") (pin "2") (pinfunction "2_2") (pintype "passive"))
    )
    (net (code "151") (name "Net-(Q8B-G)") (class "Default")
      (node (ref "C45") (pin "2") (pinfunction "2_2") (pintype "passive"))
      (node (ref "Q8") (pin "3") (pinfunction "G_3") (pintype "bidirectional"))
      (node (ref "Q9") (pin "3") (pinfunction "D_3") (pintype "passive"))
      (node (ref "R61") (pin "2") (pinfunction "2_2") (pintype "passive"))
    )
    (net (code "152") (name "Net-(Q9A-S)") (class "Default")
      (node (ref "Q9") (pin "1") (pinfunction "S_1") (pintype "passive"))
      (node (ref "R57") (pin "2") (pinfunction "2_2") (pintype "passive"))
    )
    (net (code "153") (name "Net-(Q9B-S)") (class "Default")
      (node (ref "Q9") (pin "4") (pinfunction "S_4") (pintype "passive"))
      (node (ref "R59") (pin "1") (pinfunction "1_1") (pintype "passive"))
    )
    (net (code "154") (name "Net-(Q10A-D)") (class "Default")
      (node (ref "Q10") (pin "6") (pinfunction "D_6") (pintype "passive"))
      (node (ref "R79") (pin "2") (pinfunction "2_2") (pintype "passive"))
    )
    (net (code "155") (name "Net-(Q10A-S)") (class "Default")
      (node (ref "Q10") (pin "1") (pinfunction "S_1") (pintype "passive"))
      (node (ref "Q10") (pin "5") (pinfunction "G_5") (pintype "passive"))
      (node (ref "R80") (pin "1") (pinfunction "1_1") (pintype "passive"))
    )
    (net (code "156") (name "Net-(Q11A-D)") (class "Default")
      (node (ref "Q11") (pin "6") (pinfunction "D_6") (pintype "passive"))
      (node (ref "R63") (pin "2") (pinfunction "2_2") (pintype "passive"))
    )
    (net (code "157") (name "Net-(Q11A-S)") (class "Default")
      (node (ref "Q11") (pin "1") (pinfunction "S_1") (pintype "passive"))
      (node (ref "Q11") (pin "5") (pinfunction "G_5") (pintype "passive"))
      (node (ref "R64") (pin "1") (pinfunction "1_1") (pintype "passive"))
    )
    (net (code "158") (name "Net-(Q12A-D)") (class "Default")
      (node (ref "Q12") (pin "6") (pinfunction "D_6") (pintype "passive"))
      (node (ref "R85") (pin "2") (pinfunction "2_2") (pintype "passive"))
    )
    (net (code "159") (name "Net-(Q12A-S)") (class "Default")
      (node (ref "Q12") (pin "1") (pinfunction "S_1") (pintype "passive"))
      (node (ref "Q12") (pin "5") (pinfunction "G_5") (pintype "passive"))
      (node (ref "R86") (pin "1") (pinfunction "1_1") (pintype "passive"))
    )
    (net (code "160") (name "Net-(Q13A-D)") (class "Default")
      (node (ref "Q13") (pin "6") (pinfunction "D_6") (pintype "passive"))
      (node (ref "R69") (pin "2") (pinfunction "2_2") (pintype "passive"))
    )
    (net (code "161") (name "Net-(Q13A-S)") (class "Default")
      (node (ref "Q13") (pin "1") (pinfunction "S_1") (pintype "passive"))
      (node (ref "Q13") (pin "5") (pinfunction "G_5") (pintype "passive"))
      (node (ref "R70") (pin "1") (pinfunction "1_1") (pintype "passive"))
    )
    (net (code "162") (name "Net-(Q14A-D)") (class "Default")
      (node (ref "Q14") (pin "6") (pinfunction "D_6") (pintype "passive"))
      (node (ref "R117") (pin "2") (pinfunction "2_2") (pintype "passive"))
      (node (ref "R123") (pin "2") (pinfunction "2_2") (pintype "passive"))
    )
    (net (code "163") (name "Net-(Q14A-G)") (class "Default")
      (node (ref "Q14") (pin "2") (pinfunction "G_2") (pintype "passive"))
      (node (ref "R118") (pin "1") (pinfunction "1_1") (pintype "passive"))
      (node (ref "R119") (pin "1") (pinfunction "1_1") (pintype "passive"))
    )
    (net (code "164") (name "Net-(R23-Pad1)") (class "Default")
      (node (ref "R23") (pin "1") (pinfunction "1_1") (pintype "passive"))
      (node (ref "R49") (pin "2") (pinfunction "2_2") (pintype "passive"))
    )
    (net (code "165") (name "Net-(R35-Pad2)") (class "Default")
      (node (ref "R35") (pin "2") (pinfunction "2_2") (pintype "passive"))
      (node (ref "R36") (pin "1") (pinfunction "1_1") (pintype "passive"))
      (node (ref "R37") (pin "2") (pinfunction "2_2") (pintype "passive"))
      (node (ref "R38") (pin "1") (pinfunction "1_1") (pintype "passive"))
    )
    (net (code "166") (name "Net-(R94-Pad2)") (class "Default")
      (node (ref "R94") (pin "2") (pinfunction "2_2") (pintype "passive"))
      (node (ref "R95") (pin "1") (pinfunction "1_1") (pintype "passive"))
    )
    (net (code "167") (name "Net-(R97-Pad2)") (class "Default")
      (node (ref "R97") (pin "2") (pinfunction "2_2") (pintype "passive"))
      (node (ref "R98") (pin "1") (pinfunction "1_1") (pintype "passive"))
    )
    (net (code "168") (name "OE-SRAM") (class "Default")
      (node (ref "IC1") (pin "82") (pinfunction "RPD5/PMRD/RD5_82") (pintype "bidirectional"))
      (node (ref "IC2") (pin "28") (pinfunction "~{OE}_28") (pintype "input"))
      (node (ref "R3") (pin "1") (pinfunction "1_1") (pintype "passive"))
    )
    (net (code "169") (name "PCLK") (class "Default")
      (node (ref "IC1") (pin "76") (pinfunction "AN24/RPD1/RD1_76") (pintype "bidirectional"))
      (node (ref "J1") (pin "17") (pinfunction "17_17") (pintype "passive"))
      (node (ref "J2") (pin "17") (pinfunction "17_17") (pintype "passive"))
      (node (ref "O35") (pin "P$1") (pinfunction "TP_P$1") (pintype "passive"))
      (node (ref "T17") (pin "P$1") (pinfunction "TP_P$1") (pintype "passive"))
    )
    (net (code "170") (name "PGC") (class "Default")
      (node (ref "IC1") (pin "24") (pinfunction "PGEC1/AN1/RPB1/CTED12/RB1_24") (pintype "bidirectional"))
      (node (ref "J17") (pin "5") (pinfunction "5_5") (pintype "passive"))
      (node (ref "R131") (pin "1") (pinfunction "1_1") (pintype "passive"))
    )
    (net (code "171") (name "PGD") (class "Default")
      (node (ref "IC1") (pin "25") (pinfunction "PGED1/AN0/RPB0/RB0_25") (pintype "bidirectional"))
      (node (ref "J17") (pin "4") (pinfunction "4_4") (pintype "passive"))
      (node (ref "R130") (pin "2") (pinfunction "2_2") (pintype "passive"))
    )
    (net (code "172") (name "POWER-GOOD") (class "Default")
      (node (ref "IC6") (pin "4") (pinfunction "OUT_4") (pintype "output"))
      (node (ref "R130") (pin "1") (pinfunction "1_1") (pintype "passive"))
      (node (ref "T45") (pin "P$1") (pinfunction "TP_P$1") (pintype "passive"))
      (node (ref "TP2") (pin "P$1") (pinfunction "TP_P$1") (pintype "passive"))
    )
    (net (code "173") (name "PWDN-CAM1") (class "Default")
      (node (ref "IC1") (pin "97") (pinfunction "TRD0/RG13_97") (pintype "bidirectional"))
      (node (ref "J1") (pin "8") (pinfunction "8_8") (pintype "passive"))
      (node (ref "O22") (pin "P$1") (pinfunction "TP_P$1") (pintype "passive"))
      (node (ref "R12") (pin "1") (pinfunction "1_1") (pintype "passive"))
      (node (ref "T20") (pin "P$1") (pinfunction "TP_P$1") (pintype "passive"))
    )
    (net (code "174") (name "PWDN-CAM2") (class "Default")
      (node (ref "IC1") (pin "39") (pinfunction "RPF13/RF13_39") (pintype "bidirectional"))
      (node (ref "J2") (pin "8") (pinfunction "8_8") (pintype "passive"))
      (node (ref "O18") (pin "P$1") (pinfunction "TP_P$1") (pintype "passive"))
      (node (ref "R16") (pin "1") (pinfunction "1_1") (pintype "passive"))
      (node (ref "T21") (pin "P$1") (pinfunction "TP_P$1") (pintype "passive"))
    )
    (net (code "175") (name "REF-EN") (class "Default")
      (node (ref "IC1") (pin "28") (pinfunction "VREF-/CVREF-/PMA7/RA9_28") (pintype "bidirectional"))
      (node (ref "R93") (pin "1") (pinfunction "1_1") (pintype "passive"))
    )
    (net (code "176") (name "REF2,5V") (class "Default")
      (node (ref "C57") (pin "1") (pinfunction "1_1") (pintype "passive"))
      (node (ref "IC1") (pin "29") (pinfunction "VREF+/CVREF+/PMA6/RA10_29") (pintype "bidirectional"))
      (node (ref "IC13") (pin "2") (pinfunction "VOUT_2") (pintype "bidirectional"))
    )
    (net (code "177") (name "RESET-CAM1") (class "Default")
      (node (ref "C76") (pin "1") (pinfunction "1_1") (pintype "passive"))
      (node (ref "J1") (pin "6") (pinfunction "6_6") (pintype "passive"))
      (node (ref "R11") (pin "1") (pinfunction "1_1") (pintype "passive"))
    )
    (net (code "178") (name "RESET-CAM2") (class "Default")
      (node (ref "C75") (pin "1") (pinfunction "1_1") (pintype "passive"))
      (node (ref "J2") (pin "6") (pinfunction "6_6") (pintype "passive"))
      (node (ref "R15") (pin "1") (pinfunction "1_1") (pintype "passive"))
    )
    (net (code "179") (name "SCL1-EEPROM") (class "Default")
      (node (ref "IC1") (pin "66") (pinfunction "SCL1/RPA14/RA14_66") (pintype "bidirectional"))
      (node (ref "IC11") (pin "6") (pinfunction "SCL_6") (pintype "input"))
      (node (ref "IC7") (pin "6") (pinfunction "SCL_6") (pintype "input"))
      (node (ref "R26") (pin "2") (pinfunction "2_2") (pintype "passive"))
    )
    (net (code "180") (name "SCLK2-SPI") (class "Default")
      (node (ref "IC1") (pin "10") (pinfunction "AN16/C1IND/RPG6/SCK2/PMA5/RG6_10") (pintype "bidirectional"))
      (node (ref "IC9") (pin "6") (pinfunction "C_6") (pintype "input"))
      (node (ref "J11") (pin "5") (pinfunction "CLK_5") (pintype "passive"))
      (node (ref "J15") (pin "12") (pinfunction "12_12") (pintype "passive"))
    )
    (net (code "181") (name "SD-CS") (class "Default")
      (node (ref "IC1") (pin "9") (pinfunction "RPC4/CTED7/RC4_9") (pintype "bidirectional"))
      (node (ref "J11") (pin "2") (pinfunction "CS/DAT3_2") (pintype "passive"))
      (node (ref "O5") (pin "P$1") (pinfunction "TP_P$1") (pintype "passive"))
      (node (ref "R127") (pin "2") (pinfunction "2_2") (pintype "passive"))
      (node (ref "T29") (pin "P$1") (pinfunction "TP_P$1") (pintype "passive"))
    )
    (net (code "182") (name "SDA1-EEPROM") (class "Default")
      (node (ref "IC1") (pin "67") (pinfunction "SDA1/RPA15/RA15_67") (pintype "bidirectional"))
      (node (ref "IC11") (pin "5") (pinfunction "SDA_5") (pintype "bidirectional"))
      (node (ref "IC7") (pin "5") (pinfunction "SDA_5") (pintype "bidirectional"))
      (node (ref "R27") (pin "2") (pinfunction "2_2") (pintype "passive"))
    )
    (net (code "183") (name "SDI2-MISO") (class "Default")
      (node (ref "IC1") (pin "22") (pinfunction "PGED3/AN3/C2INA/RPB3/RB3_22") (pintype "bidirectional"))
      (node (ref "IC9") (pin "2") (pinfunction "Q_2") (pintype "bidirectional"))
      (node (ref "J11") (pin "7") (pinfunction "DO/DAT0_7") (pintype "passive"))
      (node (ref "J15") (pin "11") (pinfunction "11_11") (pintype "passive"))
      (node (ref "O13") (pin "P$1") (pinfunction "TP_P$1") (pintype "passive"))
      (node (ref "T22") (pin "P$1") (pinfunction "TP_P$1") (pintype "passive"))
    )
    (net (code "184") (name "SDO2-MOSI") (class "Default")
      (node (ref "IC1") (pin "20") (pinfunction "AN5/C1INA/RPB5/RB5_20") (pintype "bidirectional"))
      (node (ref "IC9") (pin "5") (pinfunction "D_5") (pintype "input"))
      (node (ref "J11") (pin "3") (pinfunction "DI/CMD_3") (pintype "passive"))
      (node (ref "J15") (pin "14") (pinfunction "14_14") (pintype "passive"))
      (node (ref "O12") (pin "P$1") (pinfunction "TP_P$1") (pintype "passive"))
      (node (ref "T23") (pin "P$1") (pinfunction "TP_P$1") (pintype "passive"))
    )
    (net (code "185") (name "SIO-C-CAM") (class "Default")
      (node (ref "IC1") (pin "58") (pinfunction "SCL2/RA2_58") (pintype "bidirectional"))
      (node (ref "J1") (pin "5") (pinfunction "5_5") (pintype "passive"))
      (node (ref "J2") (pin "5") (pinfunction "5_5") (pintype "passive"))
      (node (ref "R13") (pin "1") (pinfunction "1_1") (pintype "passive"))
    )
    (net (code "186") (name "SIO-D-CAM") (class "Default")
      (node (ref "IC1") (pin "59") (pinfunction "SDA2/RA3_59") (pintype "bidirectional"))
      (node (ref "J1") (pin "3") (pinfunction "3_3") (pintype "passive"))
      (node (ref "J2") (pin "3") (pinfunction "3_3") (pintype "passive"))
      (node (ref "R14") (pin "1") (pinfunction "1_1") (pintype "passive"))
    )
    (net (code "187") (name "VBAT") (class "Default")
      (node (ref "C22") (pin "1") (pinfunction "1_1") (pintype "passive"))
      (node (ref "C23") (pin "1") (pinfunction "1_1") (pintype "passive"))
      (node (ref "C42") (pin "1") (pinfunction "1_1") (pintype "passive"))
      (node (ref "C43") (pin "1") (pinfunction "1_1") (pintype "passive"))
      (node (ref "C44") (pin "1") (pinfunction "1_1") (pintype "passive"))
      (node (ref "C45") (pin "1") (pinfunction "1_1") (pintype "passive"))
      (node (ref "C83") (pin "1") (pinfunction "1_1") (pintype "passive"))
      (node (ref "C84") (pin "1") (pinfunction "1_1") (pintype "passive"))
      (node (ref "IC10") (pin "4") (pinfunction "VIN-_4") (pintype "input"))
      (node (ref "IC8") (pin "4") (pinfunction "VIN_4") (pintype "bidirectional"))
      (node (ref "J5") (pin "5") (pinfunction "5_5") (pintype "bidirectional"))
      (node (ref "J6") (pin "5") (pinfunction "5_5") (pintype "bidirectional"))
      (node (ref "J7") (pin "1") (pinfunction "1_1") (pintype "passive"))
      (node (ref "J8") (pin "1") (pinfunction "1_1") (pintype "passive"))
      (node (ref "JP1") (pin "3") (pinfunction "3_3") (pintype "bidirectional"))
      (node (ref "Q6") (pin "2") (pinfunction "S_2") (pintype "bidirectional"))
      (node (ref "Q6") (pin "5") (pinfunction "S_5") (pintype "bidirectional"))
      (node (ref "Q8") (pin "2") (pinfunction "S_2") (pintype "bidirectional"))
      (node (ref "Q8") (pin "5") (pinfunction "S_5") (pintype "bidirectional"))
      (node (ref "R124") (pin "1") (pinfunction "1_1") (pintype "passive"))
      (node (ref "R125") (pin "1") (pinfunction "1_1") (pintype "passive"))
      (node (ref "R22") (pin "1") (pinfunction "1_1") (pintype "passive"))
      (node (ref "R33") (pin "2") (pinfunction "2_2") (pintype "passive"))
      (node (ref "R39") (pin "1") (pinfunction "1_1") (pintype "passive"))
      (node (ref "R50") (pin "1") (pinfunction "1_1") (pintype "passive"))
      (node (ref "R55") (pin "1") (pinfunction "1_1") (pintype "passive"))
      (node (ref "R56") (pin "1") (pinfunction "1_1") (pintype "passive"))
      (node (ref "R61") (pin "1") (pinfunction "1_1") (pintype "passive"))
    )
    (net (code "188") (name "VBAT-LAN") (class "Default")
      (node (ref "D3") (pin "C") (pinfunction "C_C") (pintype "passive"))
      (node (ref "J3") (pin "1") (pinfunction "1_1") (pintype "passive"))
      (node (ref "J3") (pin "3") (pinfunction "3_3") (pintype "passive"))
      (node (ref "J4") (pin "1") (pinfunction "1_1") (pintype "passive"))
      (node (ref "J4") (pin "3") (pinfunction "3_3") (pintype "passive"))
      (node (ref "L11") (pin "2") (pinfunction "2_2") (pintype "passive"))
    )
    (net (code "189") (name "VBAT-LAN-F") (class "Default")
      (node (ref "C33") (pin "1") (pinfunction "1_1") (pintype "passive"))
      (node (ref "C34") (pin "1") (pinfunction "1_1") (pintype "passive"))
      (node (ref "D6") (pin "K") (pinfunction "K_K") (pintype "passive"))
      (node (ref "L11") (pin "1") (pinfunction "1_1") (pintype "passive"))
      (node (ref "Q5") (pin "2") (pinfunction "S_2") (pintype "bidirectional"))
      (node (ref "Q5") (pin "5") (pinfunction "S_5") (pintype "bidirectional"))
      (node (ref "R36") (pin "2") (pinfunction "2_2") (pintype "passive"))
      (node (ref "R38") (pin "2") (pinfunction "2_2") (pintype "passive"))
      (node (ref "R42") (pin "1") (pinfunction "1_1") (pintype "passive"))
      (node (ref "R45") (pin "1") (pinfunction "1_1") (pintype "passive"))
      (node (ref "R94") (pin "1") (pinfunction "1_1") (pintype "passive"))
      (node (ref "TP6") (pin "P$1") (pinfunction "TP_P$1") (pintype "passive"))
    )
    (net (code "190") (name "VBAT-ON") (class "Default")
      (node (ref "IC1") (pin "52") (pinfunction "RPF2/RF2_52") (pintype "bidirectional"))
      (node (ref "O42") (pin "P$1") (pinfunction "TP_P$1") (pintype "passive"))
      (node (ref "Q4") (pin "2") (pinfunction "G_2") (pintype "passive"))
      (node (ref "R132") (pin "2") (pinfunction "2_2") (pintype "passive"))
      (node (ref "R41") (pin "1") (pinfunction "1_1") (pintype "passive"))
      (node (ref "T5") (pin "P$1") (pinfunction "TP_P$1") (pintype "passive"))
    )
    (net (code "191") (name "VBAT-SENSE") (class "Default")
      (node (ref "C64") (pin "1") (pinfunction "1_1") (pintype "passive"))
      (node (ref "IC1") (pin "26") (pinfunction "PGEC2/AN6/RPB6/RB6_26") (pintype "bidirectional"))
      (node (ref "O15") (pin "P$1") (pinfunction "TP_P$1") (pintype "passive"))
      (node (ref "R100") (pin "1") (pinfunction "1_1") (pintype "passive"))
      (node (ref "T37") (pin "P$1") (pinfunction "TP_P$1") (pintype "passive"))
    )
    (net (code "192") (name "VBATLAN-SENSE") (class "Default")
      (node (ref "C36") (pin "1") (pinfunction "1_1") (pintype "passive"))
      (node (ref "IC1") (pin "27") (pinfunction "PGED2/AN7/RPB7/CTED3/RB7_27") (pintype "bidirectional"))
      (node (ref "O16") (pin "P$1") (pinfunction "TP_P$1") (pintype "passive"))
      (node (ref "R101") (pin "1") (pinfunction "1_1") (pintype "passive"))
      (node (ref "T38") (pin "P$1") (pinfunction "TP_P$1") (pintype "passive"))
    )
    (net (code "193") (name "VBUS") (class "Default")
      (node (ref "IC1") (pin "54") (pinfunction "VBUS_54") (pintype "input"))
      (node (ref "R128") (pin "2") (pinfunction "2_2") (pintype "passive"))
    )
    (net (code "194") (name "VPS-ON") (class "Default")
      (node (ref "IC1") (pin "53") (pinfunction "RPF8/RF8_53") (pintype "bidirectional"))
      (node (ref "O41") (pin "P$1") (pinfunction "TP_P$1") (pintype "passive"))
      (node (ref "Q4") (pin "5") (pinfunction "G_5") (pintype "passive"))
      (node (ref "R44") (pin "1") (pinfunction "1_1") (pintype "passive"))
      (node (ref "T7") (pin "P$1") (pinfunction "TP_P$1") (pintype "passive"))
    )
    (net (code "195") (name "VPS-PWR") (class "Default")
      (node (ref "D4") (pin "C") (pinfunction "C_C") (pintype "passive"))
      (node (ref "J3") (pin "6") (pinfunction "6_6") (pintype "passive"))
      (node (ref "J4") (pin "6") (pinfunction "6_6") (pintype "passive"))
      (node (ref "L10") (pin "2") (pinfunction "2_2") (pintype "passive"))
    )
    (net (code "196") (name "VPS-PWR-F") (class "Default")
      (node (ref "L10") (pin "1") (pinfunction "1_1") (pintype "passive"))
      (node (ref "Q5") (pin "4") (pinfunction "D_4") (pintype "bidirectional"))
      (node (ref "R23") (pin "2") (pinfunction "2_2") (pintype "passive"))
    )
    (net (code "197") (name "VPS-SENSE") (class "Default")
      (node (ref "C65") (pin "1") (pinfunction "1_1") (pintype "passive"))
      (node (ref "IC1") (pin "12") (pinfunction "AN18/C2IND/RPG8/PMA3/RG8_12") (pintype "bidirectional"))
      (node (ref "O7") (pin "P$1") (pinfunction "TP_P$1") (pintype "passive"))
      (node (ref "R48") (pin "2") (pinfunction "2_2") (pintype "passive"))
      (node (ref "R49") (pin "1") (pinfunction "1_1") (pintype "passive"))
      (node (ref "T3") (pin "P$1") (pinfunction "TP_P$1") (pintype "passive"))
    )
    (net (code "198") (name "VSYNC") (class "Default")
      (node (ref "IC1") (pin "8") (pinfunction "RPC3/RC3_8") (pintype "bidirectional"))
      (node (ref "J1") (pin "7") (pinfunction "7_7") (pintype "passive"))
      (node (ref "J2") (pin "7") (pinfunction "7_7") (pintype "passive"))
      (node (ref "O4") (pin "P$1") (pinfunction "TP_P$1") (pintype "passive"))
      (node (ref "T19") (pin "P$1") (pinfunction "TP_P$1") (pintype "passive"))
    )
    (net (code "199") (name "WAKE-SW") (class "Default")
      (node (ref "IC1") (pin "72") (pinfunction "RPD0/INT0/RD0_72") (pintype "bidirectional"))
      (node (ref "J14") (pin "5") (pinfunction "5_5") (pintype "passive"))
      (node (ref "O38") (pin "P$1") (pinfunction "TP_P$1") (pintype "passive"))
      (node (ref "T42") (pin "P$1") (pinfunction "TP_P$1") (pintype "passive"))
    )
    (net (code "200") (name "WE-SRAM") (class "Default")
      (node (ref "IC1") (pin "81") (pinfunction "RPD4/PMWR/RD4_81") (pintype "bidirectional"))
      (node (ref "IC2") (pin "11") (pinfunction "~{WE}_11") (pintype "input"))
      (node (ref "R4") (pin "1") (pinfunction "1_1") (pintype "passive"))
    )
    (net (code "201") (name "XCLK1") (class "Default")
      (node (ref "IC1") (pin "7") (pinfunction "RPC2/RC2_7") (pintype "bidirectional"))
      (node (ref "J1") (pin "13") (pinfunction "13_13") (pintype "passive"))
      (node (ref "J2") (pin "13") (pinfunction "13_13") (pintype "passive"))
      (node (ref "O3") (pin "P$1") (pinfunction "TP_P$1") (pintype "passive"))
      (node (ref "T16") (pin "P$1") (pinfunction "TP_P$1") (pintype "passive"))
    )
    (net (code "202") (name "Y2") (class "Default")
      (node (ref "IC1") (pin "68") (pinfunction "RPD8/RTCC/RD8_68") (pintype "bidirectional"))
      (node (ref "J1") (pin "19") (pinfunction "19_19") (pintype "passive"))
      (node (ref "J2") (pin "19") (pinfunction "19_19") (pintype "passive"))
    )
    (net (code "203") (name "Y3") (class "Default")
      (node (ref "IC1") (pin "69") (pinfunction "RPD9/RD9_69") (pintype "bidirectional"))
      (node (ref "J1") (pin "21") (pinfunction "21_21") (pintype "passive"))
      (node (ref "J2") (pin "21") (pinfunction "21_21") (pintype "passive"))
    )
    (net (code "204") (name "Y4") (class "Default")
      (node (ref "IC1") (pin "70") (pinfunction "RPD10/SCK1/PMCS2/RD10_70") (pintype "bidirectional"))
      (node (ref "J1") (pin "22") (pinfunction "22_22") (pintype "passive"))
      (node (ref "J2") (pin "22") (pinfunction "22_22") (pintype "passive"))
    )
    (net (code "205") (name "Y5") (class "Default")
      (node (ref "IC1") (pin "71") (pinfunction "RPD11/PMCS1/RD11_71") (pintype "bidirectional"))
      (node (ref "J1") (pin "20") (pinfunction "20_20") (pintype "passive"))
      (node (ref "J2") (pin "20") (pinfunction "20_20") (pintype "passive"))
    )
    (net (code "206") (name "Y6") (class "Default")
      (node (ref "IC1") (pin "79") (pinfunction "RPD12/PMD12/RD12_79") (pintype "bidirectional"))
      (node (ref "J1") (pin "18") (pinfunction "18_18") (pintype "passive"))
      (node (ref "J2") (pin "18") (pinfunction "18_18") (pintype "passive"))
    )
    (net (code "207") (name "Y7") (class "Default")
      (node (ref "IC1") (pin "80") (pinfunction "PMD13/RD13_80") (pintype "bidirectional"))
      (node (ref "J1") (pin "16") (pinfunction "16_16") (pintype "passive"))
      (node (ref "J2") (pin "16") (pinfunction "16_16") (pintype "passive"))
    )
    (net (code "208") (name "Y8") (class "Default")
      (node (ref "IC1") (pin "47") (pinfunction "RPD14/RD14_47") (pintype "bidirectional"))
      (node (ref "J1") (pin "14") (pinfunction "14_14") (pintype "passive"))
      (node (ref "J2") (pin "14") (pinfunction "14_14") (pintype "passive"))
    )
    (net (code "209") (name "Y9") (class "Default")
      (node (ref "IC1") (pin "48") (pinfunction "RPD15/RD15_48") (pintype "bidirectional"))
      (node (ref "J1") (pin "12") (pinfunction "12_12") (pintype "passive"))
      (node (ref "J2") (pin "12") (pinfunction "12_12") (pintype "passive"))
    )
    (net (code "210") (name "unconnected-(H3-MOUNT-PadB3,2)") (class "Default")
      (node (ref "H3") (pin "B3,2") (pinfunction "MOUNT_B3,2") (pintype "passive"))
    )
    (net (code "211") (name "unconnected-(H4-MOUNT-PadB3,2)") (class "Default")
      (node (ref "H4") (pin "B3,2") (pinfunction "MOUNT_B3,2") (pintype "passive"))
    )
    (net (code "212") (name "unconnected-(H5-MOUNT-PadB3,2)") (class "Default")
      (node (ref "H5") (pin "B3,2") (pinfunction "MOUNT_B3,2") (pintype "passive"))
    )
    (net (code "213") (name "unconnected-(H6-MOUNT-PadB3,2)") (class "Default")
      (node (ref "H6") (pin "B3,2") (pinfunction "MOUNT_B3,2") (pintype "passive"))
    )
    (net (code "214") (name "unconnected-(IC2-D8-Pad30)") (class "Default")
      (node (ref "IC2") (pin "30") (pinfunction "D8_30") (pintype "tri_state"))
    )
    (net (code "215") (name "unconnected-(IC2-D9-Pad32)") (class "Default")
      (node (ref "IC2") (pin "32") (pinfunction "D9_32") (pintype "tri_state"))
    )
    (net (code "216") (name "unconnected-(IC2-D10-Pad34)") (class "Default")
      (node (ref "IC2") (pin "34") (pinfunction "D10_34") (pintype "tri_state"))
    )
    (net (code "217") (name "unconnected-(IC2-D11-Pad36)") (class "Default")
      (node (ref "IC2") (pin "36") (pinfunction "D11_36") (pintype "tri_state"))
    )
    (net (code "218") (name "unconnected-(IC2-D12-Pad39)") (class "Default")
      (node (ref "IC2") (pin "39") (pinfunction "D12_39") (pintype "tri_state"))
    )
    (net (code "219") (name "unconnected-(IC2-D13-Pad41)") (class "Default")
      (node (ref "IC2") (pin "41") (pinfunction "D13_41") (pintype "tri_state"))
    )
    (net (code "220") (name "unconnected-(IC2-D14-Pad43)") (class "Default")
      (node (ref "IC2") (pin "43") (pinfunction "D14_43") (pintype "tri_state"))
    )
    (net (code "221") (name "unconnected-(IC2-NC-Pad10)") (class "Default")
      (node (ref "IC2") (pin "10") (pinfunction "NC_10") (pintype "no_connect"))
    )
    (net (code "222") (name "unconnected-(IC2-NC1-Pad13)") (class "Default")
      (node (ref "IC2") (pin "13") (pinfunction "NC1_13") (pintype "no_connect"))
    )
    (net (code "223") (name "unconnected-(IC8-PG-Pad9)") (class "Default")
      (node (ref "IC8") (pin "9") (pinfunction "PG_9") (pintype "bidirectional"))
    )
    (net (code "224") (name "unconnected-(J1-Pad1)") (class "Default")
      (node (ref "J1") (pin "1") (pinfunction "1_1") (pintype "passive"))
    )
    (net (code "225") (name "unconnected-(J1-Pad23)") (class "Default")
      (node (ref "J1") (pin "23") (pinfunction "23_23") (pintype "passive"))
    )
    (net (code "226") (name "unconnected-(J1-Pad24)") (class "Default")
      (node (ref "J1") (pin "24") (pinfunction "24_24") (pintype "passive"))
    )
    (net (code "227") (name "unconnected-(J2-Pad1)") (class "Default")
      (node (ref "J2") (pin "1") (pinfunction "1_1") (pintype "passive"))
    )
    (net (code "228") (name "unconnected-(J2-Pad23)") (class "Default")
      (node (ref "J2") (pin "23") (pinfunction "23_23") (pintype "passive"))
    )
    (net (code "229") (name "unconnected-(J2-Pad24)") (class "Default")
      (node (ref "J2") (pin "24") (pinfunction "24_24") (pintype "passive"))
    )
    (net (code "230") (name "unconnected-(J5-Pad6)") (class "Default")
      (node (ref "J5") (pin "6") (pinfunction "6_6") (pintype "bidirectional"))
    )
    (net (code "231") (name "unconnected-(J6-Pad6)") (class "Default")
      (node (ref "J6") (pin "6") (pinfunction "6_6") (pintype "bidirectional"))
    )
    (net (code "232") (name "unconnected-(J11-DAT1-Pad8)") (class "Default")
      (node (ref "J11") (pin "8") (pinfunction "DAT1_8") (pintype "passive"))
    )
    (net (code "233") (name "unconnected-(J11-DAT2-Pad1)") (class "Default")
      (node (ref "J11") (pin "1") (pinfunction "DAT2_1") (pintype "passive"))
    )
    (net (code "234") (name "unconnected-(J14-Pad8)") (class "Default")
      (node (ref "J14") (pin "8") (pinfunction "8_8") (pintype "passive"))
    )
    (net (code "235") (name "unconnected-(J15-Pad2)") (class "Default")
      (node (ref "J15") (pin "2") (pinfunction "2_2") (pintype "passive"))
    )
    (net (code "236") (name "unconnected-(J15-Pad4)") (class "Default")
      (node (ref "J15") (pin "4") (pinfunction "4_4") (pintype "passive"))
    )
    (net (code "237") (name "unconnected-(J15-Pad5)") (class "Default")
      (node (ref "J15") (pin "5") (pinfunction "5_5") (pintype "passive"))
    )
    (net (code "238") (name "unconnected-(J15-Pad6)") (class "Default")
      (node (ref "J15") (pin "6") (pinfunction "6_6") (pintype "passive"))
    )
    (net (code "239") (name "unconnected-(J15-Pad7)") (class "Default")
      (node (ref "J15") (pin "7") (pinfunction "7_7") (pintype "passive"))
    )
    (net (code "240") (name "unconnected-(J15-Pad10)") (class "Default")
      (node (ref "J15") (pin "10") (pinfunction "10_10") (pintype "passive"))
    )
    (net (code "241") (name "unconnected-(J15-Pad15)") (class "Default")
      (node (ref "J15") (pin "15") (pinfunction "15_15") (pintype "passive"))
    )
    (net (code "242") (name "unconnected-(J15-Pad16)") (class "Default")
      (node (ref "J15") (pin "16") (pinfunction "16_16") (pintype "passive"))
    )
    (net (code "243") (name "{slash}3.3V1PWRON") (class "Default")
      (node (ref "IC1") (pin "21") (pinfunction "AN4/C1INB/USBOEN/RB4_21") (pintype "bidirectional"))
      (node (ref "O44") (pin "P$1") (pinfunction "TP_P$1") (pintype "passive"))
      (node (ref "R24") (pin "2") (pinfunction "2_2") (pintype "passive"))
      (node (ref "T32") (pin "P$1") (pinfunction "TP_P$1") (pintype "passive"))
    )
    (net (code "244") (name "{slash}3.3V2PWRON") (class "Default")
      (node (ref "IC1") (pin "96") (pinfunction "TRD1/RG12_96") (pintype "bidirectional"))
      (node (ref "O23") (pin "P$1") (pinfunction "TP_P$1") (pintype "passive"))
      (node (ref "R75") (pin "2") (pinfunction "2_2") (pintype "passive"))
      (node (ref "T33") (pin "P$1") (pinfunction "TP_P$1") (pintype "passive"))
    )
    (net (code "245") (name "{slash}CAM-PWRON") (class "Default")
      (node (ref "IC1") (pin "95") (pinfunction "TRD2/RG14_95") (pintype "bidirectional"))
      (node (ref "O24") (pin "P$1") (pinfunction "TP_P$1") (pintype "passive"))
      (node (ref "R10") (pin "1") (pinfunction "1_1") (pintype "passive"))
      (node (ref "T30") (pin "P$1") (pinfunction "TP_P$1") (pintype "passive"))
    )
    (net (code "246") (name "{slash}FMEM1-CS") (class "Default")
      (node (ref "IC1") (pin "11") (pinfunction "AN17/C1INC/RPG7/PMA4/RG7_11") (pintype "bidirectional"))
      (node (ref "IC9") (pin "1") (pinfunction "/S_1") (pintype "input"))
      (node (ref "O6") (pin "P$1") (pinfunction "TP_P$1") (pintype "passive"))
      (node (ref "R25") (pin "1") (pinfunction "1_1") (pintype "passive"))
      (node (ref "T27") (pin "P$1") (pinfunction "TP_P$1") (pintype "passive"))
    )
    (net (code "247") (name "{slash}MCLR") (class "Default")
      (node (ref "IC1") (pin "13") (pinfunction "~{MCLR}_13") (pintype "input"))
      (node (ref "J17") (pin "1") (pinfunction "1_1") (pintype "passive"))
      (node (ref "R90") (pin "2") (pinfunction "2_2") (pintype "passive"))
    )
    (net (code "248") (name "{slash}NCS") (class "Default")
      (node (ref "IC1") (pin "23") (pinfunction "PGEC3/AN2/C2INB/RPB2/CTED13/RB2_23") (pintype "bidirectional"))
      (node (ref "J15") (pin "13") (pinfunction "13_13") (pintype "passive"))
      (node (ref "O14") (pin "P$1") (pinfunction "TP_P$1") (pintype "passive"))
      (node (ref "T26") (pin "P$1") (pinfunction "TP_P$1") (pintype "passive"))
    )
    (net (code "249") (name "{slash}PRESENT") (class "Default")
      (node (ref "J11") (pin "G2") (pinfunction "G2_G2") (pintype "passive"))
      (node (ref "R131") (pin "2") (pinfunction "2_2") (pintype "passive"))
      (node (ref "T46") (pin "P$1") (pinfunction "TP_P$1") (pintype "passive"))
    )
    (net (code "250") (name "{slash}VPS-PWRON") (class "Default")
      (node (ref "IC1") (pin "17") (pinfunction "TMS/CTED1/RA0_17") (pintype "bidirectional"))
      (node (ref "O9") (pin "P$1") (pinfunction "TP_P$1") (pintype "passive"))
      (node (ref "R107") (pin "2") (pinfunction "2_2") (pintype "passive"))
      (node (ref "T31") (pin "P$1") (pinfunction "TP_P$1") (pintype "passive"))
    )
  )
)
